# Buck-14.net
KiCad netlist of a schematic drawn in Altium Designer
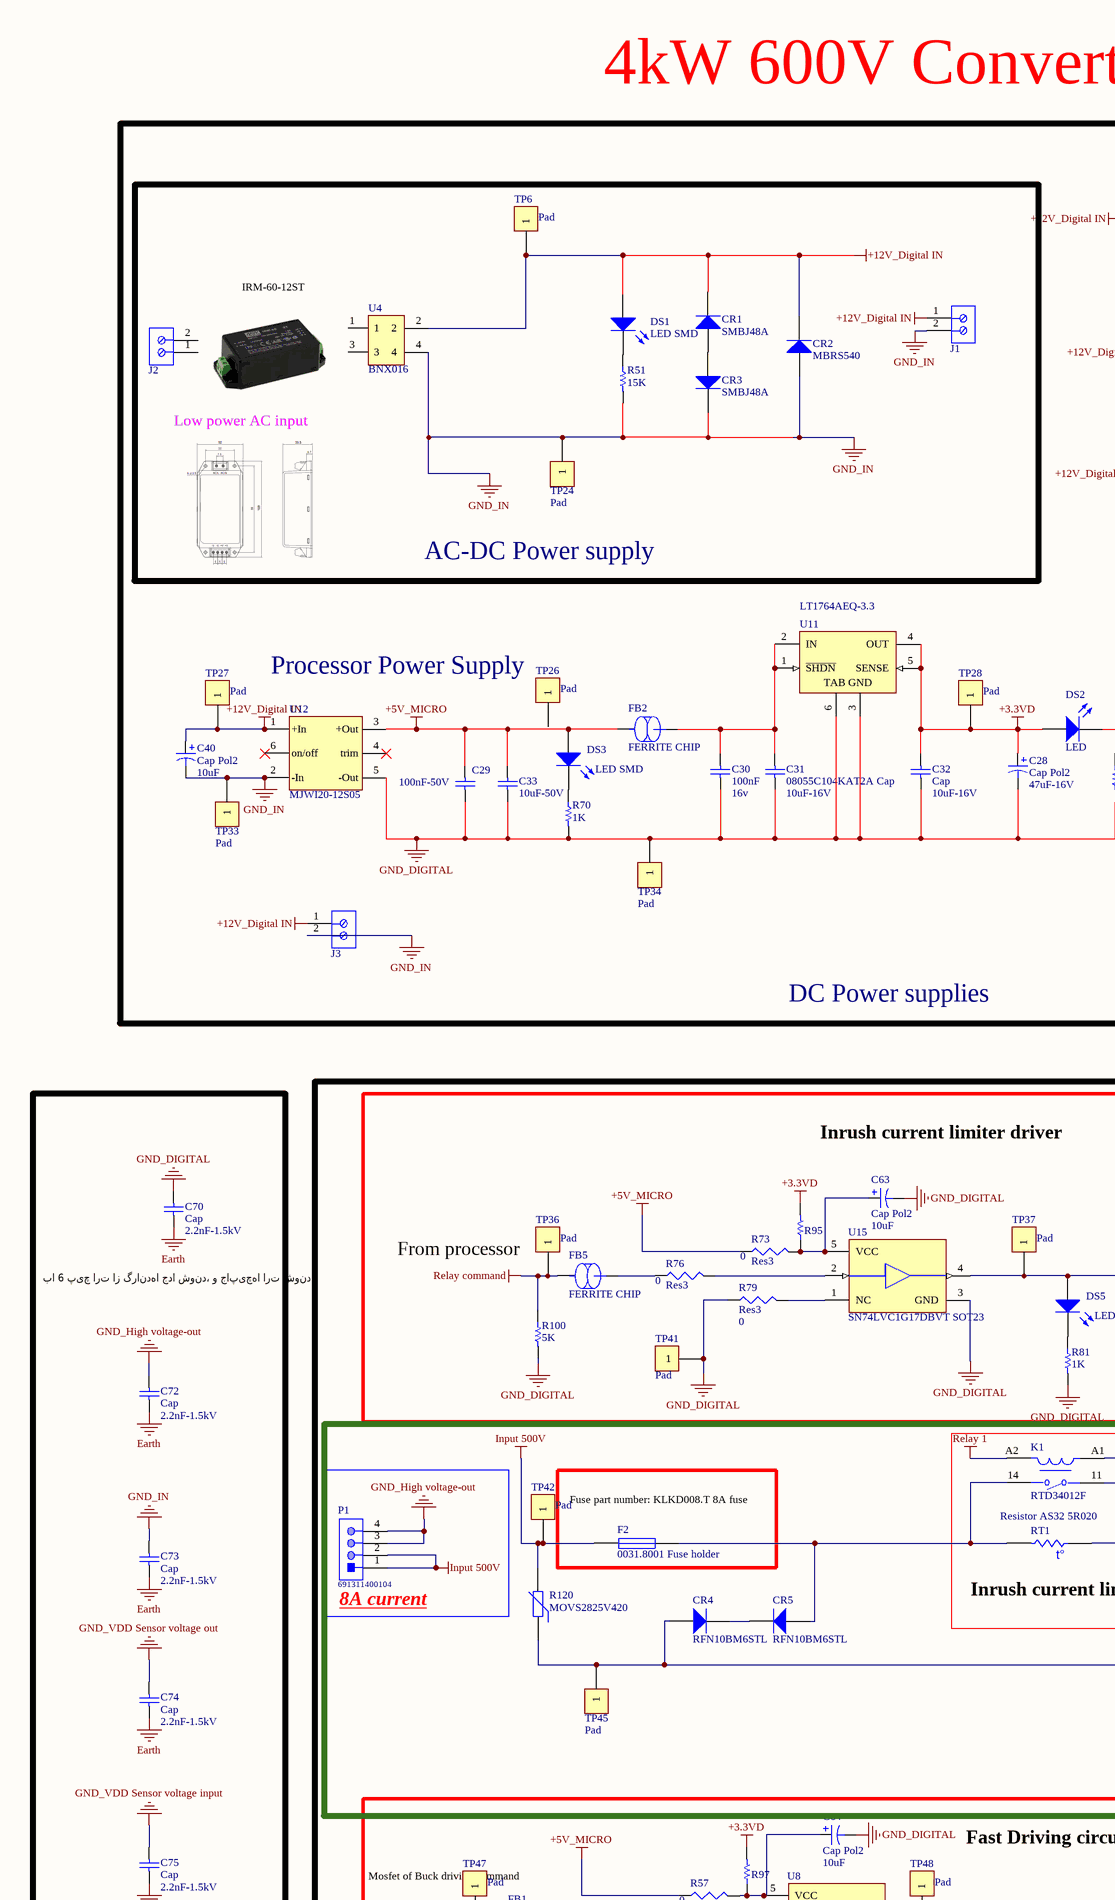
[diagram p0: Buck-14.SchDoc, top left]
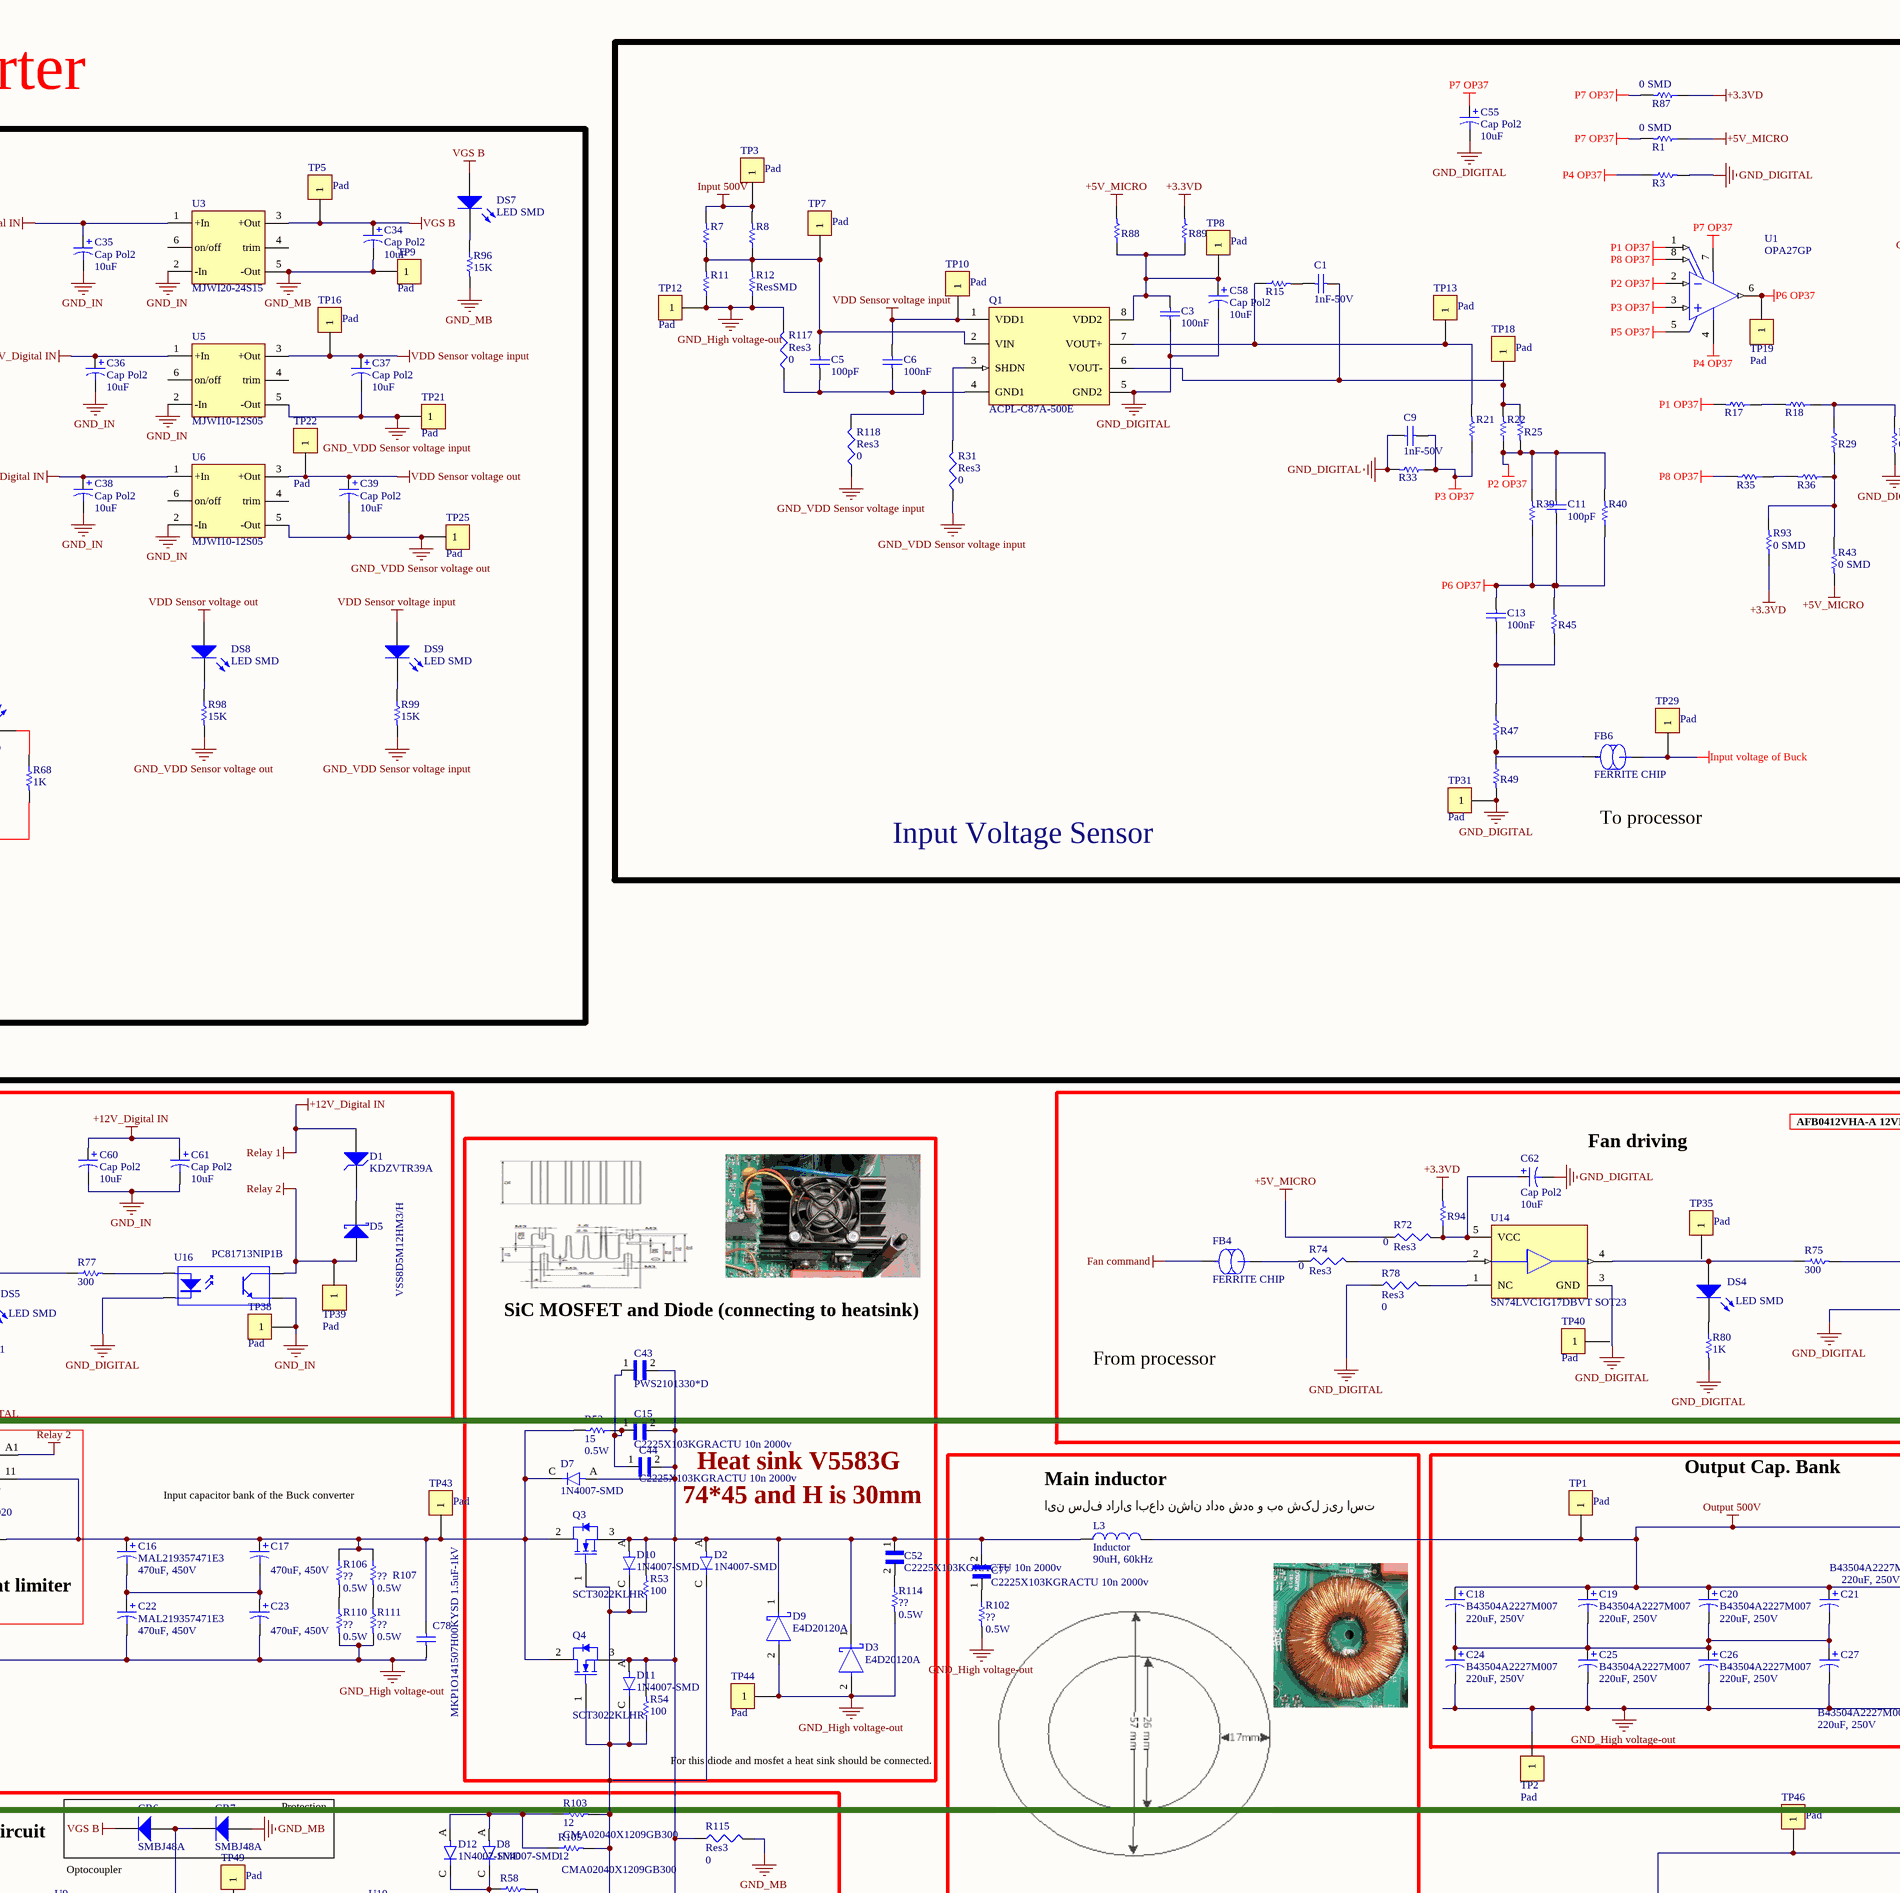
[diagram p1: Buck-14.SchDoc, top middle]
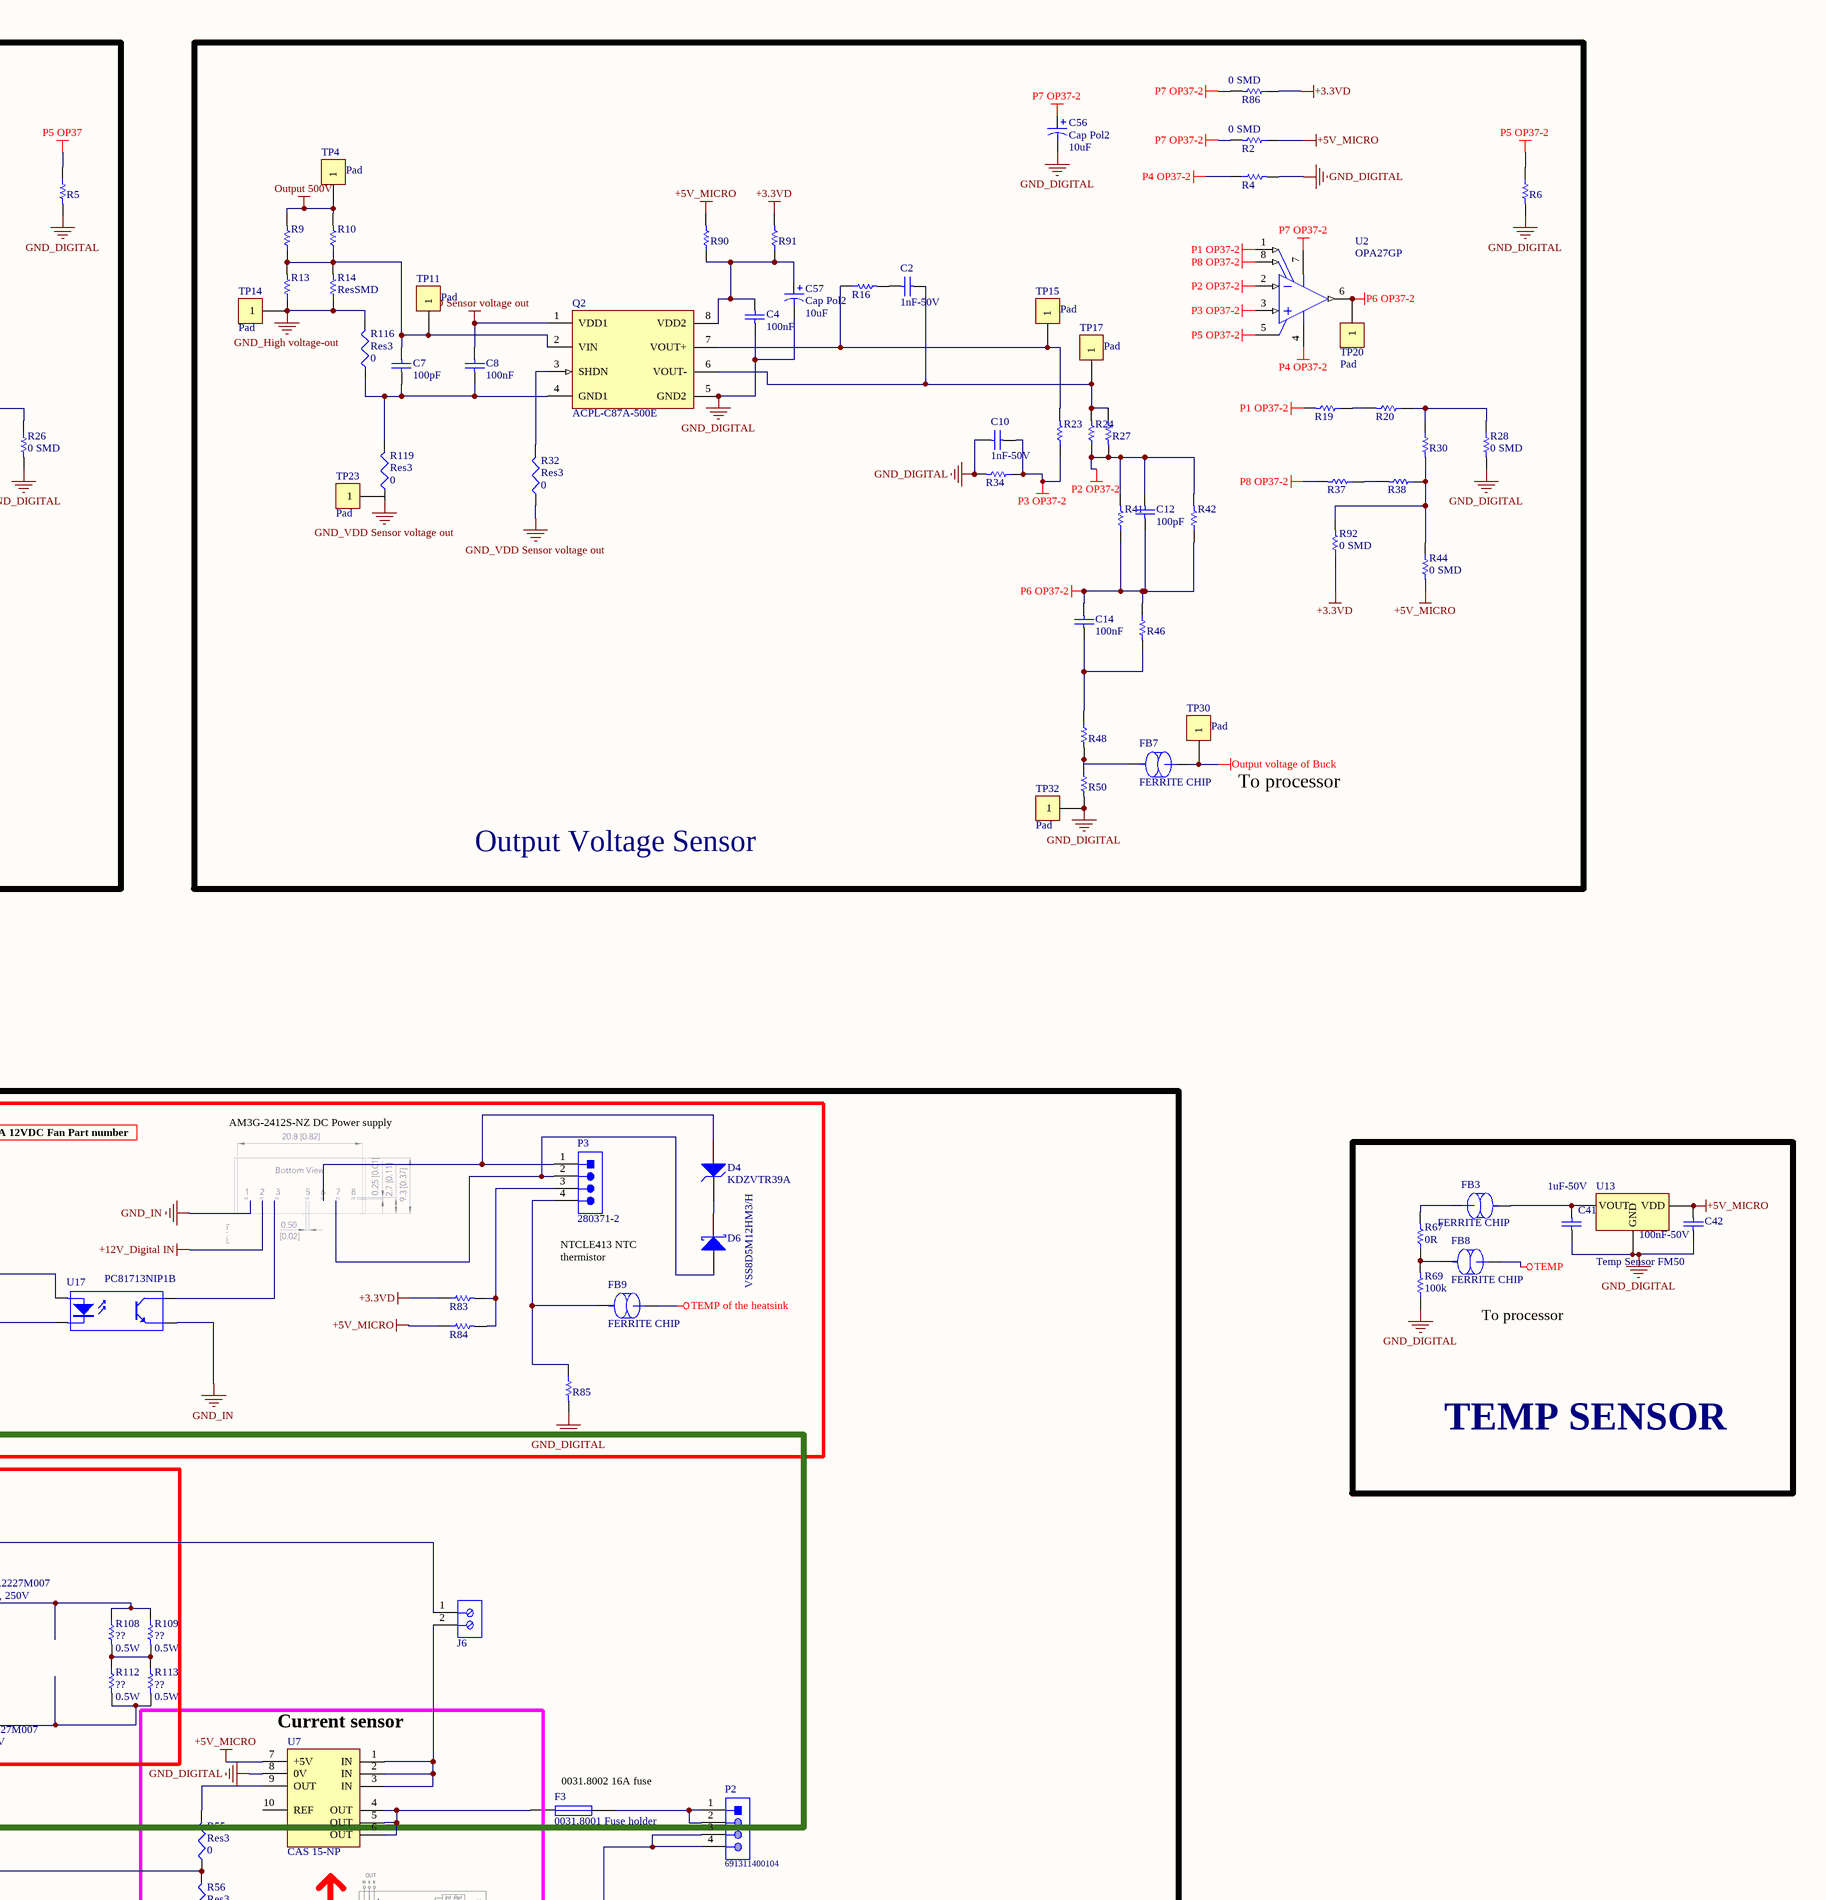
[diagram p2: Buck-14.SchDoc, top right]
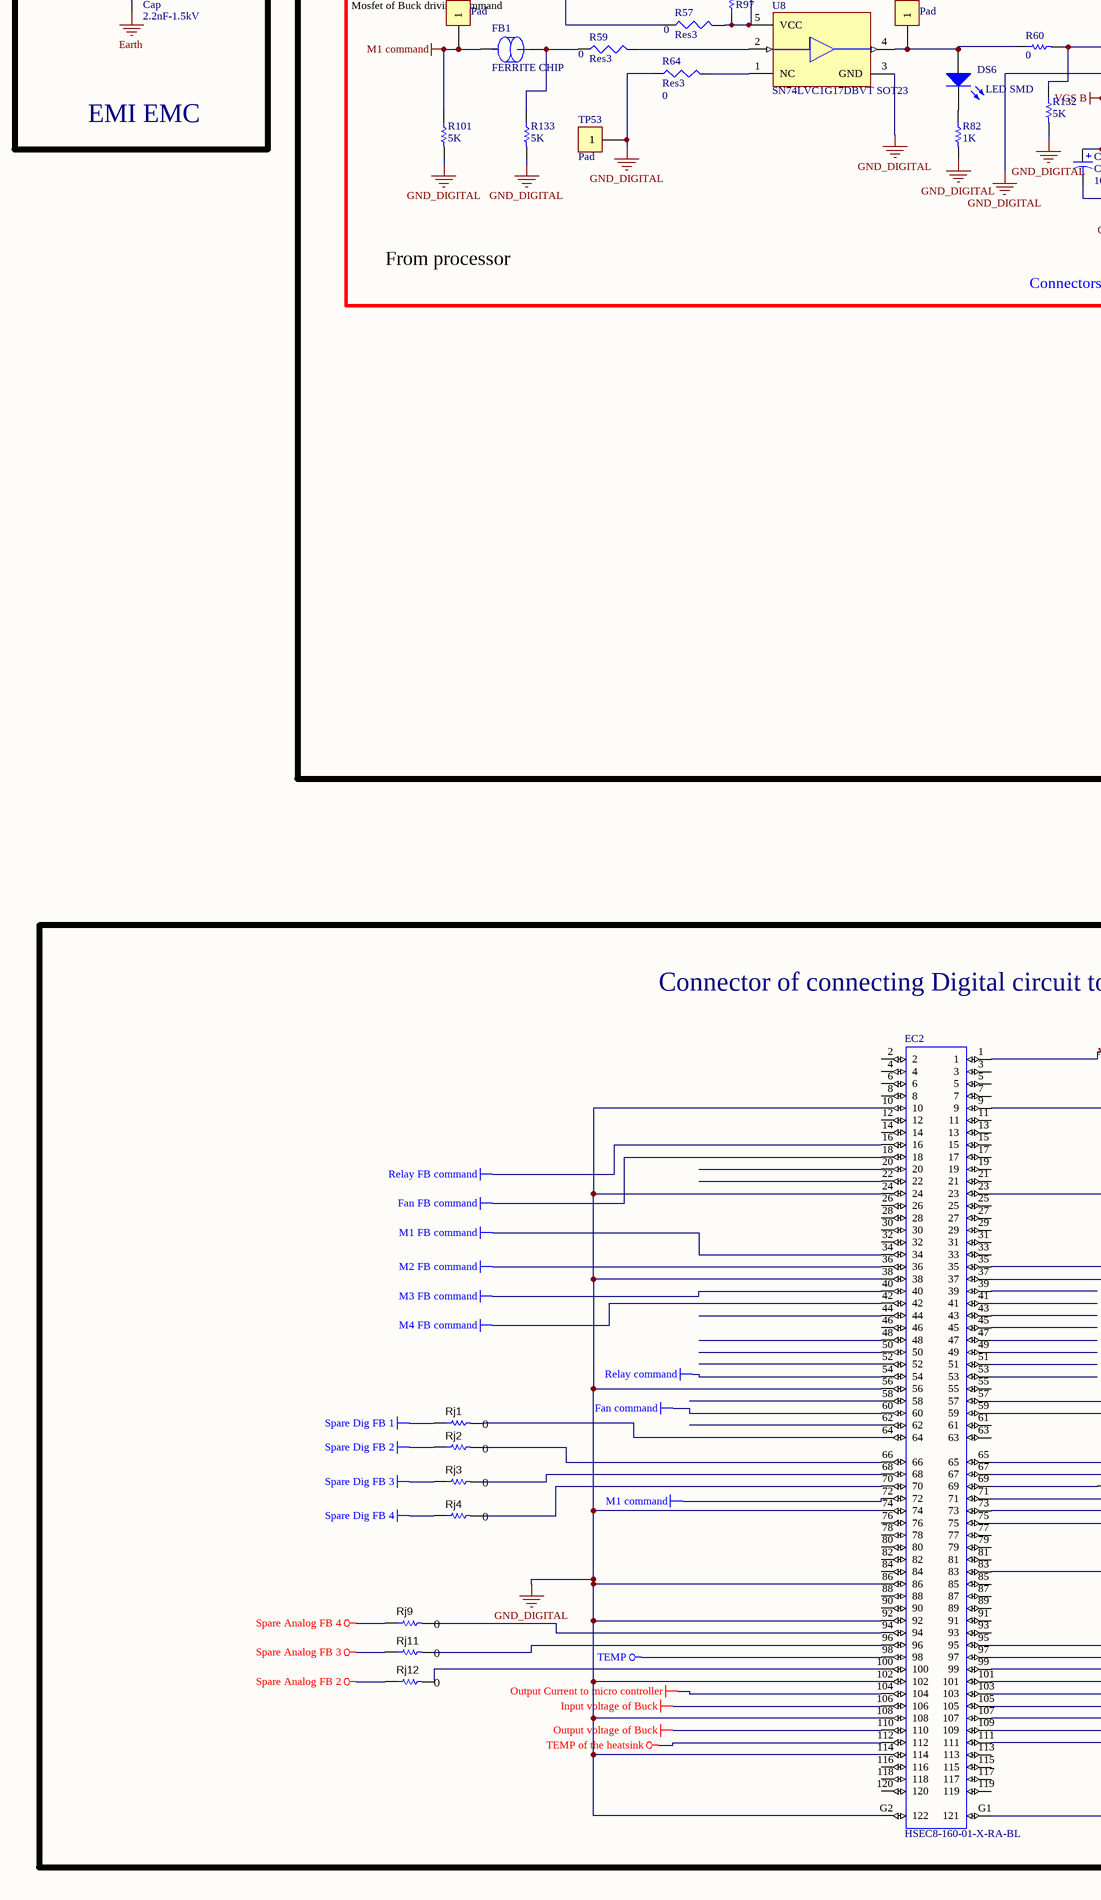
[diagram p3: Buck-14.SchDoc, bottom left]
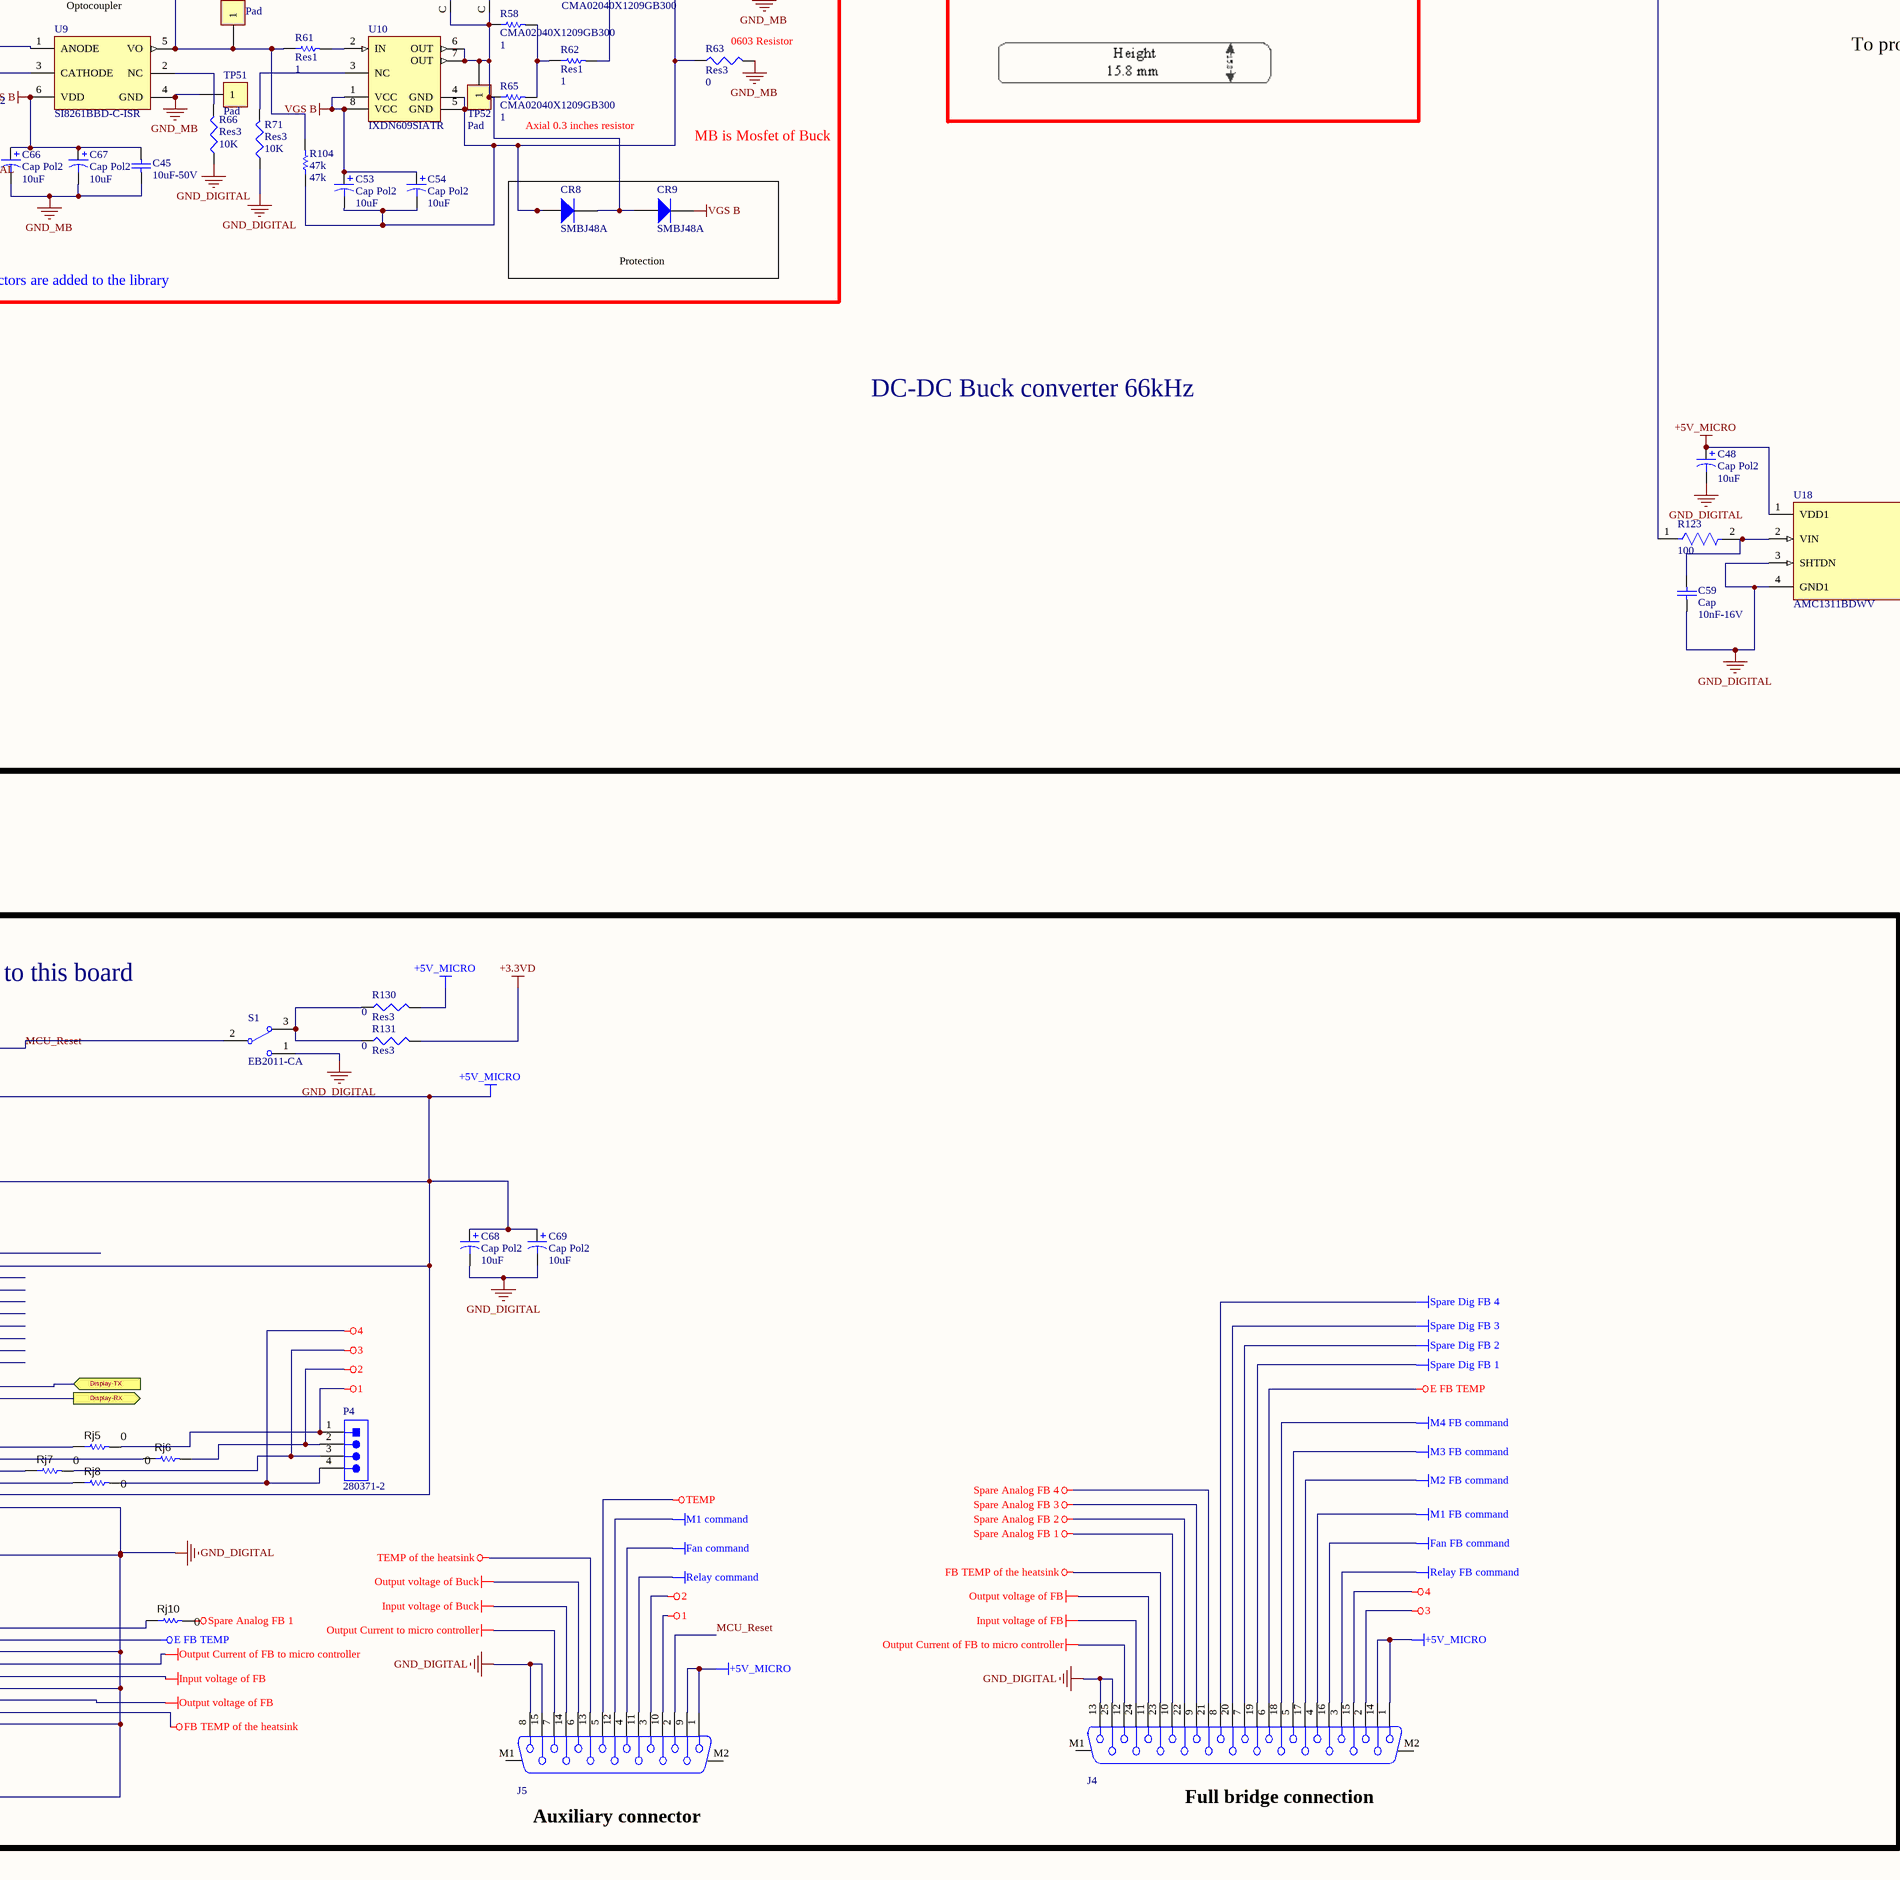
[diagram p4: Buck-14.SchDoc, bottom middle]
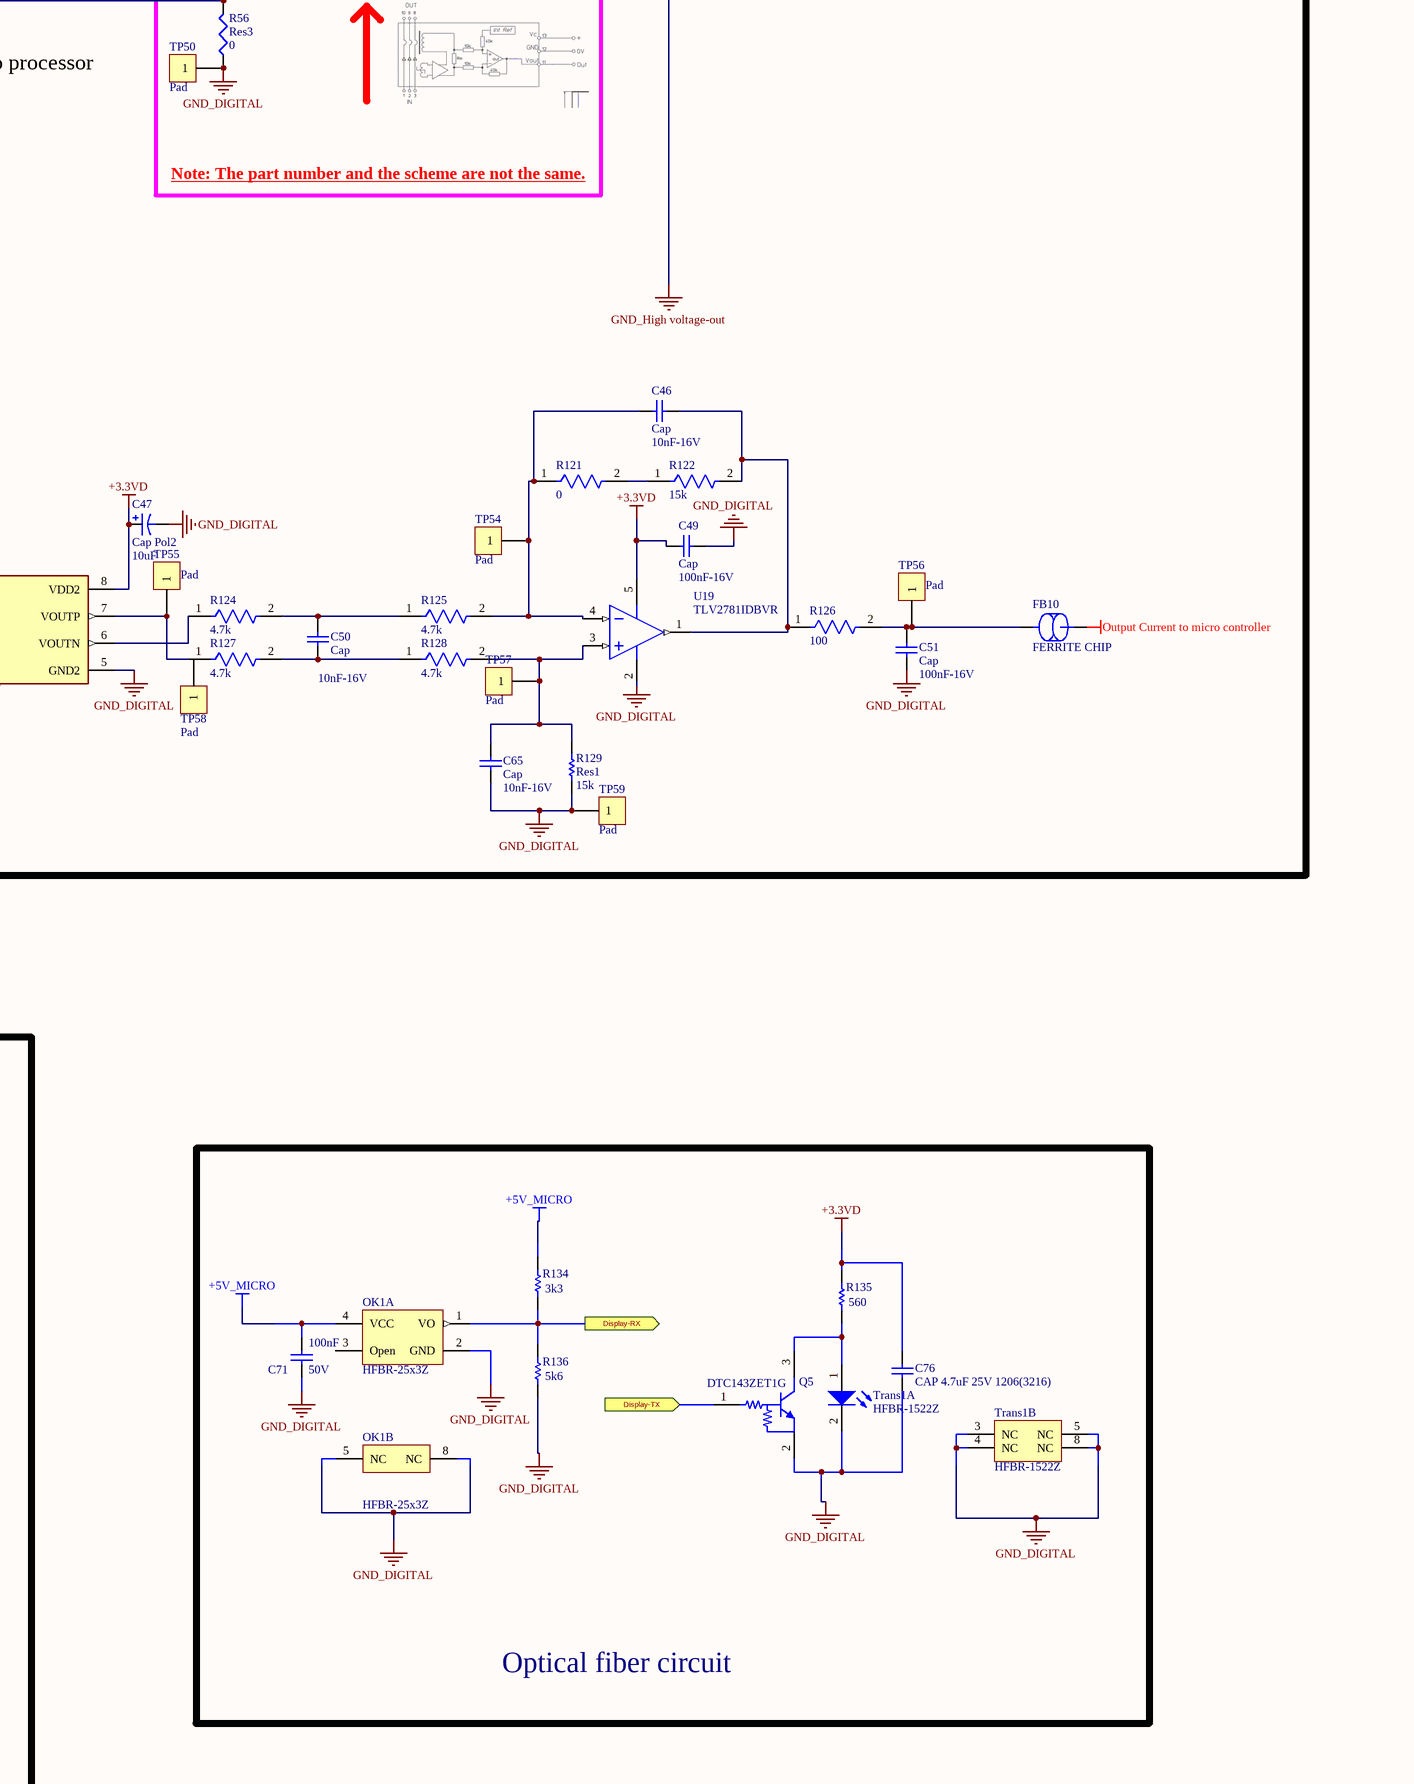
[diagram p5: Buck-14.SchDoc, bottom right]

(export (version "E")
  (design (tool "Eeschema 10.0.6"))
  (components
    (comp (ref "C1")
      (value "1nF-50V")
      (footprint "Footprint_950322:C0805")
      (libsource (lib "MYLIB") (part "CapSMD"))
    )
    (comp (ref "C2")
      (value "1nF-50V")
      (footprint "Footprint_950322:C0805")
      (libsource (lib "MYLIB") (part "CapSMD"))
    )
    (comp (ref "C3")
      (value "100nF")
      (footprint "Footprint_950322:C0805")
      (description "None polar capacitor")
      (libsource (lib "Mylib") (part "Cap ceramic"))
    )
    (comp (ref "C4")
      (value "100nF")
      (footprint "Footprint_950322:C0805")
      (description "None polar capacitor")
      (libsource (lib "Mylib") (part "Cap ceramic"))
    )
    (comp (ref "C5")
      (value "100pF")
      (footprint "Footprint_950322:C0805")
      (description "None polar capacitor")
      (libsource (lib "Mylib") (part "Cap ceramic"))
    )
    (comp (ref "C6")
      (value "100nF")
      (footprint "Footprint_950322:C0805")
      (description "None polar capacitor")
      (libsource (lib "Mylib") (part "Cap ceramic"))
    )
    (comp (ref "C7")
      (value "100pF")
      (footprint "Footprint_950322:C0805")
      (description "None polar capacitor")
      (libsource (lib "Mylib") (part "Cap ceramic"))
    )
    (comp (ref "C8")
      (value "100nF")
      (footprint "Footprint_950322:C0805")
      (description "None polar capacitor")
      (libsource (lib "Mylib") (part "Cap ceramic"))
    )
    (comp (ref "C9")
      (value "1nF-50V")
      (footprint "Footprint_950322:C0805")
      (libsource (lib "MYLIB") (part "CapSMD"))
    )
    (comp (ref "C10")
      (value "1nF-50V")
      (footprint "Footprint_950322:C0805")
      (libsource (lib "MYLIB") (part "CapSMD"))
    )
    (comp (ref "C11")
      (value "100pF")
      (footprint "Footprint_950322:C0805")
      (description "None polar capacitor")
      (libsource (lib "Mylib") (part "Cap ceramic"))
    )
    (comp (ref "C12")
      (value "100pF")
      (footprint "Footprint_950322:C0805")
      (description "None polar capacitor")
      (libsource (lib "Mylib") (part "Cap ceramic"))
    )
    (comp (ref "C13")
      (value "100nF")
      (footprint "Footprint_950322:C0805")
      (description "None polar capacitor")
      (libsource (lib "Mylib") (part "Cap ceramic"))
    )
    (comp (ref "C14")
      (value "100nF")
      (footprint "Footprint_950322:C0805")
      (description "None polar capacitor")
      (libsource (lib "Mylib") (part "Cap ceramic"))
    )
    (comp (ref "C15")
      (value "C2225X103KGRACTU 10n 2000v")
      (footprint "Ceramic disk capacitor")
      (fields (field (name "MF") "AVX") (field (name "MP") "LD052C153JAB2A"))
      (libsource (lib "") (part "Ceramic disk capacitor_1"))
    )
    (comp (ref "C16")
      (value "MAL219357471E3")
      (footprint "Footprint_950322:RB-193 PUR-SI-35x50")
      (description "Polarized Capacitor (Axial)")
      (fields (field (name "ALTIUM_VALUE") "470uF, 450V") (field (name "PUBLISHER") "Altium Limited"))
      (libsource (lib "SCH") (part "Cap Pol2"))
    )
    (comp (ref "C17")
      (value "470uF, 450V")
      (footprint "Footprint_950322:RB-193 PUR-SI-35x50")
      (description "Polarized Capacitor (Axial)")
      (fields (field (name "Comment") "MAL219357471E3") (field (name "PUBLISHER") "Altium Limited"))
      (libsource (lib "SCH") (part "Cap Pol2"))
    )
    (comp (ref "C18")
      (value "B43504A2227M007")
      (footprint "Footprint_950322:RB- B43504")
      (description "Polarized Capacitor (Axial)")
      (fields (field (name "ALTIUM_VALUE") "220uF, 250V") (field (name "PUBLISHER") "Altium Limited"))
      (libsource (lib "SCH") (part "Cap Pol2"))
    )
    (comp (ref "C19")
      (value "B43504A2227M007")
      (footprint "Footprint_950322:RB- B43504")
      (description "Polarized Capacitor (Axial)")
      (fields (field (name "ALTIUM_VALUE") "220uF, 250V") (field (name "PUBLISHER") "Altium Limited"))
      (libsource (lib "SCH") (part "Cap Pol2"))
    )
    (comp (ref "C20")
      (value "B43504A2227M007")
      (footprint "Footprint_950322:RB- B43504")
      (description "Polarized Capacitor (Axial)")
      (fields (field (name "ALTIUM_VALUE") "220uF, 250V") (field (name "PUBLISHER") "Altium Limited"))
      (libsource (lib "SCH") (part "Cap Pol2"))
    )
    (comp (ref "C21")
      (value "B43504A2227M007")
      (footprint "Footprint_950322:RB- B43504")
      (description "Polarized Capacitor (Axial)")
      (fields (field (name "ALTIUM_VALUE") "220uF, 250V") (field (name "PUBLISHER") "Altium Limited"))
      (libsource (lib "SCH") (part "Cap Pol2"))
    )
    (comp (ref "C22")
      (value "MAL219357471E3")
      (footprint "Footprint_950322:RB-193 PUR-SI-35x50")
      (description "Polarized Capacitor (Axial)")
      (fields (field (name "ALTIUM_VALUE") "470uF, 450V") (field (name "PUBLISHER") "Altium Limited"))
      (libsource (lib "SCH") (part "Cap Pol2"))
    )
    (comp (ref "C23")
      (value "470uF, 450V")
      (footprint "Footprint_950322:RB-193 PUR-SI-35x50")
      (description "Polarized Capacitor (Axial)")
      (fields (field (name "Comment") "MAL219357471E3") (field (name "PUBLISHER") "Altium Limited"))
      (libsource (lib "SCH") (part "Cap Pol2"))
    )
    (comp (ref "C24")
      (value "B43504A2227M007")
      (footprint "Footprint_950322:RB- B43504")
      (description "Polarized Capacitor (Axial)")
      (fields (field (name "ALTIUM_VALUE") "220uF, 250V") (field (name "PUBLISHER") "Altium Limited"))
      (libsource (lib "SCH") (part "Cap Pol2"))
    )
    (comp (ref "C25")
      (value "B43504A2227M007")
      (footprint "Footprint_950322:RB- B43504")
      (description "Polarized Capacitor (Axial)")
      (fields (field (name "ALTIUM_VALUE") "220uF, 250V") (field (name "PUBLISHER") "Altium Limited"))
      (libsource (lib "SCH") (part "Cap Pol2"))
    )
    (comp (ref "C26")
      (value "B43504A2227M007")
      (footprint "Footprint_950322:RB- B43504")
      (description "Polarized Capacitor (Axial)")
      (fields (field (name "ALTIUM_VALUE") "220uF, 250V") (field (name "PUBLISHER") "Altium Limited"))
      (libsource (lib "SCH") (part "Cap Pol2"))
    )
    (comp (ref "C27")
      (value "B43504A2227M007")
      (footprint "Footprint_950322:RB- B43504")
      (description "Polarized Capacitor (Axial)")
      (fields (field (name "ALTIUM_VALUE") "220uF, 250V") (field (name "PUBLISHER") "Altium Limited"))
      (libsource (lib "SCH") (part "Cap Pol2"))
    )
    (comp (ref "C28")
      (value "Cap Pol2")
      (footprint "Footprint_950322:CAP_Aluminum-G6.3")
      (description "Polarized Capacitor (Axial)")
      (fields (field (name "ALTIUM_VALUE") "47uF-16V") (field (name "PUBLISHER") "Altium Limited"))
      (libsource (lib "SCH") (part "Cap Pol2"))
    )
    (comp (ref "C29")
      (value "100nF-50V")
      (footprint "Footprint_950322:C0805")
      (libsource (lib "MYLIB") (part "CapSMD"))
    )
    (comp (ref "C30")
      (value "100nF")
      (footprint "Footprint_950322:C0805")
      (description "None polar capacitor")
      (fields (field (name "VOLTE") "16v"))
      (libsource (lib "Mylib") (part "Cap ceramic"))
    )
    (comp (ref "C31")
      (value "08055C104KAT2A Cap")
      (footprint "Footprint_950322:C0805")
      (description "Capacitor")
      (fields (field (name "ALTIUM_VALUE") "10uF-16V") (field (name "PUBLISHER") "Altium Limited"))
      (libsource (lib "SCH") (part "Cap"))
    )
    (comp (ref "C32")
      (value "Cap")
      (footprint "Footprint_950322:C0805")
      (description "Capacitor")
      (fields (field (name "ALTIUM_VALUE") "10uF-16V") (field (name "PUBLISHER") "Altium Limited"))
      (libsource (lib "SCH") (part "Cap"))
    )
    (comp (ref "C33")
      (value "10uF-50V")
      (footprint "Footprint_950322:C0805")
      (libsource (lib "") (part "CapSMD_1"))
    )
    (comp (ref "C34")
      (value "Cap Pol2")
      (footprint "SMD 3016")
      (description "Polarized Capacitor (Axial)")
      (fields (field (name "ALTIUM_VALUE") "10uF") (field (name "PUBLISHER") "Altium Limited"))
      (libsource (lib "SCH") (part "Cap Pol2"))
    )
    (comp (ref "C35")
      (value "Cap Pol2")
      (footprint "SMD 3016")
      (description "Polarized Capacitor (Axial)")
      (fields (field (name "ALTIUM_VALUE") "10uF") (field (name "PUBLISHER") "Altium Limited"))
      (libsource (lib "SCH") (part "Cap Pol2"))
    )
    (comp (ref "C36")
      (value "Cap Pol2")
      (footprint "SMD 3016")
      (description "Polarized Capacitor (Axial)")
      (fields (field (name "ALTIUM_VALUE") "10uF") (field (name "PUBLISHER") "Altium Limited"))
      (libsource (lib "SCH") (part "Cap Pol2"))
    )
    (comp (ref "C37")
      (value "Cap Pol2")
      (footprint "SMD 3016")
      (description "Polarized Capacitor (Axial)")
      (fields (field (name "ALTIUM_VALUE") "10uF") (field (name "PUBLISHER") "Altium Limited"))
      (libsource (lib "SCH") (part "Cap Pol2"))
    )
    (comp (ref "C38")
      (value "Cap Pol2")
      (footprint "SMD 3016")
      (description "Polarized Capacitor (Axial)")
      (fields (field (name "ALTIUM_VALUE") "10uF") (field (name "PUBLISHER") "Altium Limited"))
      (libsource (lib "SCH") (part "Cap Pol2"))
    )
    (comp (ref "C39")
      (value "Cap Pol2")
      (footprint "SMD 3016")
      (description "Polarized Capacitor (Axial)")
      (fields (field (name "ALTIUM_VALUE") "10uF") (field (name "PUBLISHER") "Altium Limited"))
      (libsource (lib "SCH") (part "Cap Pol2"))
    )
    (comp (ref "C40")
      (value "Cap Pol2")
      (footprint "SMD 3016")
      (description "Polarized Capacitor (Axial)")
      (fields (field (name "ALTIUM_VALUE") "10uF") (field (name "PUBLISHER") "Altium Limited"))
      (libsource (lib "SCH") (part "Cap Pol2"))
    )
    (comp (ref "C41")
      (value "1uF-50V")
      (footprint "Footprint_950322:C0805")
      (libsource (lib "MYLIB") (part "CapSMD"))
    )
    (comp (ref "C42") (value "100nF-50V") (footprint "CapSMD-805") (libsource (lib "MYLIB") (part "CapSMD")))
    (comp (ref "C43")
      (value "PWS2101330*D")
      (footprint "Ceramic disk capacitor")
      (fields (field (name "MF") "AVX") (field (name "MP") "LD052C153JAB2A"))
      (libsource (lib "") (part "Ceramic disk capacitor_1"))
    )
    (comp (ref "C44")
      (value "C2225X103KGRACTU 10n 2000v")
      (footprint "Ceramic disk capacitor")
      (fields (field (name "MF") "AVX") (field (name "MP") "LD052C153JAB2A"))
      (libsource (lib "") (part "Ceramic disk capacitor_1"))
    )
    (comp (ref "C45")
      (value "10uF-50V")
      (footprint "Footprint_950322:C0805")
      (libsource (lib "") (part "CapSMD_1"))
    )
    (comp (ref "C46")
      (value "Cap")
      (footprint "SMD 0805-cap")
      (description "Capacitor")
      (fields (field (name "ALTIUM_VALUE") "10nF-16V") (field (name "PUBLISHER") "Altium Limited"))
      (libsource (lib "SCH") (part "Cap"))
    )
    (comp (ref "C47")
      (value "Cap Pol2")
      (footprint "SMD 3016")
      (description "Polarized Capacitor (Axial)")
      (fields (field (name "ALTIUM_VALUE") "10uF") (field (name "PUBLISHER") "Altium Limited"))
      (libsource (lib "SCH") (part "Cap Pol2"))
    )
    (comp (ref "C48")
      (value "Cap Pol2")
      (footprint "SMD 3016")
      (description "Polarized Capacitor (Axial)")
      (fields (field (name "ALTIUM_VALUE") "10uF") (field (name "PUBLISHER") "Altium Limited"))
      (libsource (lib "SCH") (part "Cap Pol2"))
    )
    (comp (ref "C49")
      (value "Cap")
      (footprint "SMD 0805-cap")
      (description "Capacitor")
      (fields (field (name "ALTIUM_VALUE") "100nF-16V") (field (name "PUBLISHER") "Altium Limited"))
      (libsource (lib "SCH") (part "Cap"))
    )
    (comp (ref "C50")
      (value "Cap")
      (footprint "SMD 0805-cap")
      (description "Capacitor")
      (fields (field (name "ALTIUM_VALUE") "10nF-16V") (field (name "PUBLISHER") "Altium Limited"))
      (libsource (lib "SCH") (part "Cap"))
    )
    (comp (ref "C51")
      (value "Cap")
      (footprint "SMD 0805-cap")
      (description "Capacitor")
      (fields (field (name "ALTIUM_VALUE") "100nF-16V") (field (name "PUBLISHER") "Altium Limited"))
      (libsource (lib "SCH") (part "Cap"))
    )
    (comp (ref "C52")
      (value "C2225X103KGRACTU 10n 2000v")
      (footprint "Ceramic disk capacitor")
      (fields (field (name "MF") "AVX") (field (name "MP") "LD052C153JAB2A"))
      (libsource (lib "") (part "Ceramic disk capacitor_2"))
    )
    (comp (ref "C53")
      (value "Cap Pol2")
      (footprint "SMD 3016")
      (description "Polarized Capacitor (Axial)")
      (fields (field (name "ALTIUM_VALUE") "10uF") (field (name "PUBLISHER") "Altium Limited"))
      (libsource (lib "SCH") (part "Cap Pol2"))
    )
    (comp (ref "C54")
      (value "Cap Pol2")
      (footprint "SMD 3016")
      (description "Polarized Capacitor (Axial)")
      (fields (field (name "ALTIUM_VALUE") "10uF") (field (name "PUBLISHER") "Altium Limited"))
      (libsource (lib "SCH") (part "Cap Pol2"))
    )
    (comp (ref "C55")
      (value "Cap Pol2")
      (footprint "SMD 3016")
      (description "Polarized Capacitor (Axial)")
      (fields (field (name "ALTIUM_VALUE") "10uF") (field (name "PUBLISHER") "Altium Limited"))
      (libsource (lib "SCH") (part "Cap Pol2"))
    )
    (comp (ref "C56")
      (value "Cap Pol2")
      (footprint "SMD 3016")
      (description "Polarized Capacitor (Axial)")
      (fields (field (name "ALTIUM_VALUE") "10uF") (field (name "PUBLISHER") "Altium Limited"))
      (libsource (lib "SCH") (part "Cap Pol2"))
    )
    (comp (ref "C57")
      (value "Cap Pol2")
      (footprint "SMD 3016")
      (description "Polarized Capacitor (Axial)")
      (fields (field (name "ALTIUM_VALUE") "10uF") (field (name "PUBLISHER") "Altium Limited"))
      (libsource (lib "SCH") (part "Cap Pol2"))
    )
    (comp (ref "C58")
      (value "Cap Pol2")
      (footprint "SMD 3016")
      (description "Polarized Capacitor (Axial)")
      (fields (field (name "ALTIUM_VALUE") "10uF") (field (name "PUBLISHER") "Altium Limited"))
      (libsource (lib "SCH") (part "Cap Pol2"))
    )
    (comp (ref "C59")
      (value "Cap")
      (footprint "SMD 0805-cap")
      (description "Capacitor")
      (fields (field (name "ALTIUM_VALUE") "10nF-16V") (field (name "PUBLISHER") "Altium Limited"))
      (libsource (lib "SCH") (part "Cap"))
    )
    (comp (ref "C60")
      (value "Cap Pol2")
      (footprint "SMD 3016")
      (description "Polarized Capacitor (Axial)")
      (fields (field (name "ALTIUM_VALUE") "10uF") (field (name "PUBLISHER") "Altium Limited"))
      (libsource (lib "SCH") (part "Cap Pol2"))
    )
    (comp (ref "C61")
      (value "Cap Pol2")
      (footprint "SMD 3016")
      (description "Polarized Capacitor (Axial)")
      (fields (field (name "ALTIUM_VALUE") "10uF") (field (name "PUBLISHER") "Altium Limited"))
      (libsource (lib "SCH") (part "Cap Pol2"))
    )
    (comp (ref "C62")
      (value "Cap Pol2")
      (footprint "SMD 3016")
      (description "Polarized Capacitor (Axial)")
      (fields (field (name "ALTIUM_VALUE") "10uF") (field (name "PUBLISHER") "Altium Limited"))
      (libsource (lib "SCH") (part "Cap Pol2"))
    )
    (comp (ref "C63")
      (value "Cap Pol2")
      (footprint "SMD 3016")
      (description "Polarized Capacitor (Axial)")
      (fields (field (name "ALTIUM_VALUE") "10uF") (field (name "PUBLISHER") "Altium Limited"))
      (libsource (lib "SCH") (part "Cap Pol2"))
    )
    (comp (ref "C64")
      (value "Cap Pol2")
      (footprint "SMD 3016")
      (description "Polarized Capacitor (Axial)")
      (fields (field (name "ALTIUM_VALUE") "10uF") (field (name "PUBLISHER") "Altium Limited"))
      (libsource (lib "SCH") (part "Cap Pol2"))
    )
    (comp (ref "C65")
      (value "Cap")
      (footprint "SMD 0805-cap")
      (description "Capacitor")
      (fields (field (name "ALTIUM_VALUE") "10nF-16V") (field (name "PUBLISHER") "Altium Limited"))
      (libsource (lib "SCH") (part "Cap"))
    )
    (comp (ref "C66")
      (value "Cap Pol2")
      (footprint "SMD 3016")
      (description "Polarized Capacitor (Axial)")
      (fields (field (name "ALTIUM_VALUE") "10uF") (field (name "PUBLISHER") "Altium Limited"))
      (libsource (lib "SCH") (part "Cap Pol2"))
    )
    (comp (ref "C67")
      (value "Cap Pol2")
      (footprint "SMD 3016")
      (description "Polarized Capacitor (Axial)")
      (fields (field (name "ALTIUM_VALUE") "10uF") (field (name "PUBLISHER") "Altium Limited"))
      (libsource (lib "SCH") (part "Cap Pol2"))
    )
    (comp (ref "C68")
      (value "Cap Pol2")
      (footprint "SMD 3016")
      (description "Polarized Capacitor (Axial)")
      (fields (field (name "ALTIUM_VALUE") "10uF") (field (name "PUBLISHER") "Altium Limited"))
      (libsource (lib "SCH") (part "Cap Pol2"))
    )
    (comp (ref "C69")
      (value "Cap Pol2")
      (footprint "SMD 3016")
      (description "Polarized Capacitor (Axial)")
      (fields (field (name "ALTIUM_VALUE") "10uF") (field (name "PUBLISHER") "Altium Limited"))
      (libsource (lib "SCH") (part "Cap Pol2"))
    )
    (comp (ref "C70")
      (value "Cap")
      (footprint "SMD 0805-cap")
      (description "Capacitor")
      (fields (field (name "AY1222M47Y5UC63L0") "2.2nF-1.5kV") (field (name "PUBLISHER") "Altium Limited"))
      (libsource (lib "SCH") (part "Cap"))
    )
    (comp (ref "C71")
      (value "GRM188R71H104KA93D")
      (footprint "CAPC1608X90X35ML10T15")
      (description "Chip Capacitor, 0.1 uF, +/- 10%, 50 V, -55 to 125 degC, 0603 (1608 Metric), RoHS, Tape and Reel")
      (fields
        (field (name "TOLERANCE") "10%")
        (field (name "VOLTAGE RATING") "50V")
        (field (name "CAPACITANCE") "100nF")
        (field (name "VOLTAGE") "50V")
      )
      (libsource (lib "Altium Content Vault") (part "CAP-NP-2"))
    )
    (comp (ref "C72")
      (value "Cap")
      (footprint "SMD 0805-cap")
      (description "Capacitor")
      (fields (field (name "AY1222M47Y5UC63L0") "2.2nF-1.5kV") (field (name "PUBLISHER") "Altium Limited"))
      (libsource (lib "SCH") (part "Cap"))
    )
    (comp (ref "C73")
      (value "Cap")
      (footprint "SMD 0805-cap")
      (description "Capacitor")
      (fields (field (name "AY1222M47Y5UC63L0") "2.2nF-1.5kV") (field (name "PUBLISHER") "Altium Limited"))
      (libsource (lib "SCH") (part "Cap"))
    )
    (comp (ref "C74")
      (value "Cap")
      (footprint "SMD 0805-cap")
      (description "Capacitor")
      (fields (field (name "AY1222M47Y5UC63L0") "2.2nF-1.5kV") (field (name "PUBLISHER") "Altium Limited"))
      (libsource (lib "SCH") (part "Cap"))
    )
    (comp (ref "C75")
      (value "Cap")
      (footprint "SMD 0805-cap")
      (description "Capacitor")
      (fields (field (name "AY1222M47Y5UC63L0") "2.2nF-1.5kV") (field (name "PUBLISHER") "Altium Limited"))
      (libsource (lib "SCH") (part "Cap"))
    )
    (comp (ref "C76")
      (value "CAP 4.7uF 25V 1206(3216)")
      (footprint "CAPC1206(3216)190_N")
      (description "CAP 4.7uF 25V ±5% 1206 (3216 Metric) Thickness 1.9mm SMD")
      (fields (field (name "TOLERANCE") "Â±5%"))
      (libsource (lib "Altium Content Vault") (part "CAP"))
    )
    (comp (ref "C77")
      (value "C2225X103KGRACTU 10n 2000v")
      (footprint "Ceramic disk capacitor")
      (fields (field (name "MF") "AVX") (field (name "MP") "LD052C153JAB2A"))
      (libsource (lib "Capacitors dip") (part "Ceramic disk capacitor"))
    )
    (comp (ref "C78")
      (value "MKP1O141507H00KYSD 1.5uF-1kV")
      (footprint "CapSMD-805")
      (libsource (lib "MYLIB") (part "CapSMD"))
    )
    (comp (ref "CR1")
      (value "SMBJ48A")
      (footprint "DiodeSMD4.5mm")
      (libsource (lib "MYLIB") (part "DiodeSMD4.5mm"))
    )
    (comp (ref "CR2")
      (value "MBRS540")
      (footprint "DiodeSMD5.5mm")
      (libsource (lib "MYLIB") (part "DiodeSMD5.5mm"))
    )
    (comp (ref "CR3")
      (value "SMBJ48A")
      (footprint "DiodeSMD4.5mm")
      (libsource (lib "MYLIB") (part "DiodeSMD4.5mm"))
    )
    (comp (ref "CR4")
      (value "RFN10BM6STL")
      (footprint "DiodeSMD4.5mm")
      (libsource (lib "MYLIB") (part "DiodeSMD4.5mm"))
    )
    (comp (ref "CR5")
      (value "RFN10BM6STL")
      (footprint "DiodeSMD4.5mm")
      (libsource (lib "MYLIB") (part "DiodeSMD4.5mm"))
    )
    (comp (ref "CR6")
      (value "SMBJ48A")
      (footprint "DiodeSMD4.5mm")
      (libsource (lib "MYLIB") (part "DiodeSMD4.5mm"))
    )
    (comp (ref "CR7")
      (value "SMBJ48A")
      (footprint "DiodeSMD4.5mm")
      (libsource (lib "MYLIB") (part "DiodeSMD4.5mm"))
    )
    (comp (ref "CR8")
      (value "SMBJ48A")
      (footprint "DiodeSMD4.5mm")
      (libsource (lib "MYLIB") (part "DiodeSMD4.5mm"))
    )
    (comp (ref "CR9")
      (value "SMBJ48A")
      (footprint "DiodeSMD4.5mm")
      (libsource (lib "MYLIB") (part "DiodeSMD4.5mm"))
    )
    (comp (ref "D1")
      (value "KDZVTR39A")
      (footprint "DIODE-0.7")
      (description "Zener Diode")
      (fields (field (name "PUBLISHER") "Altium Limited"))
      (libsource (lib "Miscellaneous Devices") (part "D Zener"))
    )
    (comp (ref "D2")
      (value "1N4007-SMD")
      (footprint "DIOAD1060W80L520D270")
      (description "Diode Standard 1000V 1A Through Hole DO-204AL _DO-41_")
      (fields (field (name "MF") "ON Semiconductor") (field (name "MP") "1N4007"))
      (libsource (lib "Diode") (part "1N4007"))
    )
    (comp (ref "D3")
      (value "E4D20120A")
      (footprint "FP-TO-220-2-MFG")
      (description "E SERIES, 20 AMP, 1200V G4 SCHOT")
      (libsource (lib "Altium Content Vault") (part "1d6ec82d83fb6aee721767c19dac4b9"))
    )
    (comp (ref "D4")
      (value "KDZVTR39A")
      (footprint "DIODE-0.7")
      (description "Zener Diode")
      (fields (field (name "PUBLISHER") "Altium Limited"))
      (libsource (lib "Miscellaneous Devices") (part "D Zener"))
    )
    (comp (ref "D5")
      (value "VSS8D5M12HM3/H")
      (footprint "SMB")
      (description "Schottky Diode")
      (fields (field (name "PUBLISHER") "Altium Limited"))
      (libsource (lib "Miscellaneous Devices") (part "D Schottky"))
    )
    (comp (ref "D6")
      (value "VSS8D5M12HM3/H")
      (footprint "SMB")
      (description "Schottky Diode")
      (fields (field (name "PUBLISHER") "Altium Limited"))
      (libsource (lib "Miscellaneous Devices") (part "D Schottky"))
    )
    (comp (ref "D7")
      (value "1N4007-SMD")
      (footprint "DIOAD1060W80L520D270")
      (description "Diode Standard 1000V 1A Through Hole DO-204AL _DO-41_")
      (fields (field (name "MF") "ON Semiconductor") (field (name "MP") "1N4007"))
      (libsource (lib "Diode") (part "1N4007"))
    )
    (comp (ref "D8")
      (value "1N4007-SMD")
      (footprint "DIOAD1060W80L520D270")
      (description "Diode Standard 1000V 1A Through Hole DO-204AL _DO-41_")
      (fields (field (name "MF") "ON Semiconductor") (field (name "MP") "1N4007"))
      (libsource (lib "Diode") (part "1N4007"))
    )
    (comp (ref "D9")
      (value "E4D20120A")
      (footprint "FP-TO-220-2-MFG")
      (description "E SERIES, 20 AMP, 1200V G4 SCHOT")
      (libsource (lib "Altium Content Vault") (part "1d6ec82d83fb6aee721767c19dac4b9"))
    )
    (comp (ref "D10")
      (value "1N4007-SMD")
      (footprint "DIOAD1060W80L520D270")
      (description "Diode Standard 1000V 1A Through Hole DO-204AL _DO-41_")
      (fields (field (name "MF") "ON Semiconductor") (field (name "MP") "1N4007"))
      (libsource (lib "Diode") (part "1N4007"))
    )
    (comp (ref "D11")
      (value "1N4007-SMD")
      (footprint "DIOAD1060W80L520D270")
      (description "Diode Standard 1000V 1A Through Hole DO-204AL _DO-41_")
      (fields (field (name "MF") "ON Semiconductor") (field (name "MP") "1N4007"))
      (libsource (lib "Diode") (part "1N4007"))
    )
    (comp (ref "D12")
      (value "1N4007-SMD")
      (footprint "DIOAD1060W80L520D270")
      (description "Diode Standard 1000V 1A Through Hole DO-204AL _DO-41_")
      (fields (field (name "MF") "ON Semiconductor") (field (name "MP") "1N4007"))
      (libsource (lib "Diode") (part "1N4007"))
    )
    (comp (ref "DS1")
      (value "LED SMD")
      (footprint "Footprint_950322:LED0805")
      (libsource (lib "MYLIB") (part "LED SMD"))
    )
    (comp (ref "DS2")
      (value "LED")
      (footprint "Footprint_950322:LED0805")
      (libsource (lib "SCH") (part "LED"))
    )
    (comp (ref "DS3")
      (value "LED SMD")
      (footprint "Footprint_950322:LED0805")
      (description "Blue SURFACE MOUNT LED LAMP, -40 to +85 ,0805 SIZE")
      (fields (field (name "PART NUMBER") "QTLP630C-7"))
      (libsource (lib "kashizadeh_ali") (part "LED"))
    )
    (comp (ref "DS4")
      (value "LED SMD")
      (footprint "Footprint_950322:LED0805")
      (description "Blue SURFACE MOUNT LED LAMP, -40 to +85 ,0805 SIZE")
      (fields (field (name "PART NUMBER") "QTLP630C-7"))
      (libsource (lib "kashizadeh_ali") (part "LED"))
    )
    (comp (ref "DS5")
      (value "LED SMD")
      (footprint "Footprint_950322:LED0805")
      (description "Blue SURFACE MOUNT LED LAMP, -40 to +85 ,0805 SIZE")
      (fields (field (name "PART NUMBER") "QTLP630C-7"))
      (libsource (lib "kashizadeh_ali") (part "LED"))
    )
    (comp (ref "DS6")
      (value "LED SMD")
      (footprint "Footprint_950322:LED0805")
      (description "Blue SURFACE MOUNT LED LAMP, -40 to +85 ,0805 SIZE")
      (fields (field (name "PART NUMBER") "QTLP630C-7"))
      (libsource (lib "kashizadeh_ali") (part "LED"))
    )
    (comp (ref "DS7")
      (value "LED SMD")
      (footprint "Footprint_950322:LED0805")
      (libsource (lib "MYLIB") (part "LED SMD"))
    )
    (comp (ref "DS8")
      (value "LED SMD")
      (footprint "Footprint_950322:LED0805")
      (libsource (lib "MYLIB") (part "LED SMD"))
    )
    (comp (ref "DS9")
      (value "LED SMD")
      (footprint "Footprint_950322:LED0805")
      (libsource (lib "MYLIB") (part "LED SMD"))
    )
    (comp (ref "EC2")
      (value "HSEC8-160-01-X-RA-BL")
      (footprint "HSEC8-160-01-X-RA-BL:HSEC8-160-01-X-RA-BL")
      (description "0.8MM HIGH SPEED ASSEMBLY.")
      (libsource (lib "HSEC8-160-01-X-RA-BL") (part "HSEC8-160-01-X-RA-BL"))
    )
    (comp (ref "F2")
      (value "0031.8001 Fuse holder")
      (footprint "PIN-W2/E2.8")
      (description "Fuse")
      (fields (field (name "PUBLISHER") "Altium Limited"))
      (libsource (lib "Miscellaneous Devices") (part "Fuse 1"))
    )
    (comp (ref "F3")
      (value "0031.8001 Fuse holder")
      (footprint "PIN-W2/E2.8")
      (description "Fuse")
      (fields (field (name "PUBLISHER") "Altium Limited"))
      (libsource (lib "Miscellaneous Devices") (part "Fuse 1"))
    )
    (comp (ref "FB1")
      (value "FERRITE CHIP")
      (footprint "Footprint_950322:L0805")
      (libsource (lib "No_avaran") (part "FERRITE CHIP"))
    )
    (comp (ref "FB2")
      (value "FERRITE CHIP")
      (footprint "Footprint_950322:L0805")
      (libsource (lib "No_avaran") (part "FERRITE CHIP"))
    )
    (comp (ref "FB3")
      (value "FERRITE CHIP")
      (footprint "Footprint_950322:L0805")
      (libsource (lib "") (part "FERRITE CHIP_1"))
    )
    (comp (ref "FB4")
      (value "FERRITE CHIP")
      (footprint "Footprint_950322:L0805")
      (libsource (lib "No_avaran") (part "FERRITE CHIP"))
    )
    (comp (ref "FB5")
      (value "FERRITE CHIP")
      (footprint "Footprint_950322:L0805")
      (libsource (lib "No_avaran") (part "FERRITE CHIP"))
    )
    (comp (ref "FB6")
      (value "FERRITE CHIP")
      (footprint "Footprint_950322:L0805")
      (libsource (lib "No_avaran") (part "FERRITE CHIP"))
    )
    (comp (ref "FB7")
      (value "FERRITE CHIP")
      (footprint "Footprint_950322:L0805")
      (libsource (lib "No_avaran") (part "FERRITE CHIP"))
    )
    (comp (ref "FB8")
      (value "FERRITE CHIP")
      (footprint "Footprint_950322:L0805")
      (libsource (lib "No_avaran") (part "FERRITE CHIP"))
    )
    (comp (ref "FB9")
      (value "FERRITE CHIP")
      (footprint "Footprint_950322:L0805")
      (libsource (lib "No_avaran") (part "FERRITE CHIP"))
    )
    (comp (ref "FB10")
      (value "FERRITE CHIP")
      (footprint "Footprint_950322:L0805")
      (libsource (lib "No_avaran") (part "FERRITE CHIP"))
    )
    (comp (ref "J1")
      (value "691101710002")
      (footprint "691101710002")
      (description "WR-TBL Series 101 Horizontal Entry Modular, THT, pitch 5mm, 2p")
      (fields (field (name "MANUFACTURER") "Wurth Elektronik"))
      (libsource (lib "Altium_WR-TBL (rev22b)") (part "691101710002"))
    )
    (comp (ref "J2")
      (value "691101710002")
      (footprint "691101710002")
      (description "WR-TBL Series 101 Horizontal Entry Modular, THT, pitch 5mm, 2p")
      (fields (field (name "MANUFACTURER") "Wurth Elektronik"))
      (libsource (lib "Altium_WR-TBL (rev22b)") (part "691101710002"))
    )
    (comp (ref "J3")
      (value "691101710002")
      (footprint "691101710002")
      (description "WR-TBL Series 101 Horizontal Entry Modular, THT, pitch 5mm, 2p")
      (fields (field (name "MANUFACTURER") "Wurth Elektronik"))
      (libsource (lib "Altium_WR-TBL (rev22b)") (part "691101710002"))
    )
    (comp (ref "J4")
      (value "61802525123")
      (footprint "61802525123")
      (description "WR-DSUB Female PCB Connector, Straight, 25p")
      (fields (field (name "MANUFACTURER") "Wurth Elektronik"))
      (libsource (lib "WR-DSUB") (part "61802525123"))
    )
    (comp (ref "J5")
      (value "61801525123")
      (footprint "61801525123")
      (description "WR-DSUB Female PCB Connector, Straight, 15p")
      (fields (field (name "MANUFACTURER") "Wurth Elektronik"))
      (libsource (lib "WR-DSUB") (part "61801525123"))
    )
    (comp (ref "J6")
      (value "691101710002")
      (footprint "691101710002")
      (description "WR-TBL Series 101 Horizontal Entry Modular, THT, pitch 5mm, 2p")
      (fields (field (name "MANUFACTURER") "Wurth Elektronik"))
      (libsource (lib "Altium_WR-TBL (rev22b)") (part "691101710002"))
    )
    (comp (ref "K1")
      (value "RTD34012F")
      (footprint "FP-RTD34012F-MFG")
      (description "RELAY GEN PURPOSE SPST 16A 12V")
      (libsource (lib "Altium Content Vault") (part "36ad11d084bb552319afff42e0065da"))
    )
    (comp (ref "L3")
      (value "Inductor")
      (footprint "0402-A")
      (fields (field (name "ALTIUM_VALUE") "90uH, 60kHz") (field (name "PUBLISHER") "Altium Limited"))
      (libsource (lib "Miscellaneous Devices") (part "Inductor"))
    )
    (comp (ref "OK1")
      (value "HFBR-25x3Z")
      (footprint "BCM-HFBR-2521Z-4")
      (description "The Versatile Fiber Optic Connection, 40 kBd, -40 to 85 degC, 4-Pin, RoHS, Rail/Tube")
      (libsource (lib "HFBR_Tx_Rx") (part "HFBR-25x3Z"))
    )
    (comp (ref "P1")
      (value "691311400104")
      (footprint "691311400104")
      (description "Serie 3114 - 7.62mm Close Vertical PCB Header WR-TBL, 4 pin")
      (fields (field (name "MANUFACTURER") "Wurth Elektronik") (field (name "PUBLISHER") "WurthElektronik"))
      (libsource (lib "") (part "WE-CN-1P-M-R4_1"))
    )
    (comp (ref "P2")
      (value "691311400104")
      (footprint "691311400104")
      (description "Serie 3114 - 7.62mm Close Vertical PCB Header WR-TBL, 4 pin")
      (fields (field (name "MANUFACTURER") "Wurth Elektronik") (field (name "PUBLISHER") "WurthElektronik"))
      (libsource (lib "Altium Content Vault") (part "WE-CN-1P-M-R4"))
    )
    (comp (ref "P3")
      (value "280371-2")
      (footprint "TECO-280371-2_V")
      (fields (field (name "MANUFACTURER") "TE Connectivity"))
      (libsource (lib "Altium Content Vault") (part "CN-1P-M-R4"))
    )
    (comp (ref "P4")
      (value "280371-2")
      (footprint "TECO-280371-2_V")
      (fields (field (name "MANUFACTURER") "TE Connectivity"))
      (libsource (lib "Altium Content Vault") (part "CN-1P-M-R4"))
    )
    (comp (ref "Q1")
      (value "ACPL-C87A-500E")
      (footprint "FP-SSO-8-MFG")
      (description "IC OPAMP ISOLATION 100KHZ 8SO")
      (libsource (lib "Altium Content Vault") (part "b42ed144594ce334135a4fb1ded0a30"))
    )
    (comp (ref "Q2")
      (value "ACPL-C87A-500E")
      (footprint "FP-SSO-8-MFG")
      (description "IC OPAMP ISOLATION 100KHZ 8SO")
      (libsource (lib "Altium Content Vault") (part "b42ed144594ce334135a4fb1ded0a30"))
    )
    (comp (ref "Q3")
      (value "SCT3022KLHR")
      (footprint "INF-PG-TO247-3-44")
      (fields (field (name "MANUFACTURER") "Infineon") (field (name "PARTNUMBER") "IPW60R099CP"))
      (libsource (lib "Altium Content Vault") (part "INF-NEMOS-GDS-3"))
    )
    (comp (ref "Q4")
      (value "SCT3022KLHR")
      (footprint "INF-PG-TO247-3-44")
      (fields (field (name "MANUFACTURER") "Infineon") (field (name "PARTNUMBER") "IPW60R099CP"))
      (libsource (lib "Altium Content Vault") (part "INF-NEMOS-GDS-3"))
    )
    (comp (ref "Q5")
      (value "DTC143ZET1G")
      (footprint "ONSC-SC-75-3-463-01_V")
      (fields (field (name "MANUFACTURER") "On Semiconductor"))
      (libsource (lib "Altium Content Vault") (part "ONSC-BRT-NPN-B1E2C3-3"))
    )
    (comp (ref "R1")
      (value "0 SMD")
      (footprint "Footprint_950322:R0805")
      (libsource (lib "MYLIB") (part "ResSMD"))
    )
    (comp (ref "R2")
      (value "0 SMD")
      (footprint "Footprint_950322:R0805")
      (libsource (lib "MYLIB") (part "ResSMD"))
    )
    (comp (ref "R3")
      (value "ResSMD")
      (footprint "Footprint_950322:R0805")
      (libsource (lib "MYLIB") (part "ResSMD"))
    )
    (comp (ref "R4")
      (value "ResSMD")
      (footprint "Footprint_950322:R0805")
      (libsource (lib "MYLIB") (part "ResSMD"))
    )
    (comp (ref "R5")
      (value "ResSMD")
      (footprint "Footprint_950322:R0805")
      (libsource (lib "MYLIB") (part "ResSMD"))
    )
    (comp (ref "R6")
      (value "ResSMD")
      (footprint "Footprint_950322:R0805")
      (libsource (lib "MYLIB") (part "ResSMD"))
    )
    (comp (ref "R7")
      (value "ResSMD")
      (footprint "Footprint_950322:R0805")
      (libsource (lib "MYLIB") (part "ResSMD"))
    )
    (comp (ref "R8")
      (value "ResSMD")
      (footprint "Footprint_950322:R0805")
      (libsource (lib "MYLIB") (part "ResSMD"))
    )
    (comp (ref "R9")
      (value "ResSMD")
      (footprint "Footprint_950322:R0805")
      (libsource (lib "MYLIB") (part "ResSMD"))
    )
    (comp (ref "R10")
      (value "ResSMD")
      (footprint "Footprint_950322:R0805")
      (libsource (lib "MYLIB") (part "ResSMD"))
    )
    (comp (ref "R11")
      (value "ResSMD")
      (footprint "Footprint_950322:R0805")
      (libsource (lib "MYLIB") (part "ResSMD"))
    )
    (comp (ref "R12")
      (value "ResSMD")
      (footprint "Footprint_950322:R0805")
      (libsource (lib "MYLIB") (part "ResSMD"))
    )
    (comp (ref "R13")
      (value "ResSMD")
      (footprint "Footprint_950322:R0805")
      (libsource (lib "MYLIB") (part "ResSMD"))
    )
    (comp (ref "R14")
      (value "ResSMD")
      (footprint "Footprint_950322:R0805")
      (libsource (lib "MYLIB") (part "ResSMD"))
    )
    (comp (ref "R15")
      (value "ResSMD")
      (footprint "Footprint_950322:R0805")
      (libsource (lib "MYLIB") (part "ResSMD"))
    )
    (comp (ref "R16")
      (value "ResSMD")
      (footprint "Footprint_950322:R0805")
      (libsource (lib "MYLIB") (part "ResSMD"))
    )
    (comp (ref "R17")
      (value "ResSMD")
      (footprint "Footprint_950322:R0805")
      (libsource (lib "MYLIB") (part "ResSMD"))
    )
    (comp (ref "R18")
      (value "ResSMD")
      (footprint "Footprint_950322:R0805")
      (libsource (lib "MYLIB") (part "ResSMD"))
    )
    (comp (ref "R19")
      (value "ResSMD")
      (footprint "Footprint_950322:R0805")
      (libsource (lib "MYLIB") (part "ResSMD"))
    )
    (comp (ref "R20")
      (value "ResSMD")
      (footprint "Footprint_950322:R0805")
      (libsource (lib "MYLIB") (part "ResSMD"))
    )
    (comp (ref "R21")
      (value "ResSMD")
      (footprint "Footprint_950322:R0805")
      (libsource (lib "MYLIB") (part "ResSMD"))
    )
    (comp (ref "R22")
      (value "ResSMD")
      (footprint "Footprint_950322:R0805")
      (libsource (lib "MYLIB") (part "ResSMD"))
    )
    (comp (ref "R23")
      (value "ResSMD")
      (footprint "Footprint_950322:R0805")
      (libsource (lib "MYLIB") (part "ResSMD"))
    )
    (comp (ref "R24")
      (value "ResSMD")
      (footprint "Footprint_950322:R0805")
      (libsource (lib "MYLIB") (part "ResSMD"))
    )
    (comp (ref "R25")
      (value "ResSMD")
      (footprint "Footprint_950322:R0805")
      (libsource (lib "MYLIB") (part "ResSMD"))
    )
    (comp (ref "R26")
      (value "0 SMD")
      (footprint "Footprint_950322:R0805")
      (libsource (lib "MYLIB") (part "ResSMD"))
    )
    (comp (ref "R27")
      (value "ResSMD")
      (footprint "Footprint_950322:R0805")
      (libsource (lib "MYLIB") (part "ResSMD"))
    )
    (comp (ref "R28")
      (value "0 SMD")
      (footprint "Footprint_950322:R0805")
      (libsource (lib "MYLIB") (part "ResSMD"))
    )
    (comp (ref "R29")
      (value "ResSMD")
      (footprint "Footprint_950322:R0805")
      (libsource (lib "MYLIB") (part "ResSMD"))
    )
    (comp (ref "R30")
      (value "ResSMD")
      (footprint "Footprint_950322:R0805")
      (libsource (lib "MYLIB") (part "ResSMD"))
    )
    (comp (ref "R31")
      (value "Res3")
      (footprint "Footprint_950322:R0603")
      (description "Resistor")
      (fields (field (name "ALTIUM_VALUE") "0") (field (name "PUBLISHER") "Altium Limited"))
      (libsource (lib "Miscellaneous Devices") (part "Res3"))
    )
    (comp (ref "R32")
      (value "Res3")
      (footprint "Footprint_950322:R0603")
      (description "Resistor")
      (fields (field (name "ALTIUM_VALUE") "0") (field (name "PUBLISHER") "Altium Limited"))
      (libsource (lib "Miscellaneous Devices") (part "Res3"))
    )
    (comp (ref "R33")
      (value "ResSMD")
      (footprint "Footprint_950322:R0805")
      (libsource (lib "MYLIB") (part "ResSMD"))
    )
    (comp (ref "R34")
      (value "ResSMD")
      (footprint "Footprint_950322:R0805")
      (libsource (lib "MYLIB") (part "ResSMD"))
    )
    (comp (ref "R35")
      (value "ResSMD")
      (footprint "Footprint_950322:R0805")
      (libsource (lib "MYLIB") (part "ResSMD"))
    )
    (comp (ref "R36")
      (value "ResSMD")
      (footprint "Footprint_950322:R0805")
      (libsource (lib "MYLIB") (part "ResSMD"))
    )
    (comp (ref "R37")
      (value "ResSMD")
      (footprint "Footprint_950322:R0805")
      (libsource (lib "MYLIB") (part "ResSMD"))
    )
    (comp (ref "R38")
      (value "ResSMD")
      (footprint "Footprint_950322:R0805")
      (libsource (lib "MYLIB") (part "ResSMD"))
    )
    (comp (ref "R39")
      (value "ResSMD")
      (footprint "Footprint_950322:R0805")
      (libsource (lib "MYLIB") (part "ResSMD"))
    )
    (comp (ref "R40")
      (value "ResSMD")
      (footprint "Footprint_950322:R0805")
      (libsource (lib "MYLIB") (part "ResSMD"))
    )
    (comp (ref "R41")
      (value "ResSMD")
      (footprint "Footprint_950322:R0805")
      (libsource (lib "MYLIB") (part "ResSMD"))
    )
    (comp (ref "R42")
      (value "ResSMD")
      (footprint "Footprint_950322:R0805")
      (libsource (lib "MYLIB") (part "ResSMD"))
    )
    (comp (ref "R43")
      (value "0 SMD")
      (footprint "Footprint_950322:R0805")
      (libsource (lib "MYLIB") (part "ResSMD"))
    )
    (comp (ref "R44")
      (value "0 SMD")
      (footprint "Footprint_950322:R0805")
      (libsource (lib "MYLIB") (part "ResSMD"))
    )
    (comp (ref "R45")
      (value "ResSMD")
      (footprint "Footprint_950322:R0805")
      (libsource (lib "MYLIB") (part "ResSMD"))
    )
    (comp (ref "R46")
      (value "ResSMD")
      (footprint "Footprint_950322:R0805")
      (libsource (lib "MYLIB") (part "ResSMD"))
    )
    (comp (ref "R47")
      (value "ResSMD")
      (footprint "Footprint_950322:R0805")
      (libsource (lib "MYLIB") (part "ResSMD"))
    )
    (comp (ref "R48")
      (value "ResSMD")
      (footprint "Footprint_950322:R0805")
      (libsource (lib "MYLIB") (part "ResSMD"))
    )
    (comp (ref "R49")
      (value "ResSMD")
      (footprint "Footprint_950322:R0805")
      (libsource (lib "MYLIB") (part "ResSMD"))
    )
    (comp (ref "R50")
      (value "ResSMD")
      (footprint "Footprint_950322:R0805")
      (libsource (lib "MYLIB") (part "ResSMD"))
    )
    (comp (ref "R51")
      (value "15K")
      (footprint "Footprint_950322:R0805")
      (libsource (lib "MYLIB") (part "ResSMD"))
    )
    (comp (ref "R52")
      (value "15")
      (footprint "AXIAL-0.5")
      (description "Semiconductor Resistor")
      (fields (field (name "ALTIUM_VALUE") "0.5W") (field (name "PUBLISHER") "Altium Limited"))
      (libsource (lib "Miscellaneous Devices") (part "Res Semi"))
    )
    (comp (ref "R53")
      (value "100")
      (footprint "Footprint_950322:R0805")
      (libsource (lib "MYLIB") (part "ResSMD"))
    )
    (comp (ref "R54")
      (value "100")
      (footprint "Footprint_950322:R0805")
      (libsource (lib "MYLIB") (part "ResSMD"))
    )
    (comp (ref "R55")
      (value "Res3")
      (footprint "Footprint_950322:R0603")
      (description "Resistor")
      (fields (field (name "ALTIUM_VALUE") "0") (field (name "PUBLISHER") "Altium Limited"))
      (libsource (lib "Miscellaneous Devices") (part "Res3"))
    )
    (comp (ref "R56")
      (value "Res3")
      (footprint "Footprint_950322:R0603")
      (description "Resistor")
      (fields (field (name "ALTIUM_VALUE") "0") (field (name "PUBLISHER") "Altium Limited"))
      (libsource (lib "Miscellaneous Devices") (part "Res3"))
    )
    (comp (ref "R57")
      (value "Res3")
      (footprint "Footprint_950322:R0603")
      (description "Resistor")
      (fields (field (name "ALTIUM_VALUE") "0") (field (name "PUBLISHER") "Altium Limited"))
      (libsource (lib "Miscellaneous Devices") (part "Res3"))
    )
    (comp (ref "R58")
      (value "CMA02040X1209GB300")
      (footprint "AXIAL-0.3")
      (description "Resistor")
      (fields (field (name "ALTIUM_VALUE") "1") (field (name "PUBLISHER") "Altium Limited"))
      (libsource (lib "Miscellaneous Devices") (part "Res1"))
    )
    (comp (ref "R59")
      (value "Res3")
      (footprint "Footprint_950322:R0603")
      (description "Resistor")
      (fields (field (name "ALTIUM_VALUE") "0") (field (name "PUBLISHER") "Altium Limited"))
      (libsource (lib "Miscellaneous Devices") (part "Res3"))
    )
    (comp (ref "R60")
      (value "0")
      (footprint "Footprint_950322:R0805")
      (libsource (lib "MYLIB") (part "ResSMD"))
    )
    (comp (ref "R61")
      (value "Res1")
      (footprint "AXIAL-0.3")
      (description "Resistor")
      (fields (field (name "ALTIUM_VALUE") "1") (field (name "PUBLISHER") "Altium Limited"))
      (libsource (lib "Miscellaneous Devices") (part "Res1"))
    )
    (comp (ref "R62")
      (value "Res1")
      (footprint "AXIAL-0.3")
      (description "Resistor")
      (fields (field (name "ALTIUM_VALUE") "1") (field (name "PUBLISHER") "Altium Limited"))
      (libsource (lib "Miscellaneous Devices") (part "Res1"))
    )
    (comp (ref "R63")
      (value "Res3")
      (footprint "Footprint_950322:R0603")
      (description "Resistor")
      (fields (field (name "ALTIUM_VALUE") "0") (field (name "PUBLISHER") "Altium Limited"))
      (libsource (lib "Miscellaneous Devices") (part "Res3"))
    )
    (comp (ref "R64")
      (value "Res3")
      (footprint "Footprint_950322:R0603")
      (description "Resistor")
      (fields (field (name "ALTIUM_VALUE") "0") (field (name "PUBLISHER") "Altium Limited"))
      (libsource (lib "Miscellaneous Devices") (part "Res3"))
    )
    (comp (ref "R65")
      (value "CMA02040X1209GB300")
      (footprint "AXIAL-0.3")
      (description "Resistor")
      (fields (field (name "ALTIUM_VALUE") "1") (field (name "PUBLISHER") "Altium Limited"))
      (libsource (lib "Miscellaneous Devices") (part "Res1"))
    )
    (comp (ref "R66")
      (value "Res3")
      (footprint "J1-0603")
      (description "Resistor")
      (fields (field (name "ALTIUM_VALUE") "10K") (field (name "PUBLISHER") "Altium Limited"))
      (libsource (lib "Miscellaneous Devices") (part "Res3"))
    )
    (comp (ref "R67")
      (value "0R")
      (footprint "Footprint_950322:R0805")
      (libsource (lib "MYLIB") (part "ResSMD"))
    )
    (comp (ref "R68")
      (value "1K")
      (footprint "Footprint_950322:R0805")
      (description "resistor 1/4 wat")
      (libsource (lib "Mylib") (part "Res"))
    )
    (comp (ref "R69")
      (value "100k")
      (footprint "Footprint_950322:R0805")
      (libsource (lib "MYLIB") (part "ResSMD"))
    )
    (comp (ref "R70")
      (value "1K")
      (footprint "Footprint_950322:R0805")
      (libsource (lib "MYLIB") (part "ResSMD"))
    )
    (comp (ref "R71")
      (value "Res3")
      (footprint "J1-0603")
      (description "Resistor")
      (fields (field (name "ALTIUM_VALUE") "10K") (field (name "PUBLISHER") "Altium Limited"))
      (libsource (lib "Miscellaneous Devices") (part "Res3"))
    )
    (comp (ref "R72")
      (value "Res3")
      (footprint "Footprint_950322:R0603")
      (description "Resistor")
      (fields (field (name "ALTIUM_VALUE") "0") (field (name "PUBLISHER") "Altium Limited"))
      (libsource (lib "Miscellaneous Devices") (part "Res3"))
    )
    (comp (ref "R73")
      (value "Res3")
      (footprint "Footprint_950322:R0603")
      (description "Resistor")
      (fields (field (name "ALTIUM_VALUE") "0") (field (name "PUBLISHER") "Altium Limited"))
      (libsource (lib "Miscellaneous Devices") (part "Res3"))
    )
    (comp (ref "R74")
      (value "Res3")
      (footprint "Footprint_950322:R0603")
      (description "Resistor")
      (fields (field (name "ALTIUM_VALUE") "0") (field (name "PUBLISHER") "Altium Limited"))
      (libsource (lib "Miscellaneous Devices") (part "Res3"))
    )
    (comp (ref "R75")
      (value "300")
      (footprint "Footprint_950322:R0805")
      (libsource (lib "MYLIB") (part "ResSMD"))
    )
    (comp (ref "R76")
      (value "Res3")
      (footprint "Footprint_950322:R0603")
      (description "Resistor")
      (fields (field (name "ALTIUM_VALUE") "0") (field (name "PUBLISHER") "Altium Limited"))
      (libsource (lib "Miscellaneous Devices") (part "Res3"))
    )
    (comp (ref "R77")
      (value "300")
      (footprint "Footprint_950322:R0805")
      (libsource (lib "MYLIB") (part "ResSMD"))
    )
    (comp (ref "R78")
      (value "Res3")
      (footprint "Footprint_950322:R0603")
      (description "Resistor")
      (fields (field (name "ALTIUM_VALUE") "0") (field (name "PUBLISHER") "Altium Limited"))
      (libsource (lib "Miscellaneous Devices") (part "Res3"))
    )
    (comp (ref "R79")
      (value "Res3")
      (footprint "Footprint_950322:R0603")
      (description "Resistor")
      (fields (field (name "ALTIUM_VALUE") "0") (field (name "PUBLISHER") "Altium Limited"))
      (libsource (lib "Miscellaneous Devices") (part "Res3"))
    )
    (comp (ref "R80")
      (value "1K")
      (footprint "Footprint_950322:R0805")
      (libsource (lib "MYLIB") (part "ResSMD"))
    )
    (comp (ref "R81")
      (value "1K")
      (footprint "Footprint_950322:R0805")
      (libsource (lib "MYLIB") (part "ResSMD"))
    )
    (comp (ref "R82")
      (value "1K")
      (footprint "Footprint_950322:R0805")
      (libsource (lib "MYLIB") (part "ResSMD"))
    )
    (comp (ref "R83")
      (value "ResSMD")
      (footprint "Footprint_950322:R0805")
      (libsource (lib "MYLIB") (part "ResSMD"))
    )
    (comp (ref "R84")
      (value "ResSMD")
      (footprint "Footprint_950322:R0805")
      (libsource (lib "MYLIB") (part "ResSMD"))
    )
    (comp (ref "R85")
      (value "ResSMD")
      (footprint "Footprint_950322:R0805")
      (libsource (lib "MYLIB") (part "ResSMD"))
    )
    (comp (ref "R86")
      (value "0 SMD")
      (footprint "Footprint_950322:R0805")
      (libsource (lib "MYLIB") (part "ResSMD"))
    )
    (comp (ref "R87")
      (value "0 SMD")
      (footprint "Footprint_950322:R0805")
      (libsource (lib "MYLIB") (part "ResSMD"))
    )
    (comp (ref "R88")
      (value "ResSMD")
      (footprint "Footprint_950322:R0805")
      (libsource (lib "MYLIB") (part "ResSMD"))
    )
    (comp (ref "R89")
      (value "ResSMD")
      (footprint "Footprint_950322:R0805")
      (libsource (lib "MYLIB") (part "ResSMD"))
    )
    (comp (ref "R90")
      (value "ResSMD")
      (footprint "Footprint_950322:R0805")
      (libsource (lib "MYLIB") (part "ResSMD"))
    )
    (comp (ref "R91")
      (value "ResSMD")
      (footprint "Footprint_950322:R0805")
      (libsource (lib "MYLIB") (part "ResSMD"))
    )
    (comp (ref "R92")
      (value "0 SMD")
      (footprint "Footprint_950322:R0805")
      (libsource (lib "MYLIB") (part "ResSMD"))
    )
    (comp (ref "R93")
      (value "0 SMD")
      (footprint "Footprint_950322:R0805")
      (libsource (lib "MYLIB") (part "ResSMD"))
    )
    (comp (ref "R94")
      (value "ResSMD")
      (footprint "Footprint_950322:R0805")
      (libsource (lib "MYLIB") (part "ResSMD"))
    )
    (comp (ref "R95")
      (value "ResSMD")
      (footprint "Footprint_950322:R0805")
      (libsource (lib "MYLIB") (part "ResSMD"))
    )
    (comp (ref "R96")
      (value "15K")
      (footprint "Footprint_950322:R0805")
      (libsource (lib "MYLIB") (part "ResSMD"))
    )
    (comp (ref "R97")
      (value "ResSMD")
      (footprint "Footprint_950322:R0805")
      (libsource (lib "MYLIB") (part "ResSMD"))
    )
    (comp (ref "R98")
      (value "15K")
      (footprint "Footprint_950322:R0805")
      (libsource (lib "MYLIB") (part "ResSMD"))
    )
    (comp (ref "R99")
      (value "15K")
      (footprint "Footprint_950322:R0805")
      (libsource (lib "MYLIB") (part "ResSMD"))
    )
    (comp (ref "R100")
      (value "5K")
      (footprint "Footprint_950322:R0805")
      (libsource (lib "MYLIB") (part "ResSMD"))
    )
    (comp (ref "R101")
      (value "5K")
      (footprint "Footprint_950322:R0805")
      (libsource (lib "MYLIB") (part "ResSMD"))
    )
    (comp (ref "R102")
      (value "??")
      (footprint "AXIAL-0.5")
      (description "Semiconductor Resistor")
      (fields (field (name "ALTIUM_VALUE") "0.5W") (field (name "PUBLISHER") "Altium Limited"))
      (libsource (lib "Miscellaneous Devices") (part "Res Semi"))
    )
    (comp (ref "R103")
      (value "12")
      (footprint "AXIAL-0.5")
      (description "Semiconductor Resistor")
      (fields (field (name "ALTIUM_VALUE") "CMA02040X1209GB300") (field (name "PUBLISHER") "Altium Limited"))
      (libsource (lib "Miscellaneous Devices") (part "Res Semi"))
    )
    (comp (ref "R104")
      (value "47k")
      (footprint "AXIAL-0.3")
      (description "Resistor")
      (fields (field (name "ALTIUM_VALUE") "47k") (field (name "PUBLISHER") "Altium Limited"))
      (libsource (lib "Miscellaneous Devices") (part "Res1"))
    )
    (comp (ref "R105")
      (value "12")
      (footprint "AXIAL-0.5")
      (description "Semiconductor Resistor")
      (fields (field (name "ALTIUM_VALUE") "CMA02040X1209GB300") (field (name "PUBLISHER") "Altium Limited"))
      (libsource (lib "Miscellaneous Devices") (part "Res Semi"))
    )
    (comp (ref "R106")
      (value "??")
      (footprint "AXIAL-0.5")
      (description "Semiconductor Resistor")
      (fields (field (name "ALTIUM_VALUE") "0.5W") (field (name "PUBLISHER") "Altium Limited"))
      (libsource (lib "Miscellaneous Devices") (part "Res Semi"))
    )
    (comp (ref "R107")
      (value "??")
      (footprint "AXIAL-0.5")
      (description "Semiconductor Resistor")
      (fields (field (name "ALTIUM_VALUE") "0.5W") (field (name "PUBLISHER") "Altium Limited"))
      (libsource (lib "Miscellaneous Devices") (part "Res Semi"))
    )
    (comp (ref "R108")
      (value "??")
      (footprint "AXIAL-0.5")
      (description "Semiconductor Resistor")
      (fields (field (name "ALTIUM_VALUE") "0.5W") (field (name "PUBLISHER") "Altium Limited"))
      (libsource (lib "Miscellaneous Devices") (part "Res Semi"))
    )
    (comp (ref "R109")
      (value "??")
      (footprint "AXIAL-0.5")
      (description "Semiconductor Resistor")
      (fields (field (name "ALTIUM_VALUE") "0.5W") (field (name "PUBLISHER") "Altium Limited"))
      (libsource (lib "Miscellaneous Devices") (part "Res Semi"))
    )
    (comp (ref "R110")
      (value "??")
      (footprint "AXIAL-0.5")
      (description "Semiconductor Resistor")
      (fields (field (name "ALTIUM_VALUE") "0.5W") (field (name "PUBLISHER") "Altium Limited"))
      (libsource (lib "Miscellaneous Devices") (part "Res Semi"))
    )
    (comp (ref "R111")
      (value "??")
      (footprint "AXIAL-0.5")
      (description "Semiconductor Resistor")
      (fields (field (name "ALTIUM_VALUE") "0.5W") (field (name "PUBLISHER") "Altium Limited"))
      (libsource (lib "Miscellaneous Devices") (part "Res Semi"))
    )
    (comp (ref "R112")
      (value "??")
      (footprint "AXIAL-0.5")
      (description "Semiconductor Resistor")
      (fields (field (name "ALTIUM_VALUE") "0.5W") (field (name "PUBLISHER") "Altium Limited"))
      (libsource (lib "Miscellaneous Devices") (part "Res Semi"))
    )
    (comp (ref "R113")
      (value "??")
      (footprint "AXIAL-0.5")
      (description "Semiconductor Resistor")
      (fields (field (name "ALTIUM_VALUE") "0.5W") (field (name "PUBLISHER") "Altium Limited"))
      (libsource (lib "Miscellaneous Devices") (part "Res Semi"))
    )
    (comp (ref "R114")
      (value "??")
      (footprint "AXIAL-0.5")
      (description "Semiconductor Resistor")
      (fields (field (name "ALTIUM_VALUE") "0.5W") (field (name "PUBLISHER") "Altium Limited"))
      (libsource (lib "Miscellaneous Devices") (part "Res Semi"))
    )
    (comp (ref "R115")
      (value "Res3")
      (footprint "Footprint_950322:R0603")
      (description "Resistor")
      (fields (field (name "ALTIUM_VALUE") "0") (field (name "PUBLISHER") "Altium Limited"))
      (libsource (lib "Miscellaneous Devices") (part "Res3"))
    )
    (comp (ref "R116")
      (value "Res3")
      (footprint "Footprint_950322:R0603")
      (description "Resistor")
      (fields (field (name "ALTIUM_VALUE") "0") (field (name "PUBLISHER") "Altium Limited"))
      (libsource (lib "Miscellaneous Devices") (part "Res3"))
    )
    (comp (ref "R117")
      (value "Res3")
      (footprint "Footprint_950322:R0603")
      (description "Resistor")
      (fields (field (name "ALTIUM_VALUE") "0") (field (name "PUBLISHER") "Altium Limited"))
      (libsource (lib "Miscellaneous Devices") (part "Res3"))
    )
    (comp (ref "R118")
      (value "Res3")
      (footprint "Footprint_950322:R0603")
      (description "Resistor")
      (fields (field (name "ALTIUM_VALUE") "0") (field (name "PUBLISHER") "Altium Limited"))
      (libsource (lib "Miscellaneous Devices") (part "Res3"))
    )
    (comp (ref "R119")
      (value "Res3")
      (footprint "Footprint_950322:R0603")
      (description "Resistor")
      (fields (field (name "ALTIUM_VALUE") "0") (field (name "PUBLISHER") "Altium Limited"))
      (libsource (lib "Miscellaneous Devices") (part "Res3"))
    )
    (comp (ref "R120")
      (value "MOVS2825V420")
      (footprint "6-0805_N")
      (description "Varistor (Voltage-Sensitive Resistor)")
      (fields (field (name "PUBLISHER") "Altium Limited"))
      (libsource (lib "Miscellaneous Devices") (part "Res Varistor"))
    )
    (comp (ref "R121")
      (value "0")
      (footprint "FP-CRCW1206-e3-IPC_A")
      (description "RES Thick Film, 2kΩ, 1%, 0.25W, 100ppm/°C, 1206")
      (fields (field (name "TOLERANCE") "1%"))
      (libsource (lib "Altium Content Vault") (part "1029c3af85768c4190bb7ad29bc67b5"))
    )
    (comp (ref "R122")
      (value "15k")
      (footprint "FP-CRCW1206-e3-IPC_A")
      (description "RES Thick Film, 2kΩ, 1%, 0.25W, 100ppm/°C, 1206")
      (fields (field (name "TOLERANCE") "1%"))
      (libsource (lib "Altium Content Vault") (part "1029c3af85768c4190bb7ad29bc67b5"))
    )
    (comp (ref "R123")
      (value "100")
      (footprint "FP-CRCW1206-e3-IPC_A")
      (description "RES Thick Film, 2kΩ, 1%, 0.25W, 100ppm/°C, 1206")
      (fields (field (name "TOLERANCE") "1%"))
      (libsource (lib "Altium Content Vault") (part "1029c3af85768c4190bb7ad29bc67b5"))
    )
    (comp (ref "R124")
      (value "4.7k")
      (footprint "FP-CRCW1206-e3-IPC_A")
      (description "RES Thick Film, 2kΩ, 1%, 0.25W, 100ppm/°C, 1206")
      (fields (field (name "TOLERANCE") "1%"))
      (libsource (lib "Altium Content Vault") (part "1029c3af85768c4190bb7ad29bc67b5"))
    )
    (comp (ref "R125")
      (value "4.7k")
      (footprint "FP-CRCW1206-e3-IPC_A")
      (description "RES Thick Film, 2kΩ, 1%, 0.25W, 100ppm/°C, 1206")
      (fields (field (name "TOLERANCE") "1%"))
      (libsource (lib "Altium Content Vault") (part "1029c3af85768c4190bb7ad29bc67b5"))
    )
    (comp (ref "R126")
      (value "100")
      (footprint "FP-CRCW1206-e3-IPC_A")
      (description "RES Thick Film, 2kΩ, 1%, 0.25W, 100ppm/°C, 1206")
      (fields (field (name "TOLERANCE") "1%"))
      (libsource (lib "Altium Content Vault") (part "1029c3af85768c4190bb7ad29bc67b5"))
    )
    (comp (ref "R127")
      (value "4.7k")
      (footprint "FP-CRCW1206-e3-IPC_A")
      (description "RES Thick Film, 2kΩ, 1%, 0.25W, 100ppm/°C, 1206")
      (fields (field (name "TOLERANCE") "1%"))
      (libsource (lib "Altium Content Vault") (part "1029c3af85768c4190bb7ad29bc67b5"))
    )
    (comp (ref "R128")
      (value "4.7k")
      (footprint "FP-CRCW1206-e3-IPC_A")
      (description "RES Thick Film, 2kΩ, 1%, 0.25W, 100ppm/°C, 1206")
      (fields (field (name "TOLERANCE") "1%"))
      (libsource (lib "Altium Content Vault") (part "1029c3af85768c4190bb7ad29bc67b5"))
    )
    (comp (ref "R129")
      (value "Res1")
      (footprint "AXIAL-0.3")
      (description "Resistor")
      (fields (field (name "ALTIUM_VALUE") "15k") (field (name "PUBLISHER") "Altium Limited"))
      (libsource (lib "Miscellaneous Devices") (part "Res1"))
    )
    (comp (ref "R130")
      (value "Res3")
      (footprint "Footprint_950322:R0603")
      (description "Resistor")
      (fields (field (name "ALTIUM_VALUE") "0") (field (name "PUBLISHER") "Altium Limited"))
      (libsource (lib "Miscellaneous Devices") (part "Res3"))
    )
    (comp (ref "R131")
      (value "Res3")
      (footprint "Footprint_950322:R0603")
      (description "Resistor")
      (fields (field (name "ALTIUM_VALUE") "0") (field (name "PUBLISHER") "Altium Limited"))
      (libsource (lib "Miscellaneous Devices") (part "Res3"))
    )
    (comp (ref "R132")
      (value "5K")
      (footprint "Footprint_950322:R0805")
      (libsource (lib "MYLIB") (part "ResSMD"))
    )
    (comp (ref "R133")
      (value "5K")
      (footprint "Footprint_950322:R0805")
      (libsource (lib "MYLIB") (part "ResSMD"))
    )
    (comp (ref "R134")
      (value "RC0603JR-13820RL")
      (footprint "RESC1608X55X25LL10T15")
      (fields (field (name "MANUFACTURER") "Yageo") (field (name "RESISTANCE") "3k3"))
      (libsource (lib "Altium Content Vault") (part "RES"))
    )
    (comp (ref "R135")
      (value "RC0603JR-13820RL")
      (footprint "RESC1608X55X25LL10T15")
      (fields (field (name "MANUFACTURER") "Yageo") (field (name "RESISTANCE") "560"))
      (libsource (lib "Altium Content Vault") (part "RES"))
    )
    (comp (ref "R136")
      (value "RC0603JR-13820RL")
      (footprint "RESC1608X55X25LL10T15")
      (fields (field (name "MANUFACTURER") "Yageo") (field (name "RESISTANCE") "5k6"))
      (libsource (lib "Altium Content Vault") (part "RES"))
    )
    (comp (ref "Rj1")
      (value "ERJ-3GEY0R00V")
      (footprint "TIDA-00834_ISO-E2_PCB:0603")
      (description "RES, 0, 5%, 0.1 W, 0603")
      (fields
        (field (name "VALUEDISPLAYED") "0")
        (field (name "MANUFACTURER") "Panasonic")
        (field (name "PUBLISHER") "Texas Instruments")
      )
      (libsource (lib "Resistor_0603") (part "ERJ-3GEY0R00V"))
    )
    (comp (ref "Rj2")
      (value "ERJ-3GEY0R00V")
      (footprint "TIDA-00834_ISO-E2_PCB:0603")
      (description "RES, 0, 5%, 0.1 W, 0603")
      (fields
        (field (name "VALUEDISPLAYED") "0")
        (field (name "MANUFACTURER") "Panasonic")
        (field (name "PUBLISHER") "Texas Instruments")
      )
      (libsource (lib "Resistor_0603") (part "ERJ-3GEY0R00V"))
    )
    (comp (ref "Rj3")
      (value "ERJ-3GEY0R00V")
      (footprint "TIDA-00834_ISO-E2_PCB:0603")
      (description "RES, 0, 5%, 0.1 W, 0603")
      (fields
        (field (name "VALUEDISPLAYED") "0")
        (field (name "MANUFACTURER") "Panasonic")
        (field (name "PUBLISHER") "Texas Instruments")
      )
      (libsource (lib "Resistor_0603") (part "ERJ-3GEY0R00V"))
    )
    (comp (ref "Rj4")
      (value "ERJ-3GEY0R00V")
      (footprint "TIDA-00834_ISO-E2_PCB:0603")
      (description "RES, 0, 5%, 0.1 W, 0603")
      (fields
        (field (name "VALUEDISPLAYED") "0")
        (field (name "MANUFACTURER") "Panasonic")
        (field (name "PUBLISHER") "Texas Instruments")
      )
      (libsource (lib "Resistor_0603") (part "ERJ-3GEY0R00V"))
    )
    (comp (ref "Rj5")
      (value "ERJ-3GEY0R00V")
      (footprint "TIDA-00834_ISO-E2_PCB:0603")
      (description "RES, 0, 5%, 0.1 W, 0603")
      (fields
        (field (name "VALUEDISPLAYED") "0")
        (field (name "MANUFACTURER") "Panasonic")
        (field (name "PUBLISHER") "Texas Instruments")
      )
      (libsource (lib "Resistor_0603") (part "ERJ-3GEY0R00V"))
    )
    (comp (ref "Rj6")
      (value "ERJ-3GEY0R00V")
      (footprint "TIDA-00834_ISO-E2_PCB:0603")
      (description "RES, 0, 5%, 0.1 W, 0603")
      (fields
        (field (name "VALUEDISPLAYED") "0")
        (field (name "MANUFACTURER") "Panasonic")
        (field (name "PUBLISHER") "Texas Instruments")
      )
      (libsource (lib "Resistor_0603") (part "ERJ-3GEY0R00V"))
    )
    (comp (ref "Rj7")
      (value "ERJ-3GEY0R00V")
      (footprint "TIDA-00834_ISO-E2_PCB:0603")
      (description "RES, 0, 5%, 0.1 W, 0603")
      (fields
        (field (name "VALUEDISPLAYED") "0")
        (field (name "MANUFACTURER") "Panasonic")
        (field (name "PUBLISHER") "Texas Instruments")
      )
      (libsource (lib "Resistor_0603") (part "ERJ-3GEY0R00V"))
    )
    (comp (ref "Rj8")
      (value "ERJ-3GEY0R00V")
      (footprint "TIDA-00834_ISO-E2_PCB:0603")
      (description "RES, 0, 5%, 0.1 W, 0603")
      (fields
        (field (name "VALUEDISPLAYED") "0")
        (field (name "MANUFACTURER") "Panasonic")
        (field (name "PUBLISHER") "Texas Instruments")
      )
      (libsource (lib "Resistor_0603") (part "ERJ-3GEY0R00V"))
    )
    (comp (ref "Rj9")
      (value "ERJ-3GEY0R00V")
      (footprint "TIDA-00834_ISO-E2_PCB:0603")
      (description "RES, 0, 5%, 0.1 W, 0603")
      (fields
        (field (name "VALUEDISPLAYED") "0")
        (field (name "MANUFACTURER") "Panasonic")
        (field (name "PUBLISHER") "Texas Instruments")
      )
      (libsource (lib "Resistor_0603") (part "ERJ-3GEY0R00V"))
    )
    (comp (ref "Rj10")
      (value "ERJ-3GEY0R00V")
      (footprint "TIDA-00834_ISO-E2_PCB:0603")
      (description "RES, 0, 5%, 0.1 W, 0603")
      (fields
        (field (name "VALUEDISPLAYED") "0")
        (field (name "MANUFACTURER") "Panasonic")
        (field (name "PUBLISHER") "Texas Instruments")
      )
      (libsource (lib "Resistor_0603") (part "ERJ-3GEY0R00V"))
    )
    (comp (ref "Rj11")
      (value "ERJ-3GEY0R00V")
      (footprint "TIDA-00834_ISO-E2_PCB:0603")
      (description "RES, 0, 5%, 0.1 W, 0603")
      (fields
        (field (name "VALUEDISPLAYED") "0")
        (field (name "MANUFACTURER") "Panasonic")
        (field (name "PUBLISHER") "Texas Instruments")
      )
      (libsource (lib "Resistor_0603") (part "ERJ-3GEY0R00V"))
    )
    (comp (ref "Rj12")
      (value "ERJ-3GEY0R00V")
      (footprint "TIDA-00834_ISO-E2_PCB:0603")
      (description "RES, 0, 5%, 0.1 W, 0603")
      (fields
        (field (name "VALUEDISPLAYED") "0")
        (field (name "MANUFACTURER") "Panasonic")
        (field (name "PUBLISHER") "Texas Instruments")
      )
      (libsource (lib "Resistor_0603") (part "ERJ-3GEY0R00V"))
    )
    (comp (ref "RT1")
      (value "Resistor AS32 5R020")
      (footprint "6-0805_N")
      (description "Thermistor")
      (fields (field (name "PUBLISHER") "Altium Limited"))
      (libsource (lib "Miscellaneous Devices") (part "Res Thermal"))
    )
    (comp (ref "S1")
      (value "EB2011-CA")
      (footprint "TL36WW15050")
      (description "SPDT Subminiature Toggle Switch, Right Angle Mounting, Vertical Actuation")
      (fields (field (name "PUBLISHER") "Altium Limited"))
      (libsource (lib "Miscellaneous Devices") (part "SW-SPDT"))
    )
    (comp (ref "TP1")
      (value "Pad")
      (footprint "Footprint_950322:TP-0.5mm")
      (libsource (lib "MYLIB") (part "Con1 pin-Small"))
    )
    (comp (ref "TP2")
      (value "Pad")
      (footprint "Footprint_950322:TP-0.5mm")
      (libsource (lib "") (part "Con1 pin-Small_1"))
    )
    (comp (ref "TP3")
      (value "Pad")
      (footprint "Footprint_950322:TP-0.5mm")
      (libsource (lib "MYLIB") (part "Con1 pin-Small"))
    )
    (comp (ref "TP4")
      (value "Pad")
      (footprint "Footprint_950322:TP-0.5mm")
      (libsource (lib "MYLIB") (part "Con1 pin-Small"))
    )
    (comp (ref "TP5")
      (value "Pad")
      (footprint "Footprint_950322:TP-0.5mm")
      (libsource (lib "MYLIB") (part "Con1 pin-Small"))
    )
    (comp (ref "TP6")
      (value "Pad")
      (footprint "Footprint_950322:TP-0.5mm")
      (libsource (lib "MYLIB") (part "Con1 pin-Small"))
    )
    (comp (ref "TP7")
      (value "Pad")
      (footprint "Footprint_950322:TP-0.5mm")
      (libsource (lib "MYLIB") (part "Con1 pin-Small"))
    )
    (comp (ref "TP8")
      (value "Pad")
      (footprint "Footprint_950322:TP-0.5mm")
      (libsource (lib "MYLIB") (part "Con1 pin-Small"))
    )
    (comp (ref "TP9")
      (value "Pad")
      (footprint "Footprint_950322:TP-0.5mm")
      (libsource (lib "") (part "Con1 pin-Small_2"))
    )
    (comp (ref "TP10")
      (value "Pad")
      (footprint "Footprint_950322:TP-0.5mm")
      (libsource (lib "MYLIB") (part "Con1 pin-Small"))
    )
    (comp (ref "TP11")
      (value "Pad")
      (footprint "Footprint_950322:TP-0.5mm")
      (libsource (lib "MYLIB") (part "Con1 pin-Small"))
    )
    (comp (ref "TP12")
      (value "Pad")
      (footprint "Footprint_950322:TP-0.5mm")
      (libsource (lib "") (part "Con1 pin-Small_3"))
    )
    (comp (ref "TP13")
      (value "Pad")
      (footprint "Footprint_950322:TP-0.5mm")
      (libsource (lib "MYLIB") (part "Con1 pin-Small"))
    )
    (comp (ref "TP14")
      (value "Pad")
      (footprint "Footprint_950322:TP-0.5mm")
      (libsource (lib "") (part "Con1 pin-Small_3"))
    )
    (comp (ref "TP15")
      (value "Pad")
      (footprint "Footprint_950322:TP-0.5mm")
      (libsource (lib "MYLIB") (part "Con1 pin-Small"))
    )
    (comp (ref "TP16")
      (value "Pad")
      (footprint "Footprint_950322:TP-0.5mm")
      (libsource (lib "MYLIB") (part "Con1 pin-Small"))
    )
    (comp (ref "TP17")
      (value "Pad")
      (footprint "Footprint_950322:TP-0.5mm")
      (libsource (lib "MYLIB") (part "Con1 pin-Small"))
    )
    (comp (ref "TP18")
      (value "Pad")
      (footprint "Footprint_950322:TP-0.5mm")
      (libsource (lib "MYLIB") (part "Con1 pin-Small"))
    )
    (comp (ref "TP19")
      (value "Pad")
      (footprint "Footprint_950322:TP-0.5mm")
      (libsource (lib "") (part "Con1 pin-Small_1"))
    )
    (comp (ref "TP20")
      (value "Pad")
      (footprint "Footprint_950322:TP-0.5mm")
      (libsource (lib "") (part "Con1 pin-Small_1"))
    )
    (comp (ref "TP21")
      (value "Pad")
      (footprint "Footprint_950322:TP-0.5mm")
      (libsource (lib "") (part "Con1 pin-Small_2"))
    )
    (comp (ref "TP22")
      (value "Pad")
      (footprint "Footprint_950322:TP-0.5mm")
      (libsource (lib "MYLIB") (part "Con1 pin-Small"))
    )
    (comp (ref "TP23")
      (value "Pad")
      (footprint "Footprint_950322:TP-0.5mm")
      (libsource (lib "") (part "Con1 pin-Small_3"))
    )
    (comp (ref "TP24")
      (value "Pad")
      (footprint "Footprint_950322:TP-0.5mm")
      (libsource (lib "") (part "Con1 pin-Small_1"))
    )
    (comp (ref "TP25")
      (value "Pad")
      (footprint "Footprint_950322:TP-0.5mm")
      (libsource (lib "") (part "Con1 pin-Small_2"))
    )
    (comp (ref "TP26")
      (value "Pad")
      (footprint "Footprint_950322:TP-0.5mm")
      (libsource (lib "MYLIB") (part "Con1 pin-Small"))
    )
    (comp (ref "TP27")
      (value "Pad")
      (footprint "Footprint_950322:TP-0.5mm")
      (libsource (lib "MYLIB") (part "Con1 pin-Small"))
    )
    (comp (ref "TP28")
      (value "Pad")
      (footprint "Footprint_950322:TP-0.5mm")
      (libsource (lib "MYLIB") (part "Con1 pin-Small"))
    )
    (comp (ref "TP29")
      (value "Pad")
      (footprint "Footprint_950322:TP-0.5mm")
      (libsource (lib "MYLIB") (part "Con1 pin-Small"))
    )
    (comp (ref "TP30")
      (value "Pad")
      (footprint "Footprint_950322:TP-0.5mm")
      (libsource (lib "MYLIB") (part "Con1 pin-Small"))
    )
    (comp (ref "TP31")
      (value "Pad")
      (footprint "Footprint_950322:TP-0.5mm")
      (libsource (lib "") (part "Con1 pin-Small_3"))
    )
    (comp (ref "TP32")
      (value "Pad")
      (footprint "Footprint_950322:TP-0.5mm")
      (libsource (lib "") (part "Con1 pin-Small_3"))
    )
    (comp (ref "TP33")
      (value "Pad")
      (footprint "Footprint_950322:TP-0.5mm")
      (libsource (lib "") (part "Con1 pin-Small_1"))
    )
    (comp (ref "TP34")
      (value "Pad")
      (footprint "Footprint_950322:TP-0.5mm")
      (libsource (lib "") (part "Con1 pin-Small_1"))
    )
    (comp (ref "TP35")
      (value "Pad")
      (footprint "Footprint_950322:TP-0.5mm")
      (libsource (lib "MYLIB") (part "Con1 pin-Small"))
    )
    (comp (ref "TP36")
      (value "Pad")
      (footprint "Footprint_950322:TP-0.5mm")
      (libsource (lib "MYLIB") (part "Con1 pin-Small"))
    )
    (comp (ref "TP37")
      (value "Pad")
      (footprint "Footprint_950322:TP-0.5mm")
      (libsource (lib "MYLIB") (part "Con1 pin-Small"))
    )
    (comp (ref "TP38")
      (value "Pad")
      (footprint "Footprint_950322:TP-0.5mm")
      (libsource (lib "") (part "Con1 pin-Small_3"))
    )
    (comp (ref "TP39")
      (value "Pad")
      (footprint "Footprint_950322:TP-0.5mm")
      (libsource (lib "") (part "Con1 pin-Small_1"))
    )
    (comp (ref "TP40")
      (value "Pad")
      (footprint "Footprint_950322:TP-0.5mm")
      (libsource (lib "") (part "Con1 pin-Small_3"))
    )
    (comp (ref "TP41")
      (value "Pad")
      (footprint "Footprint_950322:TP-0.5mm")
      (libsource (lib "") (part "Con1 pin-Small_3"))
    )
    (comp (ref "TP42")
      (value "Pad")
      (footprint "Footprint_950322:TP-0.5mm")
      (libsource (lib "MYLIB") (part "Con1 pin-Small"))
    )
    (comp (ref "TP43")
      (value "Pad")
      (footprint "Footprint_950322:TP-0.5mm")
      (libsource (lib "MYLIB") (part "Con1 pin-Small"))
    )
    (comp (ref "TP44")
      (value "Pad")
      (footprint "Footprint_950322:TP-0.5mm")
      (libsource (lib "") (part "Con1 pin-Small_3"))
    )
    (comp (ref "TP45")
      (value "Pad")
      (footprint "Footprint_950322:TP-0.5mm")
      (libsource (lib "") (part "Con1 pin-Small_1"))
    )
    (comp (ref "TP46")
      (value "Pad")
      (footprint "Footprint_950322:TP-0.5mm")
      (libsource (lib "MYLIB") (part "Con1 pin-Small"))
    )
    (comp (ref "TP47")
      (value "Pad")
      (footprint "Footprint_950322:TP-0.5mm")
      (libsource (lib "MYLIB") (part "Con1 pin-Small"))
    )
    (comp (ref "TP48")
      (value "Pad")
      (footprint "Footprint_950322:TP-0.5mm")
      (libsource (lib "MYLIB") (part "Con1 pin-Small"))
    )
    (comp (ref "TP49")
      (value "Pad")
      (footprint "Footprint_950322:TP-0.5mm")
      (libsource (lib "MYLIB") (part "Con1 pin-Small"))
    )
    (comp (ref "TP50")
      (value "Pad")
      (footprint "Footprint_950322:TP-0.5mm")
      (libsource (lib "") (part "Con1 pin-Small_3"))
    )
    (comp (ref "TP51")
      (value "Pad")
      (footprint "Footprint_950322:TP-0.5mm")
      (libsource (lib "") (part "Con1 pin-Small_2"))
    )
    (comp (ref "TP52")
      (value "Pad")
      (footprint "Footprint_950322:TP-0.5mm")
      (libsource (lib "") (part "Con1 pin-Small_1"))
    )
    (comp (ref "TP53")
      (value "Pad")
      (footprint "Footprint_950322:TP-0.5mm")
      (libsource (lib "") (part "Con1 pin-Small_3"))
    )
    (comp (ref "TP54")
      (value "Pad")
      (footprint "Footprint_950322:TP-0.5mm")
      (libsource (lib "") (part "Con1 pin-Small_3"))
    )
    (comp (ref "TP55")
      (value "Pad")
      (footprint "Footprint_950322:TP-0.5mm")
      (libsource (lib "MYLIB") (part "Con1 pin-Small"))
    )
    (comp (ref "TP56")
      (value "Pad")
      (footprint "Footprint_950322:TP-0.5mm")
      (libsource (lib "MYLIB") (part "Con1 pin-Small"))
    )
    (comp (ref "TP57")
      (value "Pad")
      (footprint "Footprint_950322:TP-0.5mm")
      (libsource (lib "") (part "Con1 pin-Small_3"))
    )
    (comp (ref "TP58")
      (value "Pad")
      (footprint "Footprint_950322:TP-0.5mm")
      (libsource (lib "") (part "Con1 pin-Small_1"))
    )
    (comp (ref "TP59")
      (value "Pad")
      (footprint "Footprint_950322:TP-0.5mm")
      (libsource (lib "") (part "Con1 pin-Small_2"))
    )
    (comp (ref "Trans1")
      (value "HFBR-1522Z")
      (footprint "BCM-HFBR-2521Z-4")
      (description "The Versatile Fiber Optic Connection, 5 V, -40 to 85 degC, 6-Pin THD, RoHS, Tube")
      (fields (field (name "MANUFACTURER") "Avago"))
      (libsource (lib "") (part "HFBR-1522Z_1"))
    )
    (comp (ref "U1")
      (value "OPA27GP")
      (footprint "P0008A")
      (fields (field (name "MANUFACTURER") "Texas Instruments"))
      (libsource (lib "Altium Content Vault") (part "TI-OPA27-X8"))
    )
    (comp (ref "U2")
      (value "OPA27GP")
      (footprint "P0008A")
      (fields (field (name "MANUFACTURER") "Texas Instruments"))
      (libsource (lib "Altium Content Vault") (part "TI-OPA27-X8"))
    )
    (comp (ref "U3")
      (value "MJWI20-24S15")
      (footprint "MinMax-MJWI20")
      (libsource (lib "MYLIB") (part "MINMAX-MJWI20"))
    )
    (comp (ref "U4") (value "BNX016") (footprint "BNX016") (libsource (lib "MYLIB") (part "BNX016")))
    (comp (ref "U5")
      (value "MJWI10-12S05")
      (footprint "MinMax-MJWI20")
      (libsource (lib "MYLIB") (part "MINMAX-MJWI20"))
    )
    (comp (ref "U6")
      (value "MJWI10-12S05")
      (footprint "MinMax-MJWI20")
      (libsource (lib "MYLIB") (part "MINMAX-MJWI20"))
    )
    (comp (ref "U7")
      (value "CAS 15-NP")
      (footprint "LEM-LTSR 15-NP-10_V")
      (description "Current Transducer, 5 V, -40 to 85 degC, 10-Pin THD, RoHS, Tray")
      (fields (field (name "MANUFACTURER") "LEM") (field (name "PARTNUMBER") "LTSR 15-NP"))
      (libsource (lib "Altium Content Vault") (part "LEM-LTSR 15-NP-10"))
    )
    (comp (ref "U8")
      (value "SN74LVC1G17DBVT SOT23")
      (footprint "FP-DCK0005A-IPC_C")
      (description "IC BUF NON-INVERT 5.5V SC70-5")
      (libsource (lib "Altium Content Vault") (part "333895c48767551a2a38df23237d11a"))
    )
    (comp (ref "U9")
      (value "SI8261BBD-C-ISR")
      (footprint "SLAB-SDIP6_N")
      (fields (field (name "PARTNUMBER") "Si8261BBD-C-IS") (field (name "MANUFACTURER") "Silicon Labs"))
      (libsource (lib "Altium Content Vault") (part "SLAB-Si8261X-SDIP-6"))
    )
    (comp (ref "U10")
      (value "IXDN609SIATR")
      (footprint "IXYS-SI-8_V")
      (fields (field (name "PARTNUMBER") "IXDN609SI"))
      (libsource (lib "Altium Content Vault") (part "IXYS-IXDN609-8"))
    )
    (comp (ref "U11")
      (value "LT1764AEQ-3.3")
      (footprint "PSC-V2:TO263-5")
      (fields (field (name "MANUFACTURER") "Linear Technology"))
      (libsource (lib "Linear Technology Power Management LDO Linear Regulators") (part "LT1764AEQ-3.3"))
    )
    (comp (ref "U12")
      (value "MJWI20-12S05")
      (footprint "MinMax-MJWI20")
      (libsource (lib "MYLIB") (part "MINMAX-MJWI20"))
    )
    (comp (ref "U13")
      (value "Temp Sensor FM50")
      (footprint "Temp Sensor FM50")
      (libsource (lib "MYLIB") (part "Temp Sensor FM50"))
    )
    (comp (ref "U14")
      (value "SN74LVC1G17DBVT SOT23")
      (footprint "FP-DCK0005A-IPC_C")
      (description "IC BUF NON-INVERT 5.5V SC70-5")
      (libsource (lib "Altium Content Vault") (part "333895c48767551a2a38df23237d11a"))
    )
    (comp (ref "U15")
      (value "SN74LVC1G17DBVT SOT23")
      (footprint "FP-DCK0005A-IPC_C")
      (description "IC BUF NON-INVERT 5.5V SC70-5")
      (libsource (lib "Altium Content Vault") (part "333895c48767551a2a38df23237d11a"))
    )
    (comp (ref "U16")
      (value "PC81713NIP1B")
      (footprint "Footprint_950322:SOP-4L")
      (libsource (lib "MYLIB") (part "PC817"))
    )
    (comp (ref "U17")
      (value "PC81713NIP1B")
      (footprint "Footprint_950322:SOP-4L")
      (libsource (lib "MYLIB") (part "PC817"))
    )
    (comp (ref "U18")
      (value "AMC1311BDWV")
      (footprint "FP-DWV0008A-MFG")
      (description "IC ISOLATION 8SOIC")
      (fields
        (field (name "MANUFACTURER") "Texas Instruments")
        (field (name "OCTOPART") "https://octopart.com/amc1311bdwv-texas+instruments-88030782")
      )
      (libsource (lib "Altium Content Vault") (part "59c49c505aa37719ef898ce9673978d"))
    )
    (comp (ref "U19")
      (value "TLV2781IDBVR")
      (footprint "DBV0005A_L")
      (fields (field (name "PARTNUMBER") "OPA320AIDBVR") (field (name "MANUFACTURER") "Texas Instruments"))
      (libsource (lib "Altium Content Vault") (part "TI-OPA_SM7XXXX-DBV5"))
    )
  )
  (nets
    (net (code "1") (name "+3.3VD") (class "Default")
      (node (ref "C28") (pin "1") (pinfunction "1_1") (pintype "passive"))
      (node (ref "C32") (pin "2") (pinfunction "2_2") (pintype "passive"))
      (node (ref "C47") (pin "1") (pinfunction "1_1") (pintype "passive"))
      (node (ref "C49") (pin "2") (pinfunction "2_2") (pintype "passive"))
      (node (ref "C76") (pin "2") (pinfunction "2_2") (pintype "passive"))
      (node (ref "DS2") (pin "1") (pinfunction "A_1") (pintype "passive"))
      (node (ref "R131") (pin "2") (pinfunction "2_2") (pintype "passive"))
      (node (ref "R135") (pin "1") (pinfunction "1_1") (pintype "passive"))
      (node (ref "R83") (pin "1") (pinfunction "1_1") (pintype "passive"))
      (node (ref "R86") (pin "1") (pinfunction "1_1") (pintype "passive"))
      (node (ref "R87") (pin "1") (pinfunction "1_1") (pintype "passive"))
      (node (ref "R89") (pin "2") (pinfunction "2_2") (pintype "passive"))
      (node (ref "R91") (pin "2") (pinfunction "2_2") (pintype "passive"))
      (node (ref "R92") (pin "1") (pinfunction "1_1") (pintype "passive"))
      (node (ref "R93") (pin "1") (pinfunction "1_1") (pintype "passive"))
      (node (ref "R94") (pin "2") (pinfunction "2_2") (pintype "passive"))
      (node (ref "R95") (pin "2") (pinfunction "2_2") (pintype "passive"))
      (node (ref "R97") (pin "2") (pinfunction "2_2") (pintype "passive"))
      (node (ref "TP28") (pin "1") (pinfunction "1_1") (pintype "passive"))
      (node (ref "U11") (pin "4") (pinfunction "OUT_4") (pintype "power_in"))
      (node (ref "U11") (pin "5") (pinfunction "SENSE_5") (pintype "input"))
      (node (ref "U18") (pin "8") (pinfunction "VDD2_8") (pintype "power_in"))
      (node (ref "U19") (pin "5") (pinfunction "V+_5") (pintype "power_in"))
    )
    (net (code "2") (name "+5V_MICRO") (class "Default")
      (node (ref "C29") (pin "2") (pinfunction "2_2") (pintype "passive"))
      (node (ref "C33") (pin "2") (pinfunction "2_2") (pintype "passive"))
      (node (ref "C42") (pin "2") (pinfunction "2_2") (pintype "passive"))
      (node (ref "C48") (pin "1") (pinfunction "1_1") (pintype "passive"))
      (node (ref "C68") (pin "1") (pinfunction "1_1") (pintype "passive"))
      (node (ref "C69") (pin "1") (pinfunction "1_1") (pintype "passive"))
      (node (ref "C71") (pin "2") (pinfunction "2_2") (pintype "passive"))
      (node (ref "DS3") (pin "1") (pinfunction "A_1") (pintype "passive"))
      (node (ref "EC2") (pin "23") (pinfunction "23_23") (pintype "bidirectional"))
      (node (ref "EC2") (pin "37") (pinfunction "37_37") (pintype "bidirectional"))
      (node (ref "EC2") (pin "73") (pinfunction "73_73") (pintype "bidirectional"))
      (node (ref "EC2") (pin "9") (pinfunction "9_9") (pintype "bidirectional"))
      (node (ref "FB2") (pin "1") (pinfunction "1_1") (pintype "power_in"))
      (node (ref "J4") (pin "1") (pinfunction "1_1") (pintype "passive"))
      (node (ref "J4") (pin "14") (pinfunction "14_14") (pintype "passive"))
      (node (ref "J5") (pin "1") (pinfunction "1_1") (pintype "passive"))
      (node (ref "J5") (pin "9") (pinfunction "9_9") (pintype "passive"))
      (node (ref "OK1") (pin "4") (pinfunction "VCC_4") (pintype "power_in"))
      (node (ref "R1") (pin "1") (pinfunction "1_1") (pintype "passive"))
      (node (ref "R130") (pin "2") (pinfunction "2_2") (pintype "passive"))
      (node (ref "R134") (pin "1") (pinfunction "1_1") (pintype "passive"))
      (node (ref "R2") (pin "1") (pinfunction "1_1") (pintype "passive"))
      (node (ref "R43") (pin "2") (pinfunction "2_2") (pintype "passive"))
      (node (ref "R44") (pin "2") (pinfunction "2_2") (pintype "passive"))
      (node (ref "R57") (pin "1") (pinfunction "1_1") (pintype "passive"))
      (node (ref "R72") (pin "1") (pinfunction "1_1") (pintype "passive"))
      (node (ref "R73") (pin "1") (pinfunction "1_1") (pintype "passive"))
      (node (ref "R84") (pin "1") (pinfunction "1_1") (pintype "passive"))
      (node (ref "R88") (pin "2") (pinfunction "2_2") (pintype "passive"))
      (node (ref "R90") (pin "2") (pinfunction "2_2") (pintype "passive"))
      (node (ref "U12") (pin "3") (pinfunction "+Out_3") (pintype "passive"))
      (node (ref "U13") (pin "1") (pinfunction "VDD_1") (pintype "passive"))
      (node (ref "U18") (pin "1") (pinfunction "VDD1_1") (pintype "power_in"))
      (node (ref "U7") (pin "7") (pinfunction "+5V_7") (pintype "passive"))
    )
    (net (code "3") (name "+12V_Digital IN") (class "Default")
      (node (ref "C35") (pin "1") (pinfunction "1_1") (pintype "passive"))
      (node (ref "C36") (pin "1") (pinfunction "1_1") (pintype "passive"))
      (node (ref "C38") (pin "1") (pinfunction "1_1") (pintype "passive"))
      (node (ref "C40") (pin "1") (pinfunction "1_1") (pintype "passive"))
      (node (ref "C60") (pin "1") (pinfunction "1_1") (pintype "passive"))
      (node (ref "C61") (pin "1") (pinfunction "1_1") (pintype "passive"))
      (node (ref "CR1") (pin "2") (pinfunction "K_2") (pintype "passive"))
      (node (ref "CR2") (pin "K") (pinfunction "K_K") (pintype "passive"))
      (node (ref "D1") (pin "1") (pinfunction "A_1") (pintype "passive"))
      (node (ref "DS1") (pin "1") (pinfunction "A_1") (pintype "passive"))
      (node (ref "J1") (pin "1") (pinfunction "1_1") (pintype "passive"))
      (node (ref "J3") (pin "1") (pinfunction "1_1") (pintype "passive"))
      (node (ref "K1") (pin "A2") (pinfunction "A2_A2") (pintype "passive"))
      (node (ref "TP27") (pin "1") (pinfunction "1_1") (pintype "passive"))
      (node (ref "TP6") (pin "1") (pinfunction "1_1") (pintype "passive"))
      (node (ref "U12") (pin "1") (pinfunction "+In_1") (pintype "passive"))
      (node (ref "U3") (pin "1") (pinfunction "+In_1") (pintype "passive"))
      (node (ref "U4") (pin "2") (pinfunction "2_2") (pintype "passive"))
      (node (ref "U5") (pin "1") (pinfunction "+In_1") (pintype "passive"))
      (node (ref "U6") (pin "1") (pinfunction "+In_1") (pintype "passive"))
    )
    (net (code "4") (name "/Display-RX") (class "Default")
      (node (ref "EC2") (pin "59") (pinfunction "59_59") (pintype "bidirectional"))
      (node (ref "OK1") (pin "1") (pinfunction "VO_1") (pintype "output"))
      (node (ref "R134") (pin "2") (pinfunction "2_2") (pintype "passive"))
      (node (ref "R136") (pin "1") (pinfunction "1_1") (pintype "passive"))
    )
    (net (code "5") (name "/Display-TX") (class "Default")
      (node (ref "EC2") (pin "57") (pinfunction "57_57") (pintype "bidirectional"))
      (node (ref "Q5") (pin "1") (pinfunction "B_1") (pintype "passive"))
    )
    (net (code "6") (name "/MCU_Reset") (class "Default")
      (node (ref "EC2") (pin "1") (pinfunction "1_1") (pintype "bidirectional"))
      (node (ref "J5") (pin "2") (pinfunction "2_2") (pintype "passive"))
      (node (ref "S1") (pin "2") (pinfunction "2_2") (pintype "passive"))
    )
    (net (code "7") (name "1") (class "Default")
      (node (ref "J5") (pin "10") (pinfunction "10_10") (pintype "passive"))
      (node (ref "P4") (pin "1") (pinfunction "1_1") (pintype "passive"))
      (node (ref "Rj5") (pin "2") (pinfunction "2_2") (pintype "passive"))
    )
    (net (code "8") (name "2") (class "Default")
      (node (ref "J5") (pin "3") (pinfunction "3_3") (pintype "passive"))
      (node (ref "P4") (pin "2") (pinfunction "2_2") (pintype "passive"))
      (node (ref "Rj6") (pin "2") (pinfunction "2_2") (pintype "passive"))
    )
    (net (code "9") (name "3") (class "Default")
      (node (ref "J4") (pin "2") (pinfunction "2_2") (pintype "passive"))
      (node (ref "P4") (pin "3") (pinfunction "3_3") (pintype "passive"))
      (node (ref "Rj7") (pin "2") (pinfunction "2_2") (pintype "passive"))
    )
    (net (code "10") (name "4") (class "Default")
      (node (ref "J4") (pin "15") (pinfunction "15_15") (pintype "passive"))
      (node (ref "P4") (pin "4") (pinfunction "4_4") (pintype "passive"))
      (node (ref "Rj8") (pin "2") (pinfunction "2_2") (pintype "passive"))
    )
    (net (code "11") (name "E FB TEMP") (class "Default")
      (node (ref "EC2") (pin "97") (pinfunction "97_97") (pintype "bidirectional"))
      (node (ref "J4") (pin "6") (pinfunction "6_6") (pintype "passive"))
    )
    (net (code "12") (name "Earth") (class "Default")
      (node (ref "C70") (pin "1") (pinfunction "1_1") (pintype "passive"))
      (node (ref "C72") (pin "1") (pinfunction "1_1") (pintype "passive"))
      (node (ref "C73") (pin "1") (pinfunction "1_1") (pintype "passive"))
      (node (ref "C74") (pin "1") (pinfunction "1_1") (pintype "passive"))
      (node (ref "C75") (pin "1") (pinfunction "1_1") (pintype "passive"))
    )
    (net (code "13") (name "FB TEMP of the heatsink") (class "Default")
      (node (ref "EC2") (pin "109") (pinfunction "109_109") (pintype "bidirectional"))
      (node (ref "J4") (pin "23") (pinfunction "23_23") (pintype "passive"))
    )
    (net (code "14") (name "Fan FB command") (class "Default")
      (node (ref "EC2") (pin "18") (pinfunction "18_18") (pintype "bidirectional"))
      (node (ref "J4") (pin "16") (pinfunction "16_16") (pintype "passive"))
    )
    (net (code "15") (name "Fan command") (class "Default")
      (node (ref "EC2") (pin "60") (pinfunction "60_60") (pintype "bidirectional"))
      (node (ref "FB4") (pin "1") (pinfunction "1_1") (pintype "power_in"))
      (node (ref "J5") (pin "4") (pinfunction "4_4") (pintype "passive"))
    )
    (net (code "16") (name "GND_DIGITAL") (class "Default")
      (node (ref "C10") (pin "2") (pinfunction "2_2") (pintype "passive"))
      (node (ref "C28") (pin "2") (pinfunction "2_2") (pintype "passive"))
      (node (ref "C29") (pin "1") (pinfunction "1_1") (pintype "passive"))
      (node (ref "C3") (pin "2") (pinfunction "2_2") (pintype "passive"))
      (node (ref "C30") (pin "1") (pinfunction "1_1") (pintype "passive"))
      (node (ref "C31") (pin "1") (pinfunction "1_1") (pintype "passive"))
      (node (ref "C32") (pin "1") (pinfunction "1_1") (pintype "passive"))
      (node (ref "C33") (pin "1") (pinfunction "1_1") (pintype "passive"))
      (node (ref "C4") (pin "2") (pinfunction "2_2") (pintype "passive"))
      (node (ref "C41") (pin "1") (pinfunction "1_1") (pintype "passive"))
      (node (ref "C42") (pin "1") (pinfunction "1_1") (pintype "passive"))
      (node (ref "C47") (pin "2") (pinfunction "2_2") (pintype "passive"))
      (node (ref "C48") (pin "2") (pinfunction "2_2") (pintype "passive"))
      (node (ref "C49") (pin "1") (pinfunction "1_1") (pintype "passive"))
      (node (ref "C51") (pin "1") (pinfunction "1_1") (pintype "passive"))
      (node (ref "C55") (pin "2") (pinfunction "2_2") (pintype "passive"))
      (node (ref "C56") (pin "2") (pinfunction "2_2") (pintype "passive"))
      (node (ref "C57") (pin "2") (pinfunction "2_2") (pintype "passive"))
      (node (ref "C58") (pin "2") (pinfunction "2_2") (pintype "passive"))
      (node (ref "C59") (pin "1") (pinfunction "1_1") (pintype "passive"))
      (node (ref "C62") (pin "2") (pinfunction "2_2") (pintype "passive"))
      (node (ref "C63") (pin "2") (pinfunction "2_2") (pintype "passive"))
      (node (ref "C64") (pin "2") (pinfunction "2_2") (pintype "passive"))
      (node (ref "C65") (pin "1") (pinfunction "1_1") (pintype "passive"))
      (node (ref "C68") (pin "2") (pinfunction "2_2") (pintype "passive"))
      (node (ref "C69") (pin "2") (pinfunction "2_2") (pintype "passive"))
      (node (ref "C70") (pin "2") (pinfunction "2_2") (pintype "passive"))
      (node (ref "C71") (pin "1") (pinfunction "1_1") (pintype "passive"))
      (node (ref "C76") (pin "1") (pinfunction "1_1") (pintype "passive"))
      (node (ref "C9") (pin "2") (pinfunction "2_2") (pintype "passive"))
      (node (ref "EC2") (pin "10") (pinfunction "10_10") (pintype "bidirectional"))
      (node (ref "EC2") (pin "102") (pinfunction "102_102") (pintype "bidirectional"))
      (node (ref "EC2") (pin "105") (pinfunction "105_105") (pintype "bidirectional"))
      (node (ref "EC2") (pin "108") (pinfunction "108_108") (pintype "bidirectional"))
      (node (ref "EC2") (pin "111") (pinfunction "111_111") (pintype "bidirectional"))
      (node (ref "EC2") (pin "114") (pinfunction "114_114") (pintype "bidirectional"))
      (node (ref "EC2") (pin "24") (pinfunction "24_24") (pintype "bidirectional"))
      (node (ref "EC2") (pin "38") (pinfunction "38_38") (pintype "bidirectional"))
      (node (ref "EC2") (pin "56") (pinfunction "56_56") (pintype "bidirectional"))
      (node (ref "EC2") (pin "74") (pinfunction "74_74") (pintype "bidirectional"))
      (node (ref "EC2") (pin "75") (pinfunction "75_75") (pintype "bidirectional"))
      (node (ref "EC2") (pin "83") (pinfunction "83_83") (pintype "bidirectional"))
      (node (ref "EC2") (pin "86") (pinfunction "86_86") (pintype "bidirectional"))
      (node (ref "EC2") (pin "92") (pinfunction "92_92") (pintype "bidirectional"))
      (node (ref "EC2") (pin "99") (pinfunction "99_99") (pintype "bidirectional"))
      (node (ref "EC2") (pin "G1") (pinfunction "121_G1") (pintype "bidirectional"))
      (node (ref "EC2") (pin "G2") (pinfunction "122_G2") (pintype "bidirectional"))
      (node (ref "J4") (pin "13") (pinfunction "13_13") (pintype "passive"))
      (node (ref "J4") (pin "25") (pinfunction "25_25") (pintype "passive"))
      (node (ref "J5") (pin "15") (pinfunction "15_15") (pintype "passive"))
      (node (ref "J5") (pin "8") (pinfunction "8_8") (pintype "passive"))
      (node (ref "OK1") (pin "2") (pinfunction "GND_2") (pintype "power_in"))
      (node (ref "OK1") (pin "5") (pinfunction "NC_5") (pintype "passive"))
      (node (ref "OK1") (pin "8") (pinfunction "NC_8") (pintype "passive"))
      (node (ref "Q1") (pin "5") (pinfunction "GND2_5") (pintype "power_in"))
      (node (ref "Q2") (pin "5") (pinfunction "GND2_5") (pintype "power_in"))
      (node (ref "Q5") (pin "2") (pinfunction "E_2") (pintype "passive"))
      (node (ref "R100") (pin "2") (pinfunction "2_2") (pintype "passive"))
      (node (ref "R101") (pin "2") (pinfunction "2_2") (pintype "passive"))
      (node (ref "R129") (pin "1") (pinfunction "1_1") (pintype "passive"))
      (node (ref "R132") (pin "2") (pinfunction "2_2") (pintype "passive"))
      (node (ref "R133") (pin "2") (pinfunction "2_2") (pintype "passive"))
      (node (ref "R136") (pin "2") (pinfunction "2_2") (pintype "passive"))
      (node (ref "R26") (pin "2") (pinfunction "2_2") (pintype "passive"))
      (node (ref "R28") (pin "2") (pinfunction "2_2") (pintype "passive"))
      (node (ref "R3") (pin "2") (pinfunction "2_2") (pintype "passive"))
      (node (ref "R33") (pin "2") (pinfunction "2_2") (pintype "passive"))
      (node (ref "R34") (pin "2") (pinfunction "2_2") (pintype "passive"))
      (node (ref "R4") (pin "2") (pinfunction "2_2") (pintype "passive"))
      (node (ref "R49") (pin "2") (pinfunction "2_2") (pintype "passive"))
      (node (ref "R5") (pin "2") (pinfunction "2_2") (pintype "passive"))
      (node (ref "R50") (pin "2") (pinfunction "2_2") (pintype "passive"))
      (node (ref "R56") (pin "1") (pinfunction "1_1") (pintype "passive"))
      (node (ref "R6") (pin "2") (pinfunction "2_2") (pintype "passive"))
      (node (ref "R64") (pin "1") (pinfunction "1_1") (pintype "passive"))
      (node (ref "R66") (pin "1") (pinfunction "1_1") (pintype "passive"))
      (node (ref "R68") (pin "2") (pinfunction "2_2") (pintype "passive"))
      (node (ref "R69") (pin "1") (pinfunction "1_1") (pintype "passive"))
      (node (ref "R70") (pin "2") (pinfunction "2_2") (pintype "passive"))
      (node (ref "R71") (pin "1") (pinfunction "1_1") (pintype "passive"))
      (node (ref "R78") (pin "1") (pinfunction "1_1") (pintype "passive"))
      (node (ref "R79") (pin "1") (pinfunction "1_1") (pintype "passive"))
      (node (ref "R80") (pin "2") (pinfunction "2_2") (pintype "passive"))
      (node (ref "R81") (pin "2") (pinfunction "2_2") (pintype "passive"))
      (node (ref "R82") (pin "2") (pinfunction "2_2") (pintype "passive"))
      (node (ref "R85") (pin "2") (pinfunction "2_2") (pintype "passive"))
      (node (ref "S1") (pin "1") (pinfunction "1_1") (pintype "passive"))
      (node (ref "TP31") (pin "1") (pinfunction "1_1") (pintype "passive"))
      (node (ref "TP32") (pin "1") (pinfunction "1_1") (pintype "passive"))
      (node (ref "TP34") (pin "1") (pinfunction "1_1") (pintype "passive"))
      (node (ref "TP41") (pin "1") (pinfunction "1_1") (pintype "passive"))
      (node (ref "TP50") (pin "1") (pinfunction "1_1") (pintype "passive"))
      (node (ref "TP53") (pin "1") (pinfunction "1_1") (pintype "passive"))
      (node (ref "TP59") (pin "1") (pinfunction "1_1") (pintype "passive"))
      (node (ref "Trans1") (pin "2") (pinfunction "CATHODE_2") (pintype "passive"))
      (node (ref "Trans1") (pin "3") (pinfunction "NC_3") (pintype "passive"))
      (node (ref "Trans1") (pin "4") (pinfunction "NC_4") (pintype "passive"))
      (node (ref "Trans1") (pin "5") (pinfunction "NC_5") (pintype "passive"))
      (node (ref "Trans1") (pin "8") (pinfunction "NC_8") (pintype "passive"))
      (node (ref "U11") (pin "3") (pinfunction "GND_3") (pintype "power_in"))
      (node (ref "U11") (pin "6") (pinfunction "TAB_6") (pintype "power_in"))
      (node (ref "U12") (pin "5") (pinfunction "-Out_5") (pintype "passive"))
      (node (ref "U13") (pin "3") (pinfunction "GND_3") (pintype "passive"))
      (node (ref "U14") (pin "3") (pinfunction "GND_3") (pintype "power_in"))
      (node (ref "U15") (pin "3") (pinfunction "GND_3") (pintype "power_in"))
      (node (ref "U16") (pin "2") (pinfunction "K_2") (pintype "passive"))
      (node (ref "U17") (pin "2") (pinfunction "K_2") (pintype "passive"))
      (node (ref "U18") (pin "3") (pinfunction "SHTDN_3") (pintype "input"))
      (node (ref "U18") (pin "4") (pinfunction "GND1_4") (pintype "power_in"))
      (node (ref "U18") (pin "5") (pinfunction "GND2_5") (pintype "power_in"))
      (node (ref "U19") (pin "2") (pinfunction "V-_2") (pintype "power_in"))
      (node (ref "U7") (pin "8") (pinfunction "0V_8") (pintype "passive"))
      (node (ref "U8") (pin "3") (pinfunction "GND_3") (pintype "power_in"))
      (node (ref "U9") (pin "3") (pinfunction "CATHODE_3") (pintype "passive"))
    )
    (net (code "17") (name "GND_High voltage-out") (class "Default")
      (node (ref "C22") (pin "2") (pinfunction "2_2") (pintype "passive"))
      (node (ref "C23") (pin "2") (pinfunction "2_2") (pintype "passive"))
      (node (ref "C24") (pin "2") (pinfunction "2_2") (pintype "passive"))
      (node (ref "C25") (pin "2") (pinfunction "2_2") (pintype "passive"))
      (node (ref "C26") (pin "2") (pinfunction "2_2") (pintype "passive"))
      (node (ref "C27") (pin "2") (pinfunction "2_2") (pintype "passive"))
      (node (ref "C72") (pin "2") (pinfunction "2_2") (pintype "passive"))
      (node (ref "C78") (pin "1") (pinfunction "1_1") (pintype "passive"))
      (node (ref "CR4") (pin "1") (pinfunction "A_1") (pintype "passive"))
      (node (ref "D3") (pin "2") (pinfunction "A_2") (pintype "passive"))
      (node (ref "D9") (pin "2") (pinfunction "A_2") (pintype "passive"))
      (node (ref "P1") (pin "3") (pinfunction "3_3") (pintype "passive"))
      (node (ref "P1") (pin "4") (pinfunction "4_4") (pintype "passive"))
      (node (ref "P2") (pin "3") (pinfunction "3_3") (pintype "passive"))
      (node (ref "P2") (pin "4") (pinfunction "4_4") (pintype "passive"))
      (node (ref "R102") (pin "2") (pinfunction "2_2") (pintype "passive"))
      (node (ref "R11") (pin "1") (pinfunction "1_1") (pintype "passive"))
      (node (ref "R110") (pin "2") (pinfunction "2_2") (pintype "passive"))
      (node (ref "R111") (pin "2") (pinfunction "2_2") (pintype "passive"))
      (node (ref "R112") (pin "2") (pinfunction "2_2") (pintype "passive"))
      (node (ref "R113") (pin "2") (pinfunction "2_2") (pintype "passive"))
      (node (ref "R114") (pin "2") (pinfunction "2_2") (pintype "passive"))
      (node (ref "R116") (pin "2") (pinfunction "2_2") (pintype "passive"))
      (node (ref "R117") (pin "2") (pinfunction "2_2") (pintype "passive"))
      (node (ref "R12") (pin "1") (pinfunction "1_1") (pintype "passive"))
      (node (ref "R120") (pin "1") (pinfunction "1_1") (pintype "passive"))
      (node (ref "R13") (pin "1") (pinfunction "1_1") (pintype "passive"))
      (node (ref "R14") (pin "1") (pinfunction "1_1") (pintype "passive"))
      (node (ref "TP12") (pin "1") (pinfunction "1_1") (pintype "passive"))
      (node (ref "TP14") (pin "1") (pinfunction "1_1") (pintype "passive"))
      (node (ref "TP2") (pin "1") (pinfunction "1_1") (pintype "passive"))
      (node (ref "TP44") (pin "1") (pinfunction "1_1") (pintype "passive"))
      (node (ref "TP45") (pin "1") (pinfunction "1_1") (pintype "passive"))
    )
    (net (code "18") (name "GND_IN") (class "Default")
      (node (ref "C35") (pin "2") (pinfunction "2_2") (pintype "passive"))
      (node (ref "C36") (pin "2") (pinfunction "2_2") (pintype "passive"))
      (node (ref "C38") (pin "2") (pinfunction "2_2") (pintype "passive"))
      (node (ref "C40") (pin "2") (pinfunction "2_2") (pintype "passive"))
      (node (ref "C60") (pin "2") (pinfunction "2_2") (pintype "passive"))
      (node (ref "C61") (pin "2") (pinfunction "2_2") (pintype "passive"))
      (node (ref "C73") (pin "2") (pinfunction "2_2") (pintype "passive"))
      (node (ref "CR2") (pin "A") (pinfunction "A_A") (pintype "passive"))
      (node (ref "CR3") (pin "2") (pinfunction "K_2") (pintype "passive"))
      (node (ref "J1") (pin "2") (pinfunction "2_2") (pintype "passive"))
      (node (ref "J3") (pin "2") (pinfunction "2_2") (pintype "passive"))
      (node (ref "R51") (pin "2") (pinfunction "2_2") (pintype "passive"))
      (node (ref "TP24") (pin "1") (pinfunction "1_1") (pintype "passive"))
      (node (ref "TP33") (pin "1") (pinfunction "1_1") (pintype "passive"))
      (node (ref "TP38") (pin "1") (pinfunction "1_1") (pintype "passive"))
      (node (ref "U12") (pin "2") (pinfunction "-In_2") (pintype "passive"))
      (node (ref "U16") (pin "3") (pinfunction "E_3") (pintype "passive"))
      (node (ref "U17") (pin "3") (pinfunction "E_3") (pintype "passive"))
      (node (ref "U3") (pin "2") (pinfunction "-In_2") (pintype "passive"))
      (node (ref "U4") (pin "4") (pinfunction "4_4") (pintype "passive"))
      (node (ref "U5") (pin "2") (pinfunction "-In_2") (pintype "passive"))
      (node (ref "U6") (pin "2") (pinfunction "-In_2") (pintype "passive"))
    )
    (net (code "19") (name "GND_MB") (class "Default")
      (node (ref "C34") (pin "2") (pinfunction "2_2") (pintype "passive"))
      (node (ref "C45") (pin "1") (pinfunction "1_1") (pintype "passive"))
      (node (ref "C66") (pin "2") (pinfunction "2_2") (pintype "passive"))
      (node (ref "C67") (pin "2") (pinfunction "2_2") (pintype "passive"))
      (node (ref "CR7") (pin "1") (pinfunction "A_1") (pintype "passive"))
      (node (ref "R115") (pin "2") (pinfunction "2_2") (pintype "passive"))
      (node (ref "R63") (pin "2") (pinfunction "2_2") (pintype "passive"))
      (node (ref "R96") (pin "2") (pinfunction "2_2") (pintype "passive"))
      (node (ref "TP51") (pin "1") (pinfunction "1_1") (pintype "passive"))
      (node (ref "TP9") (pin "1") (pinfunction "1_1") (pintype "passive"))
      (node (ref "U3") (pin "5") (pinfunction "-Out_5") (pintype "passive"))
      (node (ref "U9") (pin "4") (pinfunction "GND_4") (pintype "power_in"))
    )
    (net (code "20") (name "GND_VDD Sensor voltage input") (class "Default")
      (node (ref "C37") (pin "2") (pinfunction "2_2") (pintype "passive"))
      (node (ref "C75") (pin "2") (pinfunction "2_2") (pintype "passive"))
      (node (ref "R118") (pin "1") (pinfunction "1_1") (pintype "passive"))
      (node (ref "R31") (pin "1") (pinfunction "1_1") (pintype "passive"))
      (node (ref "R99") (pin "2") (pinfunction "2_2") (pintype "passive"))
      (node (ref "TP21") (pin "1") (pinfunction "1_1") (pintype "passive"))
      (node (ref "U5") (pin "5") (pinfunction "-Out_5") (pintype "passive"))
    )
    (net (code "21") (name "GND_VDD Sensor voltage out") (class "Default")
      (node (ref "C39") (pin "2") (pinfunction "2_2") (pintype "passive"))
      (node (ref "C74") (pin "2") (pinfunction "2_2") (pintype "passive"))
      (node (ref "R119") (pin "1") (pinfunction "1_1") (pintype "passive"))
      (node (ref "R32") (pin "1") (pinfunction "1_1") (pintype "passive"))
      (node (ref "R98") (pin "2") (pinfunction "2_2") (pintype "passive"))
      (node (ref "TP25") (pin "1") (pinfunction "1_1") (pintype "passive"))
      (node (ref "U6") (pin "5") (pinfunction "-Out_5") (pintype "passive"))
    )
    (net (code "22") (name "Input 500V") (class "Default")
      (node (ref "F2") (pin "1") (pinfunction "1_1") (pintype "passive"))
      (node (ref "P1") (pin "1") (pinfunction "1_1") (pintype "passive"))
      (node (ref "P1") (pin "2") (pinfunction "2_2") (pintype "passive"))
      (node (ref "R120") (pin "2") (pinfunction "2_2") (pintype "passive"))
      (node (ref "R7") (pin "2") (pinfunction "2_2") (pintype "passive"))
      (node (ref "R8") (pin "2") (pinfunction "2_2") (pintype "passive"))
      (node (ref "TP3") (pin "1") (pinfunction "1_1") (pintype "passive"))
      (node (ref "TP42") (pin "1") (pinfunction "1_1") (pintype "passive"))
    )
    (net (code "23") (name "Input voltage of Buck") (class "Default")
      (node (ref "EC2") (pin "106") (pinfunction "106_106") (pintype "bidirectional"))
      (node (ref "FB6") (pin "2") (pinfunction "2_2") (pintype "power_in"))
      (node (ref "J5") (pin "14") (pinfunction "14_14") (pintype "passive"))
      (node (ref "TP29") (pin "1") (pinfunction "1_1") (pintype "passive"))
    )
    (net (code "24") (name "Input voltage of FB") (class "Default")
      (node (ref "EC2") (pin "103") (pinfunction "103_103") (pintype "bidirectional"))
      (node (ref "J4") (pin "24") (pinfunction "24_24") (pintype "passive"))
    )
    (net (code "25") (name "M1 FB command") (class "Default")
      (node (ref "EC2") (pin "34") (pinfunction "34_34") (pintype "bidirectional"))
      (node (ref "J4") (pin "4") (pinfunction "4_4") (pintype "passive"))
    )
    (net (code "26") (name "M1 command") (class "Default")
      (node (ref "EC2") (pin "72") (pinfunction "72_72") (pintype "bidirectional"))
      (node (ref "FB1") (pin "1") (pinfunction "1_1") (pintype "power_in"))
      (node (ref "J5") (pin "12") (pinfunction "12_12") (pintype "passive"))
      (node (ref "R101") (pin "1") (pinfunction "1_1") (pintype "passive"))
      (node (ref "TP47") (pin "1") (pinfunction "1_1") (pintype "passive"))
    )
    (net (code "27") (name "M2 FB command") (class "Default")
      (node (ref "EC2") (pin "36") (pinfunction "36_36") (pintype "bidirectional"))
      (node (ref "J4") (pin "17") (pinfunction "17_17") (pintype "passive"))
    )
    (net (code "28") (name "M3 FB command") (class "Default")
      (node (ref "EC2") (pin "40") (pinfunction "40_40") (pintype "bidirectional"))
      (node (ref "J4") (pin "5") (pinfunction "5_5") (pintype "passive"))
    )
    (net (code "29") (name "M4 FB command") (class "Default")
      (node (ref "EC2") (pin "42") (pinfunction "42_42") (pintype "bidirectional"))
      (node (ref "J4") (pin "18") (pinfunction "18_18") (pintype "passive"))
    )
    (net (code "30") (name "Net-(C1-Pad2)") (class "Default")
      (node (ref "C1") (pin "2") (pinfunction "2_2") (pintype "passive"))
      (node (ref "R15") (pin "2") (pinfunction "2_2") (pintype "passive"))
    )
    (net (code "31") (name "Net-(C2-Pad2)") (class "Default")
      (node (ref "C2") (pin "2") (pinfunction "2_2") (pintype "passive"))
      (node (ref "R16") (pin "2") (pinfunction "2_2") (pintype "passive"))
    )
    (net (code "32") (name "Net-(C13-Pad2)") (class "Default")
      (node (ref "C13") (pin "2") (pinfunction "2_2") (pintype "passive"))
      (node (ref "R45") (pin "2") (pinfunction "2_2") (pintype "passive"))
      (node (ref "R47") (pin "1") (pinfunction "1_1") (pintype "passive"))
    )
    (net (code "33") (name "Net-(C14-Pad2)") (class "Default")
      (node (ref "C14") (pin "2") (pinfunction "2_2") (pintype "passive"))
      (node (ref "R46") (pin "2") (pinfunction "2_2") (pintype "passive"))
      (node (ref "R48") (pin "1") (pinfunction "1_1") (pintype "passive"))
    )
    (net (code "34") (name "Net-(C15-Pad1)") (class "Default")
      (node (ref "C15") (pin "1") (pinfunction "1_1") (pintype "passive"))
      (node (ref "C43") (pin "1") (pinfunction "1_1") (pintype "passive"))
      (node (ref "C44") (pin "1") (pinfunction "1_1") (pintype "passive"))
      (node (ref "R52") (pin "1") (pinfunction "1_1") (pintype "passive"))
    )
    (net (code "35") (name "Net-(C16-Pad2)") (class "Default")
      (node (ref "C16") (pin "2") (pinfunction "2_2") (pintype "passive"))
      (node (ref "C17") (pin "2") (pinfunction "2_2") (pintype "passive"))
      (node (ref "C22") (pin "1") (pinfunction "1_1") (pintype "passive"))
      (node (ref "C23") (pin "1") (pinfunction "1_1") (pintype "passive"))
    )
    (net (code "36") (name "Net-(C18-Pad2)") (class "Default")
      (node (ref "C18") (pin "2") (pinfunction "2_2") (pintype "passive"))
      (node (ref "C19") (pin "2") (pinfunction "2_2") (pintype "passive"))
      (node (ref "C20") (pin "2") (pinfunction "2_2") (pintype "passive"))
      (node (ref "C21") (pin "2") (pinfunction "2_2") (pintype "passive"))
      (node (ref "C24") (pin "1") (pinfunction "1_1") (pintype "passive"))
      (node (ref "C25") (pin "1") (pinfunction "1_1") (pintype "passive"))
      (node (ref "C26") (pin "1") (pinfunction "1_1") (pintype "passive"))
      (node (ref "C27") (pin "1") (pinfunction "1_1") (pintype "passive"))
    )
    (net (code "37") (name "Net-(C50-Pad1)") (class "Default")
      (node (ref "C50") (pin "1") (pinfunction "1_1") (pintype "passive"))
      (node (ref "R127") (pin "2") (pinfunction "2_2") (pintype "passive"))
      (node (ref "R128") (pin "1") (pinfunction "1_1") (pintype "passive"))
    )
    (net (code "38") (name "Net-(C50-Pad2)") (class "Default")
      (node (ref "C50") (pin "2") (pinfunction "2_2") (pintype "passive"))
      (node (ref "R124") (pin "2") (pinfunction "2_2") (pintype "passive"))
      (node (ref "R125") (pin "1") (pinfunction "1_1") (pintype "passive"))
    )
    (net (code "39") (name "Net-(C51-Pad2)") (class "Default")
      (node (ref "C51") (pin "2") (pinfunction "2_2") (pintype "passive"))
      (node (ref "FB10") (pin "1") (pinfunction "1_1") (pintype "power_in"))
      (node (ref "R126") (pin "2") (pinfunction "2_2") (pintype "passive"))
      (node (ref "TP56") (pin "1") (pinfunction "1_1") (pintype "passive"))
    )
    (net (code "40") (name "Net-(C52-Pad2)") (class "Default")
      (node (ref "C52") (pin "2") (pinfunction "2_2") (pintype "passive"))
      (node (ref "R114") (pin "1") (pinfunction "1_1") (pintype "passive"))
    )
    (net (code "41") (name "Net-(C77-Pad1)") (class "Default")
      (node (ref "C77") (pin "1") (pinfunction "1_1") (pintype "passive"))
      (node (ref "R102") (pin "1") (pinfunction "1_1") (pintype "passive"))
    )
    (net (code "42") (name "Net-(CR1-A)") (class "Default")
      (node (ref "CR1") (pin "1") (pinfunction "A_1") (pintype "passive"))
      (node (ref "CR3") (pin "1") (pinfunction "A_1") (pintype "passive"))
    )
    (net (code "43") (name "Net-(CR4-K)") (class "Default")
      (node (ref "CR4") (pin "2") (pinfunction "K_2") (pintype "passive"))
      (node (ref "CR5") (pin "2") (pinfunction "K_2") (pintype "passive"))
    )
    (net (code "44") (name "Net-(CR5-A)") (class "Default")
      (node (ref "CR5") (pin "1") (pinfunction "A_1") (pintype "passive"))
      (node (ref "F2") (pin "2") (pinfunction "2_2") (pintype "passive"))
      (node (ref "K1") (pin "14") (pinfunction "14_14") (pintype "passive"))
      (node (ref "RT1") (pin "2") (pinfunction "2_2") (pintype "passive"))
    )
    (net (code "45") (name "Net-(CR6-A)") (class "Default")
      (node (ref "CR6") (pin "1") (pinfunction "A_1") (pintype "passive"))
      (node (ref "CR7") (pin "2") (pinfunction "K_2") (pintype "passive"))
      (node (ref "R104") (pin "2") (pinfunction "2_2") (pintype "passive"))
      (node (ref "R61") (pin "1") (pinfunction "1_1") (pintype "passive"))
      (node (ref "TP49") (pin "1") (pinfunction "1_1") (pintype "passive"))
      (node (ref "U9") (pin "5") (pinfunction "VO_5") (pintype "output"))
    )
    (net (code "46") (name "Net-(CR8-A)") (class "Default")
      (node (ref "C15") (pin "2") (pinfunction "2_2") (pintype "passive"))
      (node (ref "C43") (pin "2") (pinfunction "2_2") (pintype "passive"))
      (node (ref "C44") (pin "2") (pinfunction "2_2") (pintype "passive"))
      (node (ref "C52") (pin "1") (pinfunction "1_1") (pintype "passive"))
      (node (ref "C53") (pin "2") (pinfunction "2_2") (pintype "passive"))
      (node (ref "C54") (pin "2") (pinfunction "2_2") (pintype "passive"))
      (node (ref "C77") (pin "2") (pinfunction "2_2") (pintype "passive"))
      (node (ref "CR8") (pin "1") (pinfunction "A_1") (pintype "passive"))
      (node (ref "D10") (pin "A") (pinfunction "A_A") (pintype "passive"))
      (node (ref "D11") (pin "A") (pinfunction "A_A") (pintype "passive"))
      (node (ref "D2") (pin "A") (pinfunction "A_A") (pintype "passive"))
      (node (ref "D3") (pin "1") (pinfunction "C_1") (pintype "passive"))
      (node (ref "D7") (pin "A") (pinfunction "A_A") (pintype "passive"))
      (node (ref "D9") (pin "1") (pinfunction "C_1") (pintype "passive"))
      (node (ref "L3") (pin "1") (pinfunction "1_1") (pintype "passive"))
      (node (ref "Q3") (pin "3") (pinfunction "SOURCE_3") (pintype "passive"))
      (node (ref "Q4") (pin "3") (pinfunction "SOURCE_3") (pintype "passive"))
      (node (ref "R104") (pin "1") (pinfunction "1_1") (pintype "passive"))
      (node (ref "R115") (pin "1") (pinfunction "1_1") (pintype "passive"))
      (node (ref "R53") (pin "2") (pinfunction "2_2") (pintype "passive"))
      (node (ref "R54") (pin "2") (pinfunction "2_2") (pintype "passive"))
      (node (ref "R63") (pin "1") (pinfunction "1_1") (pintype "passive"))
      (node (ref "U10") (pin "4") (pinfunction "GND_4") (pintype "power_in"))
      (node (ref "U10") (pin "5") (pinfunction "GND_5") (pintype "power_in"))
    )
    (net (code "47") (name "Net-(CR8-K)") (class "Default")
      (node (ref "CR8") (pin "2") (pinfunction "K_2") (pintype "passive"))
      (node (ref "CR9") (pin "1") (pinfunction "A_1") (pintype "passive"))
      (node (ref "D12") (pin "C") (pinfunction "C_C") (pintype "passive"))
      (node (ref "D8") (pin "C") (pinfunction "C_C") (pintype "passive"))
      (node (ref "R58") (pin "1") (pinfunction "1_1") (pintype "passive"))
      (node (ref "R65") (pin "1") (pinfunction "1_1") (pintype "passive"))
      (node (ref "TP52") (pin "1") (pinfunction "1_1") (pintype "passive"))
      (node (ref "U10") (pin "6") (pinfunction "OUT_6") (pintype "output"))
      (node (ref "U10") (pin "7") (pinfunction "OUT_7") (pintype "output"))
    )
    (net (code "48") (name "Net-(D1-K)") (class "Default")
      (node (ref "D1") (pin "2") (pinfunction "K_2") (pintype "passive"))
      (node (ref "D5") (pin "2") (pinfunction "K_2") (pintype "passive"))
    )
    (net (code "49") (name "Net-(D4-A)") (class "Default")
      (node (ref "D4") (pin "1") (pinfunction "A_1") (pintype "passive"))
      (node (ref "P3") (pin "1") (pinfunction "1_1") (pintype "passive"))
    )
    (net (code "50") (name "Net-(D4-K)") (class "Default")
      (node (ref "D4") (pin "2") (pinfunction "K_2") (pintype "passive"))
      (node (ref "D6") (pin "2") (pinfunction "K_2") (pintype "passive"))
    )
    (net (code "51") (name "Net-(D6-A)") (class "Default")
      (node (ref "D6") (pin "1") (pinfunction "A_1") (pintype "passive"))
      (node (ref "P3") (pin "2") (pinfunction "2_2") (pintype "passive"))
    )
    (net (code "52") (name "Net-(D12-PadA)") (class "Default")
      (node (ref "D12") (pin "A") (pinfunction "A_A") (pintype "passive"))
      (node (ref "D8") (pin "A") (pinfunction "A_A") (pintype "passive"))
      (node (ref "R103") (pin "1") (pinfunction "1_1") (pintype "passive"))
      (node (ref "R105") (pin "1") (pinfunction "1_1") (pintype "passive"))
    )
    (net (code "53") (name "Net-(DS1-K)") (class "Default")
      (node (ref "DS1") (pin "2") (pinfunction "K_2") (pintype "passive"))
      (node (ref "R51") (pin "1") (pinfunction "1_1") (pintype "passive"))
    )
    (net (code "54") (name "Net-(DS2-K)") (class "Default")
      (node (ref "DS2") (pin "2") (pinfunction "K_2") (pintype "passive"))
      (node (ref "R68") (pin "1") (pinfunction "1_1") (pintype "passive"))
    )
    (net (code "55") (name "Net-(DS3-K)") (class "Default")
      (node (ref "DS3") (pin "2") (pinfunction "K_2") (pintype "passive"))
      (node (ref "R70") (pin "1") (pinfunction "1_1") (pintype "passive"))
    )
    (net (code "56") (name "Net-(DS4-A)") (class "Default")
      (node (ref "DS4") (pin "1") (pinfunction "A_1") (pintype "passive"))
      (node (ref "R75") (pin "1") (pinfunction "1_1") (pintype "passive"))
      (node (ref "U14") (pin "4") (pinfunction "Y_4") (pintype "output"))
    )
    (net (code "57") (name "Net-(DS4-K)") (class "Default")
      (node (ref "DS4") (pin "2") (pinfunction "K_2") (pintype "passive"))
      (node (ref "R80") (pin "1") (pinfunction "1_1") (pintype "passive"))
    )
    (net (code "58") (name "Net-(DS5-A)") (class "Default")
      (node (ref "DS5") (pin "1") (pinfunction "A_1") (pintype "passive"))
      (node (ref "R77") (pin "1") (pinfunction "1_1") (pintype "passive"))
      (node (ref "TP37") (pin "1") (pinfunction "1_1") (pintype "passive"))
      (node (ref "U15") (pin "4") (pinfunction "Y_4") (pintype "output"))
    )
    (net (code "59") (name "Net-(DS5-K)") (class "Default")
      (node (ref "DS5") (pin "2") (pinfunction "K_2") (pintype "passive"))
      (node (ref "R81") (pin "1") (pinfunction "1_1") (pintype "passive"))
    )
    (net (code "60") (name "Net-(DS6-A)") (class "Default")
      (node (ref "DS6") (pin "1") (pinfunction "A_1") (pintype "passive"))
      (node (ref "R60") (pin "1") (pinfunction "1_1") (pintype "passive"))
      (node (ref "TP48") (pin "1") (pinfunction "1_1") (pintype "passive"))
      (node (ref "U8") (pin "4") (pinfunction "Y_4") (pintype "output"))
    )
    (net (code "61") (name "Net-(DS6-K)") (class "Default")
      (node (ref "DS6") (pin "2") (pinfunction "K_2") (pintype "passive"))
      (node (ref "R82") (pin "1") (pinfunction "1_1") (pintype "passive"))
    )
    (net (code "62") (name "Net-(DS7-K)") (class "Default")
      (node (ref "DS7") (pin "2") (pinfunction "K_2") (pintype "passive"))
      (node (ref "R96") (pin "1") (pinfunction "1_1") (pintype "passive"))
    )
    (net (code "63") (name "Net-(DS8-K)") (class "Default")
      (node (ref "DS8") (pin "2") (pinfunction "K_2") (pintype "passive"))
      (node (ref "R98") (pin "1") (pinfunction "1_1") (pintype "passive"))
    )
    (net (code "64") (name "Net-(DS9-K)") (class "Default")
      (node (ref "DS9") (pin "2") (pinfunction "K_2") (pintype "passive"))
      (node (ref "R99") (pin "1") (pinfunction "1_1") (pintype "passive"))
    )
    (net (code "65") (name "Net-(EC2-Pad64)") (class "Default")
      (node (ref "EC2") (pin "64") (pinfunction "64_64") (pintype "bidirectional"))
      (node (ref "Rj1") (pin "2") (pinfunction "2_2") (pintype "passive"))
    )
    (net (code "66") (name "Net-(EC2-Pad65)") (class "Default")
      (node (ref "EC2") (pin "65") (pinfunction "65_65") (pintype "bidirectional"))
      (node (ref "Rj5") (pin "1") (pinfunction "1_1") (pintype "passive"))
    )
    (net (code "67") (name "Net-(EC2-Pad66)") (class "Default")
      (node (ref "EC2") (pin "66") (pinfunction "66_66") (pintype "bidirectional"))
      (node (ref "Rj2") (pin "2") (pinfunction "2_2") (pintype "passive"))
    )
    (net (code "68") (name "Net-(EC2-Pad67)") (class "Default")
      (node (ref "EC2") (pin "67") (pinfunction "67_67") (pintype "bidirectional"))
      (node (ref "Rj6") (pin "1") (pinfunction "1_1") (pintype "passive"))
    )
    (net (code "69") (name "Net-(EC2-Pad68)") (class "Default")
      (node (ref "EC2") (pin "68") (pinfunction "68_68") (pintype "bidirectional"))
      (node (ref "Rj3") (pin "2") (pinfunction "2_2") (pintype "passive"))
    )
    (net (code "70") (name "Net-(EC2-Pad69)") (class "Default")
      (node (ref "EC2") (pin "69") (pinfunction "69_69") (pintype "bidirectional"))
      (node (ref "Rj7") (pin "1") (pinfunction "1_1") (pintype "passive"))
    )
    (net (code "71") (name "Net-(EC2-Pad70)") (class "Default")
      (node (ref "EC2") (pin "70") (pinfunction "70_70") (pintype "bidirectional"))
      (node (ref "Rj4") (pin "2") (pinfunction "2_2") (pintype "passive"))
    )
    (net (code "72") (name "Net-(EC2-Pad71)") (class "Default")
      (node (ref "EC2") (pin "71") (pinfunction "71_71") (pintype "bidirectional"))
      (node (ref "Rj8") (pin "1") (pinfunction "1_1") (pintype "passive"))
    )
    (net (code "73") (name "Net-(EC2-Pad94)") (class "Default")
      (node (ref "EC2") (pin "94") (pinfunction "94_94") (pintype "bidirectional"))
      (node (ref "Rj9") (pin "2") (pinfunction "2_2") (pintype "passive"))
    )
    (net (code "74") (name "Net-(EC2-Pad95)") (class "Default")
      (node (ref "EC2") (pin "95") (pinfunction "95_95") (pintype "bidirectional"))
      (node (ref "Rj10") (pin "1") (pinfunction "1_1") (pintype "passive"))
    )
    (net (code "75") (name "Net-(EC2-Pad96)") (class "Default")
      (node (ref "EC2") (pin "96") (pinfunction "96_96") (pintype "bidirectional"))
      (node (ref "Rj11") (pin "2") (pinfunction "2_2") (pintype "passive"))
    )
    (net (code "76") (name "Net-(EC2-Pad100)") (class "Default")
      (node (ref "EC2") (pin "100") (pinfunction "100_100") (pintype "bidirectional"))
      (node (ref "Rj12") (pin "2") (pinfunction "2_2") (pintype "passive"))
    )
    (net (code "77") (name "Net-(F3-Pad1)") (class "Default")
      (node (ref "F3") (pin "1") (pinfunction "1_1") (pintype "passive"))
      (node (ref "U7") (pin "4") (pinfunction "OUT_4") (pintype "passive"))
      (node (ref "U7") (pin "5") (pinfunction "OUT_5") (pintype "passive"))
      (node (ref "U7") (pin "6") (pinfunction "OUT_6") (pintype "passive"))
    )
    (net (code "78") (name "Net-(F3-Pad2)") (class "Default")
      (node (ref "F3") (pin "2") (pinfunction "2_2") (pintype "passive"))
      (node (ref "P2") (pin "1") (pinfunction "1_1") (pintype "passive"))
      (node (ref "P2") (pin "2") (pinfunction "2_2") (pintype "passive"))
    )
    (net (code "79") (name "Net-(FB1-Pad2)") (class "Default")
      (node (ref "FB1") (pin "2") (pinfunction "2_2") (pintype "power_in"))
      (node (ref "R133") (pin "1") (pinfunction "1_1") (pintype "passive"))
      (node (ref "R59") (pin "1") (pinfunction "1_1") (pintype "passive"))
    )
    (net (code "80") (name "Net-(FB3-Pad2)") (class "Default")
      (node (ref "FB3") (pin "2") (pinfunction "2_2") (pintype "power_in"))
      (node (ref "R67") (pin "2") (pinfunction "2_2") (pintype "passive"))
    )
    (net (code "81") (name "Net-(FB4-Pad2)") (class "Default")
      (node (ref "FB4") (pin "2") (pinfunction "2_2") (pintype "power_in"))
      (node (ref "R74") (pin "1") (pinfunction "1_1") (pintype "passive"))
    )
    (net (code "82") (name "Net-(FB5-Pad2)") (class "Default")
      (node (ref "FB5") (pin "2") (pinfunction "2_2") (pintype "power_in"))
      (node (ref "R76") (pin "1") (pinfunction "1_1") (pintype "passive"))
    )
    (net (code "83") (name "Net-(FB6-Pad1)") (class "Default")
      (node (ref "FB6") (pin "1") (pinfunction "1_1") (pintype "power_in"))
      (node (ref "R47") (pin "2") (pinfunction "2_2") (pintype "passive"))
      (node (ref "R49") (pin "1") (pinfunction "1_1") (pintype "passive"))
    )
    (net (code "84") (name "Net-(FB7-Pad1)") (class "Default")
      (node (ref "FB7") (pin "1") (pinfunction "1_1") (pintype "power_in"))
      (node (ref "R48") (pin "2") (pinfunction "2_2") (pintype "passive"))
      (node (ref "R50") (pin "1") (pinfunction "1_1") (pintype "passive"))
    )
    (net (code "85") (name "Net-(FB8-Pad1)") (class "Default")
      (node (ref "FB8") (pin "1") (pinfunction "1_1") (pintype "power_in"))
      (node (ref "R67") (pin "1") (pinfunction "1_1") (pintype "passive"))
      (node (ref "R69") (pin "2") (pinfunction "2_2") (pintype "passive"))
    )
    (net (code "86") (name "Net-(FB9-Pad1)") (class "Default")
      (node (ref "FB9") (pin "1") (pinfunction "1_1") (pintype "power_in"))
      (node (ref "P3") (pin "4") (pinfunction "4_4") (pintype "passive"))
      (node (ref "R85") (pin "1") (pinfunction "1_1") (pintype "passive"))
    )
    (net (code "87") (name "Net-(J6-Pad2)") (class "Default")
      (node (ref "J6") (pin "2") (pinfunction "2_2") (pintype "passive"))
      (node (ref "U7") (pin "1") (pinfunction "IN_1") (pintype "passive"))
      (node (ref "U7") (pin "2") (pinfunction "IN_2") (pintype "passive"))
      (node (ref "U7") (pin "3") (pinfunction "IN_3") (pintype "passive"))
    )
    (net (code "88") (name "Net-(P3-Pad3)") (class "Default")
      (node (ref "P3") (pin "3") (pinfunction "3_3") (pintype "passive"))
      (node (ref "R83") (pin "2") (pinfunction "2_2") (pintype "passive"))
      (node (ref "R84") (pin "2") (pinfunction "2_2") (pintype "passive"))
    )
    (net (code "89") (name "Net-(Q1-GND1)") (class "Default")
      (node (ref "C5") (pin "2") (pinfunction "2_2") (pintype "passive"))
      (node (ref "C6") (pin "2") (pinfunction "2_2") (pintype "passive"))
      (node (ref "Q1") (pin "4") (pinfunction "GND1_4") (pintype "power_in"))
      (node (ref "R117") (pin "1") (pinfunction "1_1") (pintype "passive"))
      (node (ref "R118") (pin "2") (pinfunction "2_2") (pintype "passive"))
    )
    (net (code "90") (name "Net-(Q1-SHDN)") (class "Default")
      (node (ref "Q1") (pin "3") (pinfunction "SHDN_3") (pintype "input"))
      (node (ref "R31") (pin "2") (pinfunction "2_2") (pintype "passive"))
    )
    (net (code "91") (name "Net-(Q1-VDD2)") (class "Default")
      (node (ref "C3") (pin "1") (pinfunction "1_1") (pintype "passive"))
      (node (ref "C58") (pin "1") (pinfunction "1_1") (pintype "passive"))
      (node (ref "Q1") (pin "8") (pinfunction "VDD2_8") (pintype "power_in"))
      (node (ref "R88") (pin "1") (pinfunction "1_1") (pintype "passive"))
      (node (ref "R89") (pin "1") (pinfunction "1_1") (pintype "passive"))
      (node (ref "TP8") (pin "1") (pinfunction "1_1") (pintype "passive"))
    )
    (net (code "92") (name "Net-(Q1-VIN)") (class "Default")
      (node (ref "C5") (pin "1") (pinfunction "1_1") (pintype "passive"))
      (node (ref "Q1") (pin "2") (pinfunction "VIN_2") (pintype "power_in"))
      (node (ref "R11") (pin "2") (pinfunction "2_2") (pintype "passive"))
      (node (ref "R12") (pin "2") (pinfunction "2_2") (pintype "passive"))
      (node (ref "R7") (pin "1") (pinfunction "1_1") (pintype "passive"))
      (node (ref "R8") (pin "1") (pinfunction "1_1") (pintype "passive"))
      (node (ref "TP7") (pin "1") (pinfunction "1_1") (pintype "passive"))
    )
    (net (code "93") (name "Net-(Q1-VOUT+)") (class "Default")
      (node (ref "Q1") (pin "7") (pinfunction "VOUT+_7") (pintype "passive"))
      (node (ref "R15") (pin "1") (pinfunction "1_1") (pintype "passive"))
      (node (ref "R21") (pin "2") (pinfunction "2_2") (pintype "passive"))
      (node (ref "TP13") (pin "1") (pinfunction "1_1") (pintype "passive"))
    )
    (net (code "94") (name "Net-(Q1-VOUT-)") (class "Default")
      (node (ref "C1") (pin "1") (pinfunction "1_1") (pintype "passive"))
      (node (ref "Q1") (pin "6") (pinfunction "VOUT-_6") (pintype "passive"))
      (node (ref "R22") (pin "2") (pinfunction "2_2") (pintype "passive"))
      (node (ref "R25") (pin "1") (pinfunction "1_1") (pintype "passive"))
      (node (ref "TP18") (pin "1") (pinfunction "1_1") (pintype "passive"))
    )
    (net (code "95") (name "Net-(Q2-GND1)") (class "Default")
      (node (ref "C7") (pin "2") (pinfunction "2_2") (pintype "passive"))
      (node (ref "C8") (pin "2") (pinfunction "2_2") (pintype "passive"))
      (node (ref "Q2") (pin "4") (pinfunction "GND1_4") (pintype "power_in"))
      (node (ref "R116") (pin "1") (pinfunction "1_1") (pintype "passive"))
      (node (ref "R119") (pin "2") (pinfunction "2_2") (pintype "passive"))
    )
    (net (code "96") (name "Net-(Q2-SHDN)") (class "Default")
      (node (ref "Q2") (pin "3") (pinfunction "SHDN_3") (pintype "input"))
      (node (ref "R32") (pin "2") (pinfunction "2_2") (pintype "passive"))
    )
    (net (code "97") (name "Net-(Q2-VDD2)") (class "Default")
      (node (ref "C4") (pin "1") (pinfunction "1_1") (pintype "passive"))
      (node (ref "C57") (pin "1") (pinfunction "1_1") (pintype "passive"))
      (node (ref "Q2") (pin "8") (pinfunction "VDD2_8") (pintype "power_in"))
      (node (ref "R90") (pin "1") (pinfunction "1_1") (pintype "passive"))
      (node (ref "R91") (pin "1") (pinfunction "1_1") (pintype "passive"))
    )
    (net (code "98") (name "Net-(Q2-VIN)") (class "Default")
      (node (ref "C7") (pin "1") (pinfunction "1_1") (pintype "passive"))
      (node (ref "Q2") (pin "2") (pinfunction "VIN_2") (pintype "power_in"))
      (node (ref "R10") (pin "1") (pinfunction "1_1") (pintype "passive"))
      (node (ref "R13") (pin "2") (pinfunction "2_2") (pintype "passive"))
      (node (ref "R14") (pin "2") (pinfunction "2_2") (pintype "passive"))
      (node (ref "R9") (pin "1") (pinfunction "1_1") (pintype "passive"))
      (node (ref "TP11") (pin "1") (pinfunction "1_1") (pintype "passive"))
    )
    (net (code "99") (name "Net-(Q2-VOUT+)") (class "Default")
      (node (ref "Q2") (pin "7") (pinfunction "VOUT+_7") (pintype "passive"))
      (node (ref "R16") (pin "1") (pinfunction "1_1") (pintype "passive"))
      (node (ref "R23") (pin "2") (pinfunction "2_2") (pintype "passive"))
      (node (ref "TP15") (pin "1") (pinfunction "1_1") (pintype "passive"))
    )
    (net (code "100") (name "Net-(Q2-VOUT-)") (class "Default")
      (node (ref "C2") (pin "1") (pinfunction "1_1") (pintype "passive"))
      (node (ref "Q2") (pin "6") (pinfunction "VOUT-_6") (pintype "passive"))
      (node (ref "R24") (pin "2") (pinfunction "2_2") (pintype "passive"))
      (node (ref "R27") (pin "1") (pinfunction "1_1") (pintype "passive"))
      (node (ref "TP17") (pin "1") (pinfunction "1_1") (pintype "passive"))
    )
    (net (code "101") (name "Net-(Q3-DRAIN)") (class "Default")
      (node (ref "C16") (pin "1") (pinfunction "1_1") (pintype "passive"))
      (node (ref "C17") (pin "1") (pinfunction "1_1") (pintype "passive"))
      (node (ref "C78") (pin "2") (pinfunction "2_2") (pintype "passive"))
      (node (ref "D7") (pin "C") (pinfunction "C_C") (pintype "passive"))
      (node (ref "K1") (pin "11") (pinfunction "11_11") (pintype "passive"))
      (node (ref "Q3") (pin "2") (pinfunction "DRAIN_2") (pintype "passive"))
      (node (ref "Q4") (pin "2") (pinfunction "DRAIN_2") (pintype "passive"))
      (node (ref "R106") (pin "1") (pinfunction "1_1") (pintype "passive"))
      (node (ref "R107") (pin "1") (pinfunction "1_1") (pintype "passive"))
      (node (ref "R52") (pin "2") (pinfunction "2_2") (pintype "passive"))
      (node (ref "RT1") (pin "1") (pinfunction "1_1") (pintype "passive"))
      (node (ref "TP43") (pin "1") (pinfunction "1_1") (pintype "passive"))
    )
    (net (code "102") (name "Net-(Q3-GATE)") (class "Default")
      (node (ref "D10") (pin "C") (pinfunction "C_C") (pintype "passive"))
      (node (ref "D11") (pin "C") (pinfunction "C_C") (pintype "passive"))
      (node (ref "D2") (pin "C") (pinfunction "C_C") (pintype "passive"))
      (node (ref "Q3") (pin "1") (pinfunction "GATE_1") (pintype "passive"))
      (node (ref "Q4") (pin "1") (pinfunction "GATE_1") (pintype "passive"))
      (node (ref "R103") (pin "2") (pinfunction "2_2") (pintype "passive"))
      (node (ref "R105") (pin "2") (pinfunction "2_2") (pintype "passive"))
      (node (ref "R53") (pin "1") (pinfunction "1_1") (pintype "passive"))
      (node (ref "R54") (pin "1") (pinfunction "1_1") (pintype "passive"))
      (node (ref "R62") (pin "2") (pinfunction "2_2") (pintype "passive"))
    )
    (net (code "103") (name "Net-(Q5-C)") (class "Default")
      (node (ref "Q5") (pin "3") (pinfunction "C_3") (pintype "passive"))
      (node (ref "R135") (pin "2") (pinfunction "2_2") (pintype "passive"))
      (node (ref "Trans1") (pin "1") (pinfunction "ANODE_1") (pintype "passive"))
    )
    (net (code "104") (name "Net-(R17-Pad1)") (class "Default")
      (node (ref "R17") (pin "1") (pinfunction "1_1") (pintype "passive"))
      (node (ref "R18") (pin "2") (pinfunction "2_2") (pintype "passive"))
    )
    (net (code "105") (name "Net-(R18-Pad1)") (class "Default")
      (node (ref "R18") (pin "1") (pinfunction "1_1") (pintype "passive"))
      (node (ref "R26") (pin "1") (pinfunction "1_1") (pintype "passive"))
      (node (ref "R29") (pin "1") (pinfunction "1_1") (pintype "passive"))
    )
    (net (code "106") (name "Net-(R19-Pad1)") (class "Default")
      (node (ref "R19") (pin "1") (pinfunction "1_1") (pintype "passive"))
      (node (ref "R20") (pin "2") (pinfunction "2_2") (pintype "passive"))
    )
    (net (code "107") (name "Net-(R20-Pad1)") (class "Default")
      (node (ref "R20") (pin "1") (pinfunction "1_1") (pintype "passive"))
      (node (ref "R28") (pin "1") (pinfunction "1_1") (pintype "passive"))
      (node (ref "R30") (pin "1") (pinfunction "1_1") (pintype "passive"))
    )
    (net (code "108") (name "Net-(R29-Pad2)") (class "Default")
      (node (ref "R29") (pin "2") (pinfunction "2_2") (pintype "passive"))
      (node (ref "R36") (pin "1") (pinfunction "1_1") (pintype "passive"))
      (node (ref "R43") (pin "1") (pinfunction "1_1") (pintype "passive"))
      (node (ref "R93") (pin "2") (pinfunction "2_2") (pintype "passive"))
    )
    (net (code "109") (name "Net-(R30-Pad2)") (class "Default")
      (node (ref "R30") (pin "2") (pinfunction "2_2") (pintype "passive"))
      (node (ref "R38") (pin "1") (pinfunction "1_1") (pintype "passive"))
      (node (ref "R44") (pin "1") (pinfunction "1_1") (pintype "passive"))
      (node (ref "R92") (pin "2") (pinfunction "2_2") (pintype "passive"))
    )
    (net (code "110") (name "Net-(R35-Pad1)") (class "Default")
      (node (ref "R35") (pin "1") (pinfunction "1_1") (pintype "passive"))
      (node (ref "R36") (pin "2") (pinfunction "2_2") (pintype "passive"))
    )
    (net (code "111") (name "Net-(R37-Pad1)") (class "Default")
      (node (ref "R37") (pin "1") (pinfunction "1_1") (pintype "passive"))
      (node (ref "R38") (pin "2") (pinfunction "2_2") (pintype "passive"))
    )
    (net (code "112") (name "Net-(R55-Pad2)") (class "Default")
      (node (ref "R55") (pin "2") (pinfunction "2_2") (pintype "passive"))
      (node (ref "U7") (pin "9") (pinfunction "OUT_9") (pintype "passive"))
    )
    (net (code "113") (name "Net-(R58-Pad2)") (class "Default")
      (node (ref "R58") (pin "2") (pinfunction "2_2") (pintype "passive"))
      (node (ref "R62") (pin "1") (pinfunction "1_1") (pintype "passive"))
      (node (ref "R65") (pin "2") (pinfunction "2_2") (pintype "passive"))
    )
    (net (code "114") (name "Net-(R106-Pad2)") (class "Default")
      (node (ref "R106") (pin "2") (pinfunction "2_2") (pintype "passive"))
      (node (ref "R110") (pin "1") (pinfunction "1_1") (pintype "passive"))
    )
    (net (code "115") (name "Net-(R107-Pad2)") (class "Default")
      (node (ref "R107") (pin "2") (pinfunction "2_2") (pintype "passive"))
      (node (ref "R111") (pin "1") (pinfunction "1_1") (pintype "passive"))
    )
    (net (code "116") (name "Net-(R108-Pad2)") (class "Default")
      (node (ref "R108") (pin "2") (pinfunction "2_2") (pintype "passive"))
      (node (ref "R109") (pin "2") (pinfunction "2_2") (pintype "passive"))
      (node (ref "R112") (pin "1") (pinfunction "1_1") (pintype "passive"))
      (node (ref "R113") (pin "1") (pinfunction "1_1") (pintype "passive"))
    )
    (net (code "117") (name "Net-(R121-Pad2)") (class "Default")
      (node (ref "R121") (pin "2") (pinfunction "2_2") (pintype "passive"))
      (node (ref "R122") (pin "1") (pinfunction "1_1") (pintype "passive"))
    )
    (net (code "118") (name "Net-(R123-Pad1)") (class "Default")
      (node (ref "R123") (pin "1") (pinfunction "1_1") (pintype "passive"))
      (node (ref "R55") (pin "1") (pinfunction "1_1") (pintype "passive"))
      (node (ref "R56") (pin "2") (pinfunction "2_2") (pintype "passive"))
      (node (ref "TP46") (pin "1") (pinfunction "1_1") (pintype "passive"))
    )
    (net (code "119") (name "Net-(R130-Pad1)") (class "Default")
      (node (ref "R130") (pin "1") (pinfunction "1_1") (pintype "passive"))
      (node (ref "R131") (pin "1") (pinfunction "1_1") (pintype "passive"))
      (node (ref "S1") (pin "3") (pinfunction "3_3") (pintype "passive"))
    )
    (net (code "120") (name "Net-(U8-A)") (class "Default")
      (node (ref "R59") (pin "2") (pinfunction "2_2") (pintype "passive"))
      (node (ref "U8") (pin "2") (pinfunction "A_2") (pintype "input"))
    )
    (net (code "121") (name "Net-(U8-NC)") (class "Default")
      (node (ref "R64") (pin "2") (pinfunction "2_2") (pintype "passive"))
      (node (ref "U8") (pin "1") (pinfunction "NC_1") (pintype "passive"))
    )
    (net (code "122") (name "Net-(U8-VCC)") (class "Default")
      (node (ref "C64") (pin "1") (pinfunction "1_1") (pintype "passive"))
      (node (ref "R57") (pin "2") (pinfunction "2_2") (pintype "passive"))
      (node (ref "R97") (pin "1") (pinfunction "1_1") (pintype "passive"))
      (node (ref "U8") (pin "5") (pinfunction "VCC_5") (pintype "power_in"))
    )
    (net (code "123") (name "Net-(U9-ANODE)") (class "Default")
      (node (ref "R132") (pin "1") (pinfunction "1_1") (pintype "passive"))
      (node (ref "R60") (pin "2") (pinfunction "2_2") (pintype "passive"))
      (node (ref "U9") (pin "1") (pinfunction "ANODE_1") (pintype "passive"))
    )
    (net (code "124") (name "Net-(U9-NC)") (class "Default")
      (node (ref "R66") (pin "2") (pinfunction "2_2") (pintype "passive"))
      (node (ref "U9") (pin "2") (pinfunction "NC_2") (pintype "passive"))
    )
    (net (code "125") (name "Net-(U10-IN)") (class "Default")
      (node (ref "R61") (pin "2") (pinfunction "2_2") (pintype "passive"))
      (node (ref "U10") (pin "2") (pinfunction "IN_2") (pintype "input"))
    )
    (net (code "126") (name "Net-(U10-NC)") (class "Default")
      (node (ref "R71") (pin "2") (pinfunction "2_2") (pintype "passive"))
      (node (ref "U10") (pin "3") (pinfunction "NC_3") (pintype "passive"))
    )
    (net (code "127") (name "Net-(U11-IN)") (class "Default")
      (node (ref "C30") (pin "2") (pinfunction "2_2") (pintype "passive"))
      (node (ref "C31") (pin "2") (pinfunction "2_2") (pintype "passive"))
      (node (ref "FB2") (pin "2") (pinfunction "2_2") (pintype "power_in"))
      (node (ref "U11") (pin "1") (pinfunction "~{SHDN}_1") (pintype "input"))
      (node (ref "U11") (pin "2") (pinfunction "IN_2") (pintype "power_in"))
    )
    (net (code "128") (name "Net-(U13-VOUT)") (class "Default")
      (node (ref "C41") (pin "2") (pinfunction "2_2") (pintype "passive"))
      (node (ref "FB3") (pin "1") (pinfunction "1_1") (pintype "power_in"))
      (node (ref "U13") (pin "2") (pinfunction "VOUT_2") (pintype "passive"))
    )
    (net (code "129") (name "Net-(U14-A)") (class "Default")
      (node (ref "R74") (pin "2") (pinfunction "2_2") (pintype "passive"))
      (node (ref "U14") (pin "2") (pinfunction "A_2") (pintype "input"))
    )
    (net (code "130") (name "Net-(U14-NC)") (class "Default")
      (node (ref "R78") (pin "2") (pinfunction "2_2") (pintype "passive"))
      (node (ref "U14") (pin "1") (pinfunction "NC_1") (pintype "passive"))
    )
    (net (code "131") (name "Net-(U14-VCC)") (class "Default")
      (node (ref "C62") (pin "1") (pinfunction "1_1") (pintype "passive"))
      (node (ref "R72") (pin "2") (pinfunction "2_2") (pintype "passive"))
      (node (ref "R94") (pin "1") (pinfunction "1_1") (pintype "passive"))
      (node (ref "U14") (pin "5") (pinfunction "VCC_5") (pintype "power_in"))
    )
    (net (code "132") (name "Net-(U15-A)") (class "Default")
      (node (ref "R76") (pin "2") (pinfunction "2_2") (pintype "passive"))
      (node (ref "U15") (pin "2") (pinfunction "A_2") (pintype "input"))
    )
    (net (code "133") (name "Net-(U15-NC)") (class "Default")
      (node (ref "R79") (pin "2") (pinfunction "2_2") (pintype "passive"))
      (node (ref "U15") (pin "1") (pinfunction "NC_1") (pintype "passive"))
    )
    (net (code "134") (name "Net-(U15-VCC)") (class "Default")
      (node (ref "C63") (pin "1") (pinfunction "1_1") (pintype "passive"))
      (node (ref "R73") (pin "2") (pinfunction "2_2") (pintype "passive"))
      (node (ref "R95") (pin "1") (pinfunction "1_1") (pintype "passive"))
      (node (ref "U15") (pin "5") (pinfunction "VCC_5") (pintype "power_in"))
    )
    (net (code "135") (name "Net-(U16-A)") (class "Default")
      (node (ref "R77") (pin "2") (pinfunction "2_2") (pintype "passive"))
      (node (ref "U16") (pin "1") (pinfunction "A_1") (pintype "passive"))
    )
    (net (code "136") (name "Net-(U17-A)") (class "Default")
      (node (ref "R75") (pin "2") (pinfunction "2_2") (pintype "passive"))
      (node (ref "U17") (pin "1") (pinfunction "A_1") (pintype "passive"))
    )
    (net (code "137") (name "Net-(U18-VIN)") (class "Default")
      (node (ref "C59") (pin "2") (pinfunction "2_2") (pintype "passive"))
      (node (ref "R123") (pin "2") (pinfunction "2_2") (pintype "passive"))
      (node (ref "U18") (pin "2") (pinfunction "VIN_2") (pintype "input"))
    )
    (net (code "138") (name "Net-(U18-VOUTN)") (class "Default")
      (node (ref "R124") (pin "1") (pinfunction "1_1") (pintype "passive"))
      (node (ref "U18") (pin "6") (pinfunction "VOUTN_6") (pintype "output"))
    )
    (net (code "139") (name "Net-(U18-VOUTP)") (class "Default")
      (node (ref "R127") (pin "1") (pinfunction "1_1") (pintype "passive"))
      (node (ref "TP55") (pin "1") (pinfunction "1_1") (pintype "passive"))
      (node (ref "U18") (pin "7") (pinfunction "VOUTP_7") (pintype "output"))
    )
    (net (code "140") (name "Net-(U19-IN+)") (class "Default")
      (node (ref "C65") (pin "2") (pinfunction "2_2") (pintype "passive"))
      (node (ref "R128") (pin "2") (pinfunction "2_2") (pintype "passive"))
      (node (ref "R129") (pin "2") (pinfunction "2_2") (pintype "passive"))
      (node (ref "TP57") (pin "1") (pinfunction "1_1") (pintype "passive"))
      (node (ref "U19") (pin "3") (pinfunction "IN+_3") (pintype "input"))
    )
    (net (code "141") (name "Net-(U19-IN-)") (class "Default")
      (node (ref "C46") (pin "2") (pinfunction "2_2") (pintype "passive"))
      (node (ref "R121") (pin "1") (pinfunction "1_1") (pintype "passive"))
      (node (ref "R125") (pin "2") (pinfunction "2_2") (pintype "passive"))
      (node (ref "TP54") (pin "1") (pinfunction "1_1") (pintype "passive"))
      (node (ref "U19") (pin "4") (pinfunction "IN-_4") (pintype "input"))
    )
    (net (code "142") (name "Net-(U19-OUT)") (class "Default")
      (node (ref "C46") (pin "1") (pinfunction "1_1") (pintype "passive"))
      (node (ref "R122") (pin "2") (pinfunction "2_2") (pintype "passive"))
      (node (ref "R126") (pin "1") (pinfunction "1_1") (pintype "passive"))
      (node (ref "U19") (pin "1") (pinfunction "OUT_1") (pintype "output"))
    )
    (net (code "143") (name "Output 500V") (class "Default")
      (node (ref "C18") (pin "1") (pinfunction "1_1") (pintype "passive"))
      (node (ref "C19") (pin "1") (pinfunction "1_1") (pintype "passive"))
      (node (ref "C20") (pin "1") (pinfunction "1_1") (pintype "passive"))
      (node (ref "C21") (pin "1") (pinfunction "1_1") (pintype "passive"))
      (node (ref "J6") (pin "1") (pinfunction "1_1") (pintype "passive"))
      (node (ref "L3") (pin "2") (pinfunction "2_2") (pintype "passive"))
      (node (ref "R10") (pin "2") (pinfunction "2_2") (pintype "passive"))
      (node (ref "R108") (pin "1") (pinfunction "1_1") (pintype "passive"))
      (node (ref "R109") (pin "1") (pinfunction "1_1") (pintype "passive"))
      (node (ref "R9") (pin "2") (pinfunction "2_2") (pintype "passive"))
      (node (ref "TP1") (pin "1") (pinfunction "1_1") (pintype "passive"))
      (node (ref "TP4") (pin "1") (pinfunction "1_1") (pintype "passive"))
    )
    (net (code "144") (name "Output Current of FB to micro controller") (class "Default")
      (node (ref "EC2") (pin "101") (pinfunction "101_101") (pintype "bidirectional"))
      (node (ref "J4") (pin "12") (pinfunction "12_12") (pintype "passive"))
    )
    (net (code "145") (name "Output Current to micro controller") (class "Default")
      (node (ref "EC2") (pin "104") (pinfunction "104_104") (pintype "bidirectional"))
      (node (ref "FB10") (pin "2") (pinfunction "2_2") (pintype "power_in"))
      (node (ref "J5") (pin "7") (pinfunction "7_7") (pintype "passive"))
    )
    (net (code "146") (name "Output voltage of Buck") (class "Default")
      (node (ref "EC2") (pin "110") (pinfunction "110_110") (pintype "bidirectional"))
      (node (ref "FB7") (pin "2") (pinfunction "2_2") (pintype "power_in"))
      (node (ref "J5") (pin "6") (pinfunction "6_6") (pintype "passive"))
      (node (ref "TP30") (pin "1") (pinfunction "1_1") (pintype "passive"))
    )
    (net (code "147") (name "Output voltage of FB") (class "Default")
      (node (ref "EC2") (pin "107") (pinfunction "107_107") (pintype "bidirectional"))
      (node (ref "J4") (pin "11") (pinfunction "11_11") (pintype "passive"))
    )
    (net (code "148") (name "P1 OP37") (class "Default")
      (node (ref "R17") (pin "2") (pinfunction "2_2") (pintype "passive"))
      (node (ref "U1") (pin "1") (pinfunction "OFFSET_TRIM_1") (pintype "input"))
    )
    (net (code "149") (name "P1 OP37-2") (class "Default")
      (node (ref "R19") (pin "2") (pinfunction "2_2") (pintype "passive"))
      (node (ref "U2") (pin "1") (pinfunction "OFFSET_TRIM_1") (pintype "input"))
    )
    (net (code "150") (name "P2 OP37") (class "Default")
      (node (ref "C11") (pin "1") (pinfunction "1_1") (pintype "passive"))
      (node (ref "R22") (pin "1") (pinfunction "1_1") (pintype "passive"))
      (node (ref "R25") (pin "2") (pinfunction "2_2") (pintype "passive"))
      (node (ref "R39") (pin "2") (pinfunction "2_2") (pintype "passive"))
      (node (ref "R40") (pin "2") (pinfunction "2_2") (pintype "passive"))
      (node (ref "U1") (pin "2") (pinfunction "IN-_2") (pintype "input"))
    )
    (net (code "151") (name "P2 OP37-2") (class "Default")
      (node (ref "C12") (pin "1") (pinfunction "1_1") (pintype "passive"))
      (node (ref "R24") (pin "1") (pinfunction "1_1") (pintype "passive"))
      (node (ref "R27") (pin "2") (pinfunction "2_2") (pintype "passive"))
      (node (ref "R41") (pin "2") (pinfunction "2_2") (pintype "passive"))
      (node (ref "R42") (pin "2") (pinfunction "2_2") (pintype "passive"))
      (node (ref "U2") (pin "2") (pinfunction "IN-_2") (pintype "input"))
    )
    (net (code "152") (name "P3 OP37") (class "Default")
      (node (ref "C9") (pin "1") (pinfunction "1_1") (pintype "passive"))
      (node (ref "R21") (pin "1") (pinfunction "1_1") (pintype "passive"))
      (node (ref "R33") (pin "1") (pinfunction "1_1") (pintype "passive"))
      (node (ref "U1") (pin "3") (pinfunction "IN+_3") (pintype "input"))
    )
    (net (code "153") (name "P3 OP37-2") (class "Default")
      (node (ref "C10") (pin "1") (pinfunction "1_1") (pintype "passive"))
      (node (ref "R23") (pin "1") (pinfunction "1_1") (pintype "passive"))
      (node (ref "R34") (pin "1") (pinfunction "1_1") (pintype "passive"))
      (node (ref "U2") (pin "3") (pinfunction "IN+_3") (pintype "input"))
    )
    (net (code "154") (name "P4 OP37") (class "Default")
      (node (ref "R3") (pin "1") (pinfunction "1_1") (pintype "passive"))
      (node (ref "U1") (pin "4") (pinfunction "VCC-_4") (pintype "power_in"))
    )
    (net (code "155") (name "P4 OP37-2") (class "Default")
      (node (ref "R4") (pin "1") (pinfunction "1_1") (pintype "passive"))
      (node (ref "U2") (pin "4") (pinfunction "VCC-_4") (pintype "power_in"))
    )
    (net (code "156") (name "P5 OP37") (class "Default")
      (node (ref "R5") (pin "1") (pinfunction "1_1") (pintype "passive"))
      (node (ref "U1") (pin "5") (pinfunction "NC_5") (pintype "passive"))
    )
    (net (code "157") (name "P5 OP37-2") (class "Default")
      (node (ref "R6") (pin "1") (pinfunction "1_1") (pintype "passive"))
      (node (ref "U2") (pin "5") (pinfunction "NC_5") (pintype "passive"))
    )
    (net (code "158") (name "P6 OP37") (class "Default")
      (node (ref "C11") (pin "2") (pinfunction "2_2") (pintype "passive"))
      (node (ref "C13") (pin "1") (pinfunction "1_1") (pintype "passive"))
      (node (ref "R39") (pin "1") (pinfunction "1_1") (pintype "passive"))
      (node (ref "R40") (pin "1") (pinfunction "1_1") (pintype "passive"))
      (node (ref "R45") (pin "1") (pinfunction "1_1") (pintype "passive"))
      (node (ref "TP19") (pin "1") (pinfunction "1_1") (pintype "passive"))
      (node (ref "U1") (pin "6") (pinfunction "OUT_6") (pintype "output"))
    )
    (net (code "159") (name "P6 OP37-2") (class "Default")
      (node (ref "C12") (pin "2") (pinfunction "2_2") (pintype "passive"))
      (node (ref "C14") (pin "1") (pinfunction "1_1") (pintype "passive"))
      (node (ref "R41") (pin "1") (pinfunction "1_1") (pintype "passive"))
      (node (ref "R42") (pin "1") (pinfunction "1_1") (pintype "passive"))
      (node (ref "R46") (pin "1") (pinfunction "1_1") (pintype "passive"))
      (node (ref "TP20") (pin "1") (pinfunction "1_1") (pintype "passive"))
      (node (ref "U2") (pin "6") (pinfunction "OUT_6") (pintype "output"))
    )
    (net (code "160") (name "P7 OP37") (class "Default")
      (node (ref "C55") (pin "1") (pinfunction "1_1") (pintype "passive"))
      (node (ref "R1") (pin "2") (pinfunction "2_2") (pintype "passive"))
      (node (ref "R87") (pin "2") (pinfunction "2_2") (pintype "passive"))
      (node (ref "U1") (pin "7") (pinfunction "VCC+_7") (pintype "power_in"))
    )
    (net (code "161") (name "P7 OP37-2") (class "Default")
      (node (ref "C56") (pin "1") (pinfunction "1_1") (pintype "passive"))
      (node (ref "R2") (pin "2") (pinfunction "2_2") (pintype "passive"))
      (node (ref "R86") (pin "2") (pinfunction "2_2") (pintype "passive"))
      (node (ref "U2") (pin "7") (pinfunction "VCC+_7") (pintype "power_in"))
    )
    (net (code "162") (name "P8 OP37") (class "Default")
      (node (ref "R35") (pin "2") (pinfunction "2_2") (pintype "passive"))
      (node (ref "U1") (pin "8") (pinfunction "OFFSET_TRIM_8") (pintype "input"))
    )
    (net (code "163") (name "P8 OP37-2") (class "Default")
      (node (ref "R37") (pin "2") (pinfunction "2_2") (pintype "passive"))
      (node (ref "U2") (pin "8") (pinfunction "OFFSET_TRIM_8") (pintype "input"))
    )
    (net (code "164") (name "Relay 2") (class "Default")
      (node (ref "D5") (pin "1") (pinfunction "A_1") (pintype "passive"))
      (node (ref "K1") (pin "A1") (pinfunction "A1_A1") (pintype "passive"))
      (node (ref "TP39") (pin "1") (pinfunction "1_1") (pintype "passive"))
      (node (ref "U16") (pin "4") (pinfunction "C_4") (pintype "passive"))
    )
    (net (code "165") (name "Relay FB command") (class "Default")
      (node (ref "EC2") (pin "16") (pinfunction "16_16") (pintype "bidirectional"))
      (node (ref "J4") (pin "3") (pinfunction "3_3") (pintype "passive"))
    )
    (net (code "166") (name "Relay command") (class "Default")
      (node (ref "EC2") (pin "54") (pinfunction "54_54") (pintype "bidirectional"))
      (node (ref "FB5") (pin "1") (pinfunction "1_1") (pintype "power_in"))
      (node (ref "J5") (pin "11") (pinfunction "11_11") (pintype "passive"))
      (node (ref "R100") (pin "1") (pinfunction "1_1") (pintype "passive"))
      (node (ref "TP36") (pin "1") (pinfunction "1_1") (pintype "passive"))
    )
    (net (code "167") (name "Spare Analog FB 1") (class "Default")
      (node (ref "J4") (pin "10") (pinfunction "10_10") (pintype "passive"))
      (node (ref "Rj10") (pin "2") (pinfunction "2_2") (pintype "passive"))
    )
    (net (code "168") (name "Spare Analog FB 2") (class "Default")
      (node (ref "J4") (pin "22") (pinfunction "22_22") (pintype "passive"))
      (node (ref "Rj12") (pin "1") (pinfunction "1_1") (pintype "passive"))
    )
    (net (code "169") (name "Spare Analog FB 3") (class "Default")
      (node (ref "J4") (pin "9") (pinfunction "9_9") (pintype "passive"))
      (node (ref "Rj11") (pin "1") (pinfunction "1_1") (pintype "passive"))
    )
    (net (code "170") (name "Spare Analog FB 4") (class "Default")
      (node (ref "J4") (pin "21") (pinfunction "21_21") (pintype "passive"))
      (node (ref "Rj9") (pin "1") (pinfunction "1_1") (pintype "passive"))
    )
    (net (code "171") (name "Spare Dig FB 1") (class "Default")
      (node (ref "J4") (pin "19") (pinfunction "19_19") (pintype "passive"))
      (node (ref "Rj1") (pin "1") (pinfunction "1_1") (pintype "passive"))
    )
    (net (code "172") (name "Spare Dig FB 2") (class "Default")
      (node (ref "J4") (pin "7") (pinfunction "7_7") (pintype "passive"))
      (node (ref "Rj2") (pin "1") (pinfunction "1_1") (pintype "passive"))
    )
    (net (code "173") (name "Spare Dig FB 3") (class "Default")
      (node (ref "J4") (pin "20") (pinfunction "20_20") (pintype "passive"))
      (node (ref "Rj3") (pin "1") (pinfunction "1_1") (pintype "passive"))
    )
    (net (code "174") (name "Spare Dig FB 4") (class "Default")
      (node (ref "J4") (pin "8") (pinfunction "8_8") (pintype "passive"))
      (node (ref "Rj4") (pin "1") (pinfunction "1_1") (pintype "passive"))
    )
    (net (code "175") (name "TEMP") (class "Default")
      (node (ref "EC2") (pin "98") (pinfunction "98_98") (pintype "bidirectional"))
      (node (ref "FB8") (pin "2") (pinfunction "2_2") (pintype "power_in"))
      (node (ref "J5") (pin "5") (pinfunction "5_5") (pintype "passive"))
    )
    (net (code "176") (name "TEMP of the heatsink") (class "Default")
      (node (ref "EC2") (pin "112") (pinfunction "112_112") (pintype "bidirectional"))
      (node (ref "FB9") (pin "2") (pinfunction "2_2") (pintype "power_in"))
      (node (ref "J5") (pin "13") (pinfunction "13_13") (pintype "passive"))
    )
    (net (code "177") (name "VDD Sensor voltage input") (class "Default")
      (node (ref "C37") (pin "1") (pinfunction "1_1") (pintype "passive"))
      (node (ref "C6") (pin "1") (pinfunction "1_1") (pintype "passive"))
      (node (ref "DS9") (pin "1") (pinfunction "A_1") (pintype "passive"))
      (node (ref "Q1") (pin "1") (pinfunction "VDD1_1") (pintype "power_in"))
      (node (ref "TP10") (pin "1") (pinfunction "1_1") (pintype "passive"))
      (node (ref "TP16") (pin "1") (pinfunction "1_1") (pintype "passive"))
      (node (ref "U5") (pin "3") (pinfunction "+Out_3") (pintype "passive"))
    )
    (net (code "178") (name "VDD Sensor voltage out") (class "Default")
      (node (ref "C39") (pin "1") (pinfunction "1_1") (pintype "passive"))
      (node (ref "C8") (pin "1") (pinfunction "1_1") (pintype "passive"))
      (node (ref "DS8") (pin "1") (pinfunction "A_1") (pintype "passive"))
      (node (ref "Q2") (pin "1") (pinfunction "VDD1_1") (pintype "power_in"))
      (node (ref "TP22") (pin "1") (pinfunction "1_1") (pintype "passive"))
      (node (ref "U6") (pin "3") (pinfunction "+Out_3") (pintype "passive"))
    )
    (net (code "179") (name "VGS B") (class "Default")
      (node (ref "C34") (pin "1") (pinfunction "1_1") (pintype "passive"))
      (node (ref "C45") (pin "2") (pinfunction "2_2") (pintype "passive"))
      (node (ref "C53") (pin "1") (pinfunction "1_1") (pintype "passive"))
      (node (ref "C54") (pin "1") (pinfunction "1_1") (pintype "passive"))
      (node (ref "C66") (pin "1") (pinfunction "1_1") (pintype "passive"))
      (node (ref "C67") (pin "1") (pinfunction "1_1") (pintype "passive"))
      (node (ref "CR6") (pin "2") (pinfunction "K_2") (pintype "passive"))
      (node (ref "CR9") (pin "2") (pinfunction "K_2") (pintype "passive"))
      (node (ref "DS7") (pin "1") (pinfunction "A_1") (pintype "passive"))
      (node (ref "TP5") (pin "1") (pinfunction "1_1") (pintype "passive"))
      (node (ref "U10") (pin "1") (pinfunction "VCC_1") (pintype "power_in"))
      (node (ref "U10") (pin "8") (pinfunction "VCC_8") (pintype "power_in"))
      (node (ref "U3") (pin "3") (pinfunction "+Out_3") (pintype "passive"))
      (node (ref "U9") (pin "6") (pinfunction "VDD_6") (pintype "power_in"))
    )
    (net (code "180") (name "unconnected-(EC2-Pad2)") (class "Default")
      (node (ref "EC2") (pin "2") (pinfunction "2_2") (pintype "bidirectional"))
    )
    (net (code "181") (name "unconnected-(EC2-Pad3)") (class "Default")
      (node (ref "EC2") (pin "3") (pinfunction "3_3") (pintype "bidirectional"))
    )
    (net (code "182") (name "unconnected-(EC2-Pad4)") (class "Default")
      (node (ref "EC2") (pin "4") (pinfunction "4_4") (pintype "bidirectional"))
    )
    (net (code "183") (name "unconnected-(EC2-Pad5)") (class "Default")
      (node (ref "EC2") (pin "5") (pinfunction "5_5") (pintype "bidirectional"))
    )
    (net (code "184") (name "unconnected-(EC2-Pad6)") (class "Default")
      (node (ref "EC2") (pin "6") (pinfunction "6_6") (pintype "bidirectional"))
    )
    (net (code "185") (name "unconnected-(EC2-Pad7)") (class "Default")
      (node (ref "EC2") (pin "7") (pinfunction "7_7") (pintype "bidirectional"))
    )
    (net (code "186") (name "unconnected-(EC2-Pad8)") (class "Default")
      (node (ref "EC2") (pin "8") (pinfunction "8_8") (pintype "bidirectional"))
    )
    (net (code "187") (name "unconnected-(EC2-Pad11)") (class "Default")
      (node (ref "EC2") (pin "11") (pinfunction "11_11") (pintype "bidirectional"))
    )
    (net (code "188") (name "unconnected-(EC2-Pad12)") (class "Default")
      (node (ref "EC2") (pin "12") (pinfunction "12_12") (pintype "bidirectional"))
    )
    (net (code "189") (name "unconnected-(EC2-Pad13)") (class "Default")
      (node (ref "EC2") (pin "13") (pinfunction "13_13") (pintype "bidirectional"))
    )
    (net (code "190") (name "unconnected-(EC2-Pad14)") (class "Default")
      (node (ref "EC2") (pin "14") (pinfunction "14_14") (pintype "bidirectional"))
    )
    (net (code "191") (name "unconnected-(EC2-Pad15)") (class "Default")
      (node (ref "EC2") (pin "15") (pinfunction "15_15") (pintype "bidirectional"))
    )
    (net (code "192") (name "unconnected-(EC2-Pad17)") (class "Default")
      (node (ref "EC2") (pin "17") (pinfunction "17_17") (pintype "bidirectional"))
    )
    (net (code "193") (name "unconnected-(EC2-Pad19)") (class "Default")
      (node (ref "EC2") (pin "19") (pinfunction "19_19") (pintype "bidirectional"))
    )
    (net (code "194") (name "unconnected-(EC2-Pad20)") (class "Default")
      (node (ref "EC2") (pin "20") (pinfunction "20_20") (pintype "bidirectional"))
    )
    (net (code "195") (name "unconnected-(EC2-Pad21)") (class "Default")
      (node (ref "EC2") (pin "21") (pinfunction "21_21") (pintype "bidirectional"))
    )
    (net (code "196") (name "unconnected-(EC2-Pad22)") (class "Default")
      (node (ref "EC2") (pin "22") (pinfunction "22_22") (pintype "bidirectional"))
    )
    (net (code "197") (name "unconnected-(EC2-Pad25)") (class "Default")
      (node (ref "EC2") (pin "25") (pinfunction "25_25") (pintype "bidirectional"))
    )
    (net (code "198") (name "unconnected-(EC2-Pad26)") (class "Default")
      (node (ref "EC2") (pin "26") (pinfunction "26_26") (pintype "bidirectional"))
    )
    (net (code "199") (name "unconnected-(EC2-Pad27)") (class "Default")
      (node (ref "EC2") (pin "27") (pinfunction "27_27") (pintype "bidirectional"))
    )
    (net (code "200") (name "unconnected-(EC2-Pad28)") (class "Default")
      (node (ref "EC2") (pin "28") (pinfunction "28_28") (pintype "bidirectional"))
    )
    (net (code "201") (name "unconnected-(EC2-Pad29)") (class "Default")
      (node (ref "EC2") (pin "29") (pinfunction "29_29") (pintype "bidirectional"))
    )
    (net (code "202") (name "unconnected-(EC2-Pad30)") (class "Default")
      (node (ref "EC2") (pin "30") (pinfunction "30_30") (pintype "bidirectional"))
    )
    (net (code "203") (name "unconnected-(EC2-Pad31)") (class "Default")
      (node (ref "EC2") (pin "31") (pinfunction "31_31") (pintype "bidirectional"))
    )
    (net (code "204") (name "unconnected-(EC2-Pad32)") (class "Default")
      (node (ref "EC2") (pin "32") (pinfunction "32_32") (pintype "bidirectional"))
    )
    (net (code "205") (name "unconnected-(EC2-Pad33)") (class "Default")
      (node (ref "EC2") (pin "33") (pinfunction "33_33") (pintype "bidirectional"))
    )
    (net (code "206") (name "unconnected-(EC2-Pad35)") (class "Default")
      (node (ref "EC2") (pin "35") (pinfunction "35_35") (pintype "bidirectional"))
    )
    (net (code "207") (name "unconnected-(EC2-Pad39)") (class "Default")
      (node (ref "EC2") (pin "39") (pinfunction "39_39") (pintype "bidirectional"))
    )
    (net (code "208") (name "unconnected-(EC2-Pad41)") (class "Default")
      (node (ref "EC2") (pin "41") (pinfunction "41_41") (pintype "bidirectional"))
    )
    (net (code "209") (name "unconnected-(EC2-Pad43)") (class "Default")
      (node (ref "EC2") (pin "43") (pinfunction "43_43") (pintype "bidirectional"))
    )
    (net (code "210") (name "unconnected-(EC2-Pad44)") (class "Default")
      (node (ref "EC2") (pin "44") (pinfunction "44_44") (pintype "bidirectional"))
    )
    (net (code "211") (name "unconnected-(EC2-Pad45)") (class "Default")
      (node (ref "EC2") (pin "45") (pinfunction "45_45") (pintype "bidirectional"))
    )
    (net (code "212") (name "unconnected-(EC2-Pad46)") (class "Default")
      (node (ref "EC2") (pin "46") (pinfunction "46_46") (pintype "bidirectional"))
    )
    (net (code "213") (name "unconnected-(EC2-Pad47)") (class "Default")
      (node (ref "EC2") (pin "47") (pinfunction "47_47") (pintype "bidirectional"))
    )
    (net (code "214") (name "unconnected-(EC2-Pad48)") (class "Default")
      (node (ref "EC2") (pin "48") (pinfunction "48_48") (pintype "bidirectional"))
    )
    (net (code "215") (name "unconnected-(EC2-Pad49)") (class "Default")
      (node (ref "EC2") (pin "49") (pinfunction "49_49") (pintype "bidirectional"))
    )
    (net (code "216") (name "unconnected-(EC2-Pad50)") (class "Default")
      (node (ref "EC2") (pin "50") (pinfunction "50_50") (pintype "bidirectional"))
    )
    (net (code "217") (name "unconnected-(EC2-Pad51)") (class "Default")
      (node (ref "EC2") (pin "51") (pinfunction "51_51") (pintype "bidirectional"))
    )
    (net (code "218") (name "unconnected-(EC2-Pad52)") (class "Default")
      (node (ref "EC2") (pin "52") (pinfunction "52_52") (pintype "bidirectional"))
    )
    (net (code "219") (name "unconnected-(EC2-Pad53)") (class "Default")
      (node (ref "EC2") (pin "53") (pinfunction "53_53") (pintype "bidirectional"))
    )
    (net (code "220") (name "unconnected-(EC2-Pad55)") (class "Default")
      (node (ref "EC2") (pin "55") (pinfunction "55_55") (pintype "bidirectional"))
    )
    (net (code "221") (name "unconnected-(EC2-Pad58)") (class "Default")
      (node (ref "EC2") (pin "58") (pinfunction "58_58") (pintype "bidirectional"))
    )
    (net (code "222") (name "unconnected-(EC2-Pad61)") (class "Default")
      (node (ref "EC2") (pin "61") (pinfunction "61_61") (pintype "bidirectional"))
    )
    (net (code "223") (name "unconnected-(EC2-Pad62)") (class "Default")
      (node (ref "EC2") (pin "62") (pinfunction "62_62") (pintype "bidirectional"))
    )
    (net (code "224") (name "unconnected-(EC2-Pad63)") (class "Default")
      (node (ref "EC2") (pin "63") (pinfunction "63_63") (pintype "bidirectional"))
    )
    (net (code "225") (name "unconnected-(EC2-Pad76)") (class "Default")
      (node (ref "EC2") (pin "76") (pinfunction "76_76") (pintype "bidirectional"))
    )
    (net (code "226") (name "unconnected-(EC2-Pad77)") (class "Default")
      (node (ref "EC2") (pin "77") (pinfunction "77_77") (pintype "bidirectional"))
    )
    (net (code "227") (name "unconnected-(EC2-Pad78)") (class "Default")
      (node (ref "EC2") (pin "78") (pinfunction "78_78") (pintype "bidirectional"))
    )
    (net (code "228") (name "unconnected-(EC2-Pad79)") (class "Default")
      (node (ref "EC2") (pin "79") (pinfunction "79_79") (pintype "bidirectional"))
    )
    (net (code "229") (name "unconnected-(EC2-Pad80)") (class "Default")
      (node (ref "EC2") (pin "80") (pinfunction "80_80") (pintype "bidirectional"))
    )
    (net (code "230") (name "unconnected-(EC2-Pad81)") (class "Default")
      (node (ref "EC2") (pin "81") (pinfunction "81_81") (pintype "bidirectional"))
    )
    (net (code "231") (name "unconnected-(EC2-Pad82)") (class "Default")
      (node (ref "EC2") (pin "82") (pinfunction "82_82") (pintype "bidirectional"))
    )
    (net (code "232") (name "unconnected-(EC2-Pad84)") (class "Default")
      (node (ref "EC2") (pin "84") (pinfunction "84_84") (pintype "bidirectional"))
    )
    (net (code "233") (name "unconnected-(EC2-Pad85)") (class "Default")
      (node (ref "EC2") (pin "85") (pinfunction "85_85") (pintype "bidirectional"))
    )
    (net (code "234") (name "unconnected-(EC2-Pad87)") (class "Default")
      (node (ref "EC2") (pin "87") (pinfunction "87_87") (pintype "bidirectional"))
    )
    (net (code "235") (name "unconnected-(EC2-Pad88)") (class "Default")
      (node (ref "EC2") (pin "88") (pinfunction "88_88") (pintype "bidirectional"))
    )
    (net (code "236") (name "unconnected-(EC2-Pad89)") (class "Default")
      (node (ref "EC2") (pin "89") (pinfunction "89_89") (pintype "bidirectional"))
    )
    (net (code "237") (name "unconnected-(EC2-Pad90)") (class "Default")
      (node (ref "EC2") (pin "90") (pinfunction "90_90") (pintype "bidirectional"))
    )
    (net (code "238") (name "unconnected-(EC2-Pad91)") (class "Default")
      (node (ref "EC2") (pin "91") (pinfunction "91_91") (pintype "bidirectional"))
    )
    (net (code "239") (name "unconnected-(EC2-Pad93)") (class "Default")
      (node (ref "EC2") (pin "93") (pinfunction "93_93") (pintype "bidirectional"))
    )
    (net (code "240") (name "unconnected-(EC2-Pad113)") (class "Default")
      (node (ref "EC2") (pin "113") (pinfunction "113_113") (pintype "bidirectional"))
    )
    (net (code "241") (name "unconnected-(EC2-Pad115)") (class "Default")
      (node (ref "EC2") (pin "115") (pinfunction "115_115") (pintype "bidirectional"))
    )
    (net (code "242") (name "unconnected-(EC2-Pad116)") (class "Default")
      (node (ref "EC2") (pin "116") (pinfunction "116_116") (pintype "bidirectional"))
    )
    (net (code "243") (name "unconnected-(EC2-Pad117)") (class "Default")
      (node (ref "EC2") (pin "117") (pinfunction "117_117") (pintype "bidirectional"))
    )
    (net (code "244") (name "unconnected-(EC2-Pad118)") (class "Default")
      (node (ref "EC2") (pin "118") (pinfunction "118_118") (pintype "bidirectional"))
    )
    (net (code "245") (name "unconnected-(EC2-Pad119)") (class "Default")
      (node (ref "EC2") (pin "119") (pinfunction "119_119") (pintype "bidirectional"))
    )
    (net (code "246") (name "unconnected-(EC2-Pad120)") (class "Default")
      (node (ref "EC2") (pin "120") (pinfunction "120_120") (pintype "bidirectional"))
    )
    (net (code "247") (name "unconnected-(J2-Pad1)") (class "Default")
      (node (ref "J2") (pin "1") (pinfunction "1_1") (pintype "passive"))
    )
    (net (code "248") (name "unconnected-(J2-Pad2)") (class "Default")
      (node (ref "J2") (pin "2") (pinfunction "2_2") (pintype "passive"))
    )
    (net (code "249") (name "unconnected-(J4-PadM1)") (class "Default")
      (node (ref "J4") (pin "M1") (pinfunction "M1_M1") (pintype "passive"))
    )
    (net (code "250") (name "unconnected-(J4-PadM2)") (class "Default")
      (node (ref "J4") (pin "M2") (pinfunction "M2_M2") (pintype "passive"))
    )
    (net (code "251") (name "unconnected-(J5-PadM1)") (class "Default")
      (node (ref "J5") (pin "M1") (pinfunction "M1_M1") (pintype "passive"))
    )
    (net (code "252") (name "unconnected-(J5-PadM2)") (class "Default")
      (node (ref "J5") (pin "M2") (pinfunction "M2_M2") (pintype "passive"))
    )
    (net (code "253") (name "unconnected-(OK1A-Open-Pad3)") (class "Default")
      (node (ref "OK1") (pin "3") (pinfunction "Open_3") (pintype "passive"))
    )
    (net (code "254") (name "unconnected-(TP23-Pad1)") (class "Default")
      (node (ref "TP23") (pin "1") (pinfunction "1_1") (pintype "passive"))
    )
    (net (code "255") (name "unconnected-(TP26-Pad1)") (class "Default")
      (node (ref "TP26") (pin "1") (pinfunction "1_1") (pintype "passive"))
    )
    (net (code "256") (name "unconnected-(TP35-Pad1)") (class "Default")
      (node (ref "TP35") (pin "1") (pinfunction "1_1") (pintype "passive"))
    )
    (net (code "257") (name "unconnected-(TP40-Pad1)") (class "Default")
      (node (ref "TP40") (pin "1") (pinfunction "1_1") (pintype "passive"))
    )
    (net (code "258") (name "unconnected-(TP58-Pad1)") (class "Default")
      (node (ref "TP58") (pin "1") (pinfunction "1_1") (pintype "passive"))
    )
    (net (code "259") (name "unconnected-(U3-on{slash}off-Pad6)") (class "Default")
      (node (ref "U3") (pin "6") (pinfunction "on/off_6") (pintype "passive"))
    )
    (net (code "260") (name "unconnected-(U3-trim-Pad4)") (class "Default")
      (node (ref "U3") (pin "4") (pinfunction "trim_4") (pintype "passive"))
    )
    (net (code "261") (name "unconnected-(U4-Pad1)") (class "Default")
      (node (ref "U4") (pin "1") (pinfunction "1_1") (pintype "passive"))
    )
    (net (code "262") (name "unconnected-(U4-Pad3)") (class "Default")
      (node (ref "U4") (pin "3") (pinfunction "3_3") (pintype "passive"))
    )
    (net (code "263") (name "unconnected-(U4-Pad5)") (class "Default")
      (node (ref "U4") (pin "5") (pinfunction "5_5") (pintype "passive"))
    )
    (net (code "264") (name "unconnected-(U4-Pad6)") (class "Default")
      (node (ref "U4") (pin "6") (pinfunction "6_6") (pintype "passive"))
    )
    (net (code "265") (name "unconnected-(U5-on{slash}off-Pad6)") (class "Default")
      (node (ref "U5") (pin "6") (pinfunction "on/off_6") (pintype "passive"))
    )
    (net (code "266") (name "unconnected-(U5-trim-Pad4)") (class "Default")
      (node (ref "U5") (pin "4") (pinfunction "trim_4") (pintype "passive"))
    )
    (net (code "267") (name "unconnected-(U6-on{slash}off-Pad6)") (class "Default")
      (node (ref "U6") (pin "6") (pinfunction "on/off_6") (pintype "passive"))
    )
    (net (code "268") (name "unconnected-(U6-trim-Pad4)") (class "Default")
      (node (ref "U6") (pin "4") (pinfunction "trim_4") (pintype "passive"))
    )
    (net (code "269") (name "unconnected-(U7-REF-Pad10)") (class "Default")
      (node (ref "U7") (pin "10") (pinfunction "REF_10") (pintype "passive"))
    )
    (net (code "270") (name "unconnected-(U12-on{slash}off-Pad6)") (class "Default")
      (node (ref "U12") (pin "6") (pinfunction "on/off_6") (pintype "passive+no_connect"))
    )
    (net (code "271") (name "unconnected-(U12-trim-Pad4)") (class "Default")
      (node (ref "U12") (pin "4") (pinfunction "trim_4") (pintype "passive+no_connect"))
    )
    (net (code "272") (name "unconnected-(U17-C-Pad4)") (class "Default")
      (node (ref "U17") (pin "4") (pinfunction "C_4") (pintype "passive"))
    )
  )
)
